# Main_Board_Schematic.net
KiCad netlist of a schematic drawn in EAGLE
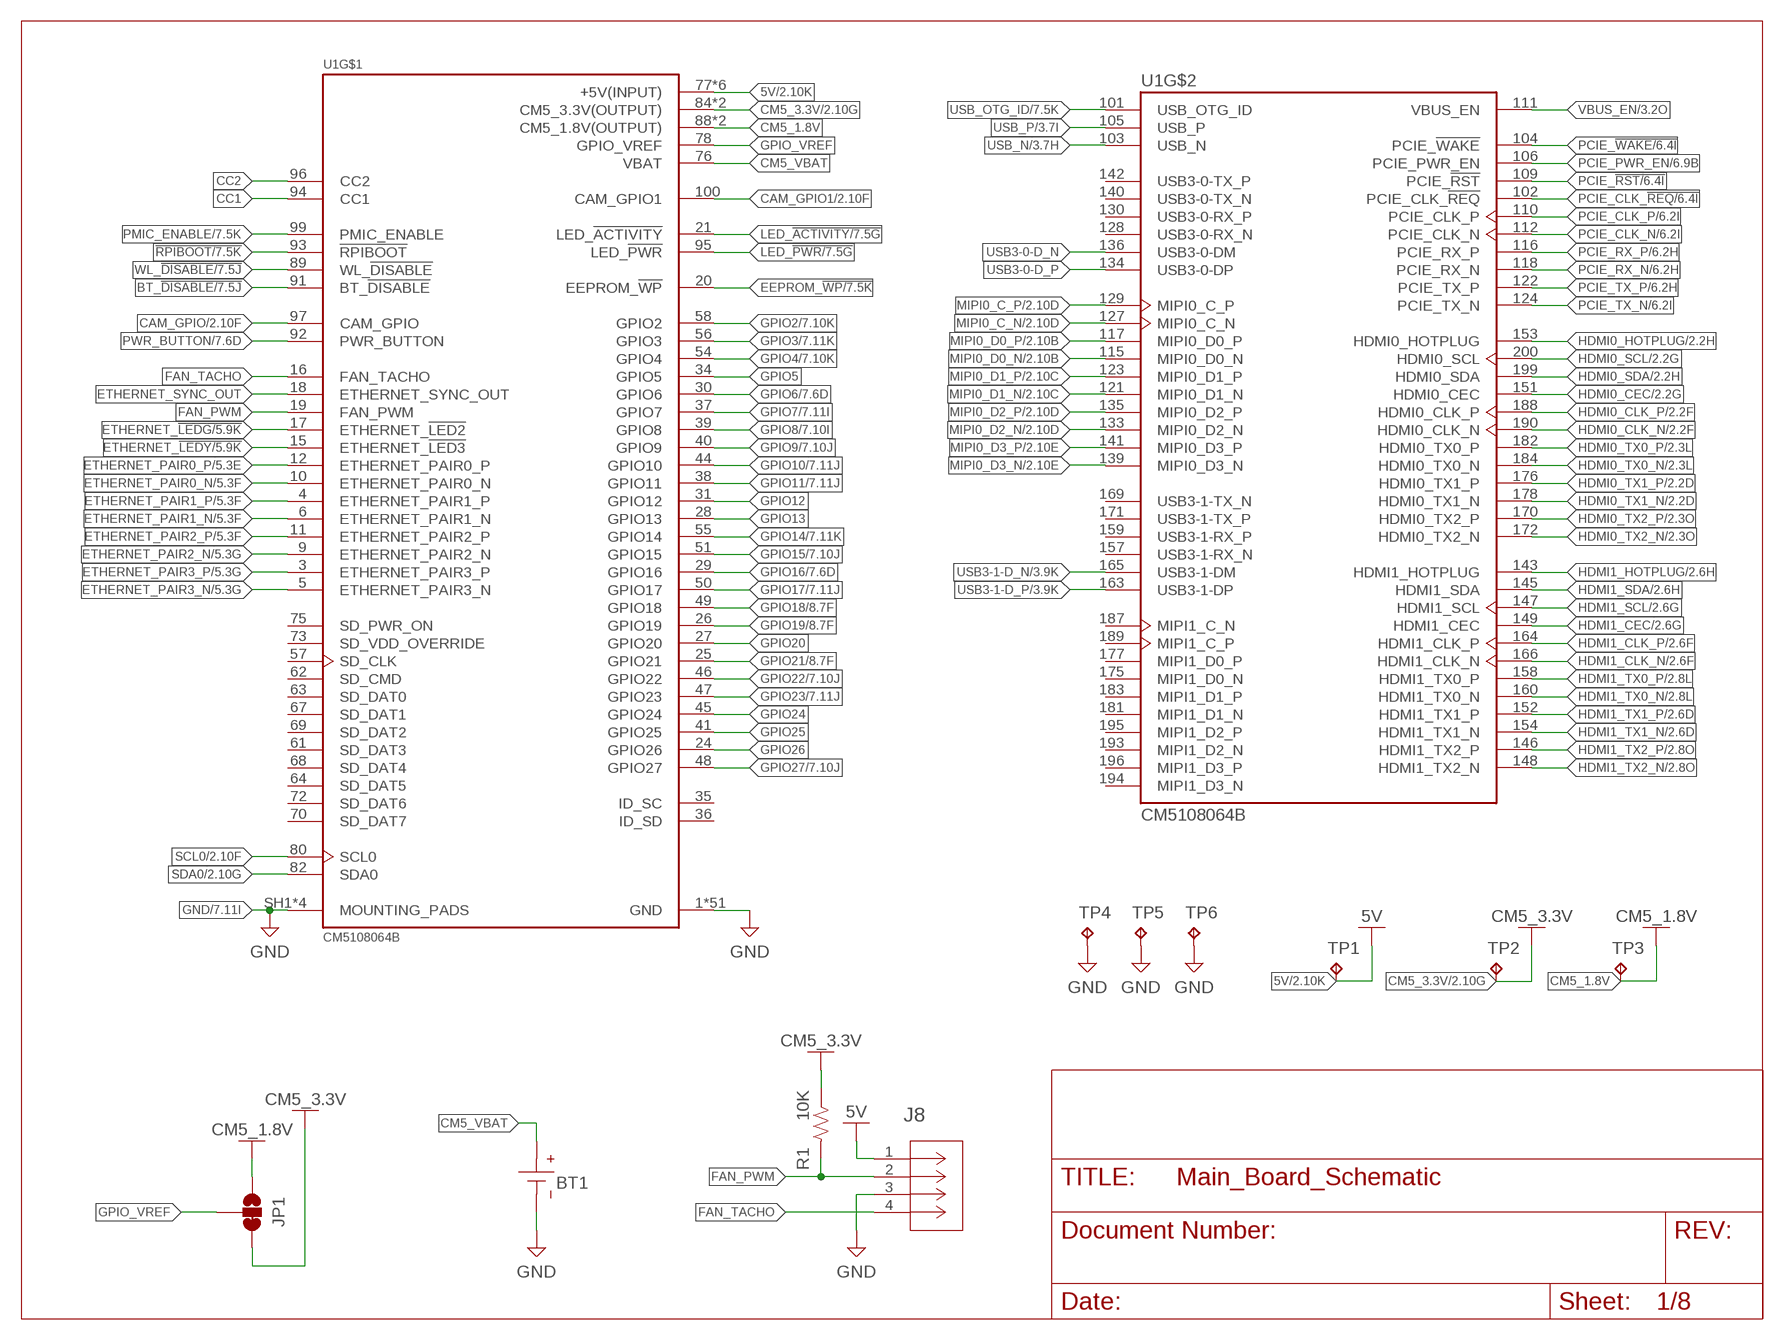
[diagram p0: schematic, sheet 1]
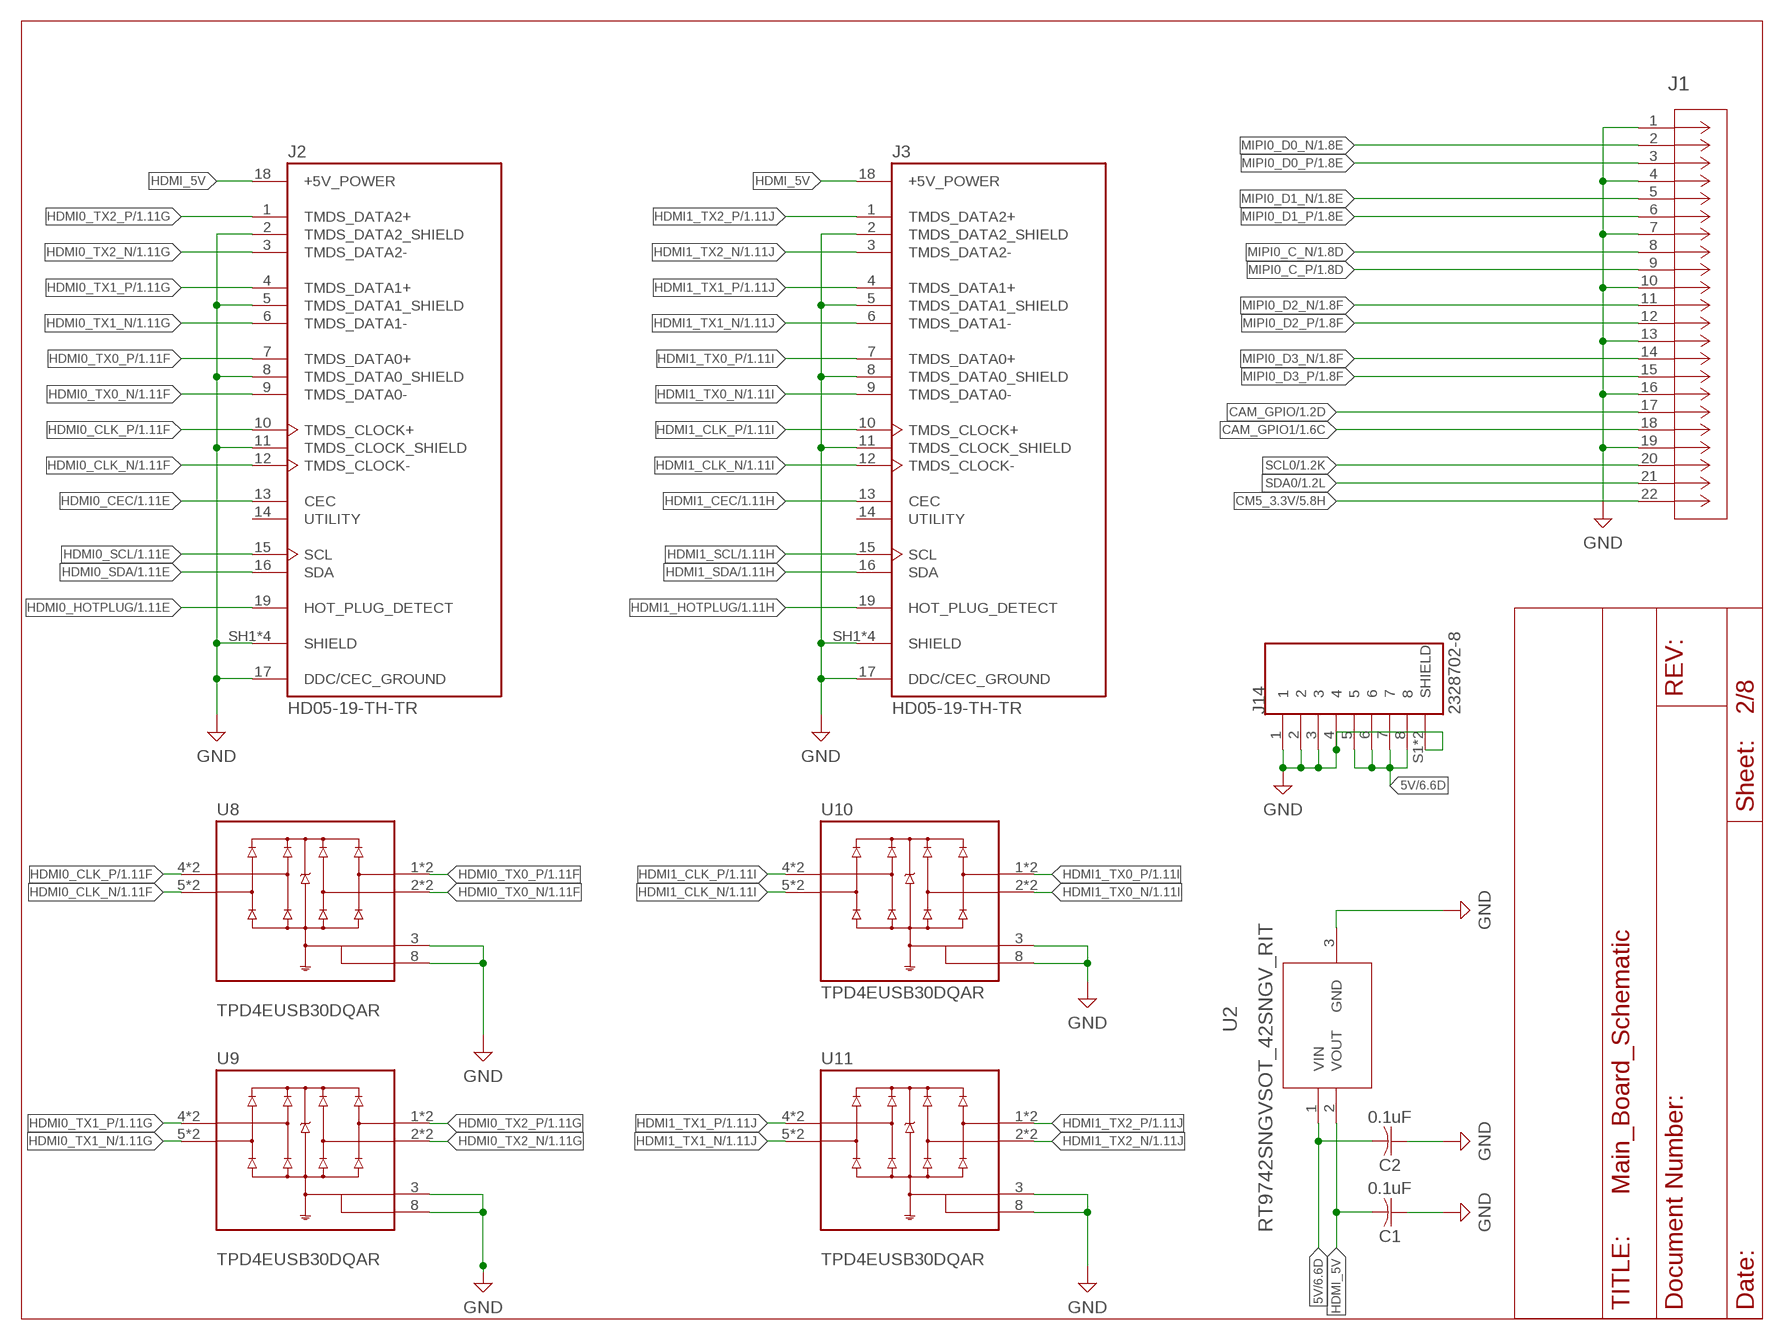
[diagram p1: schematic, sheet 2]
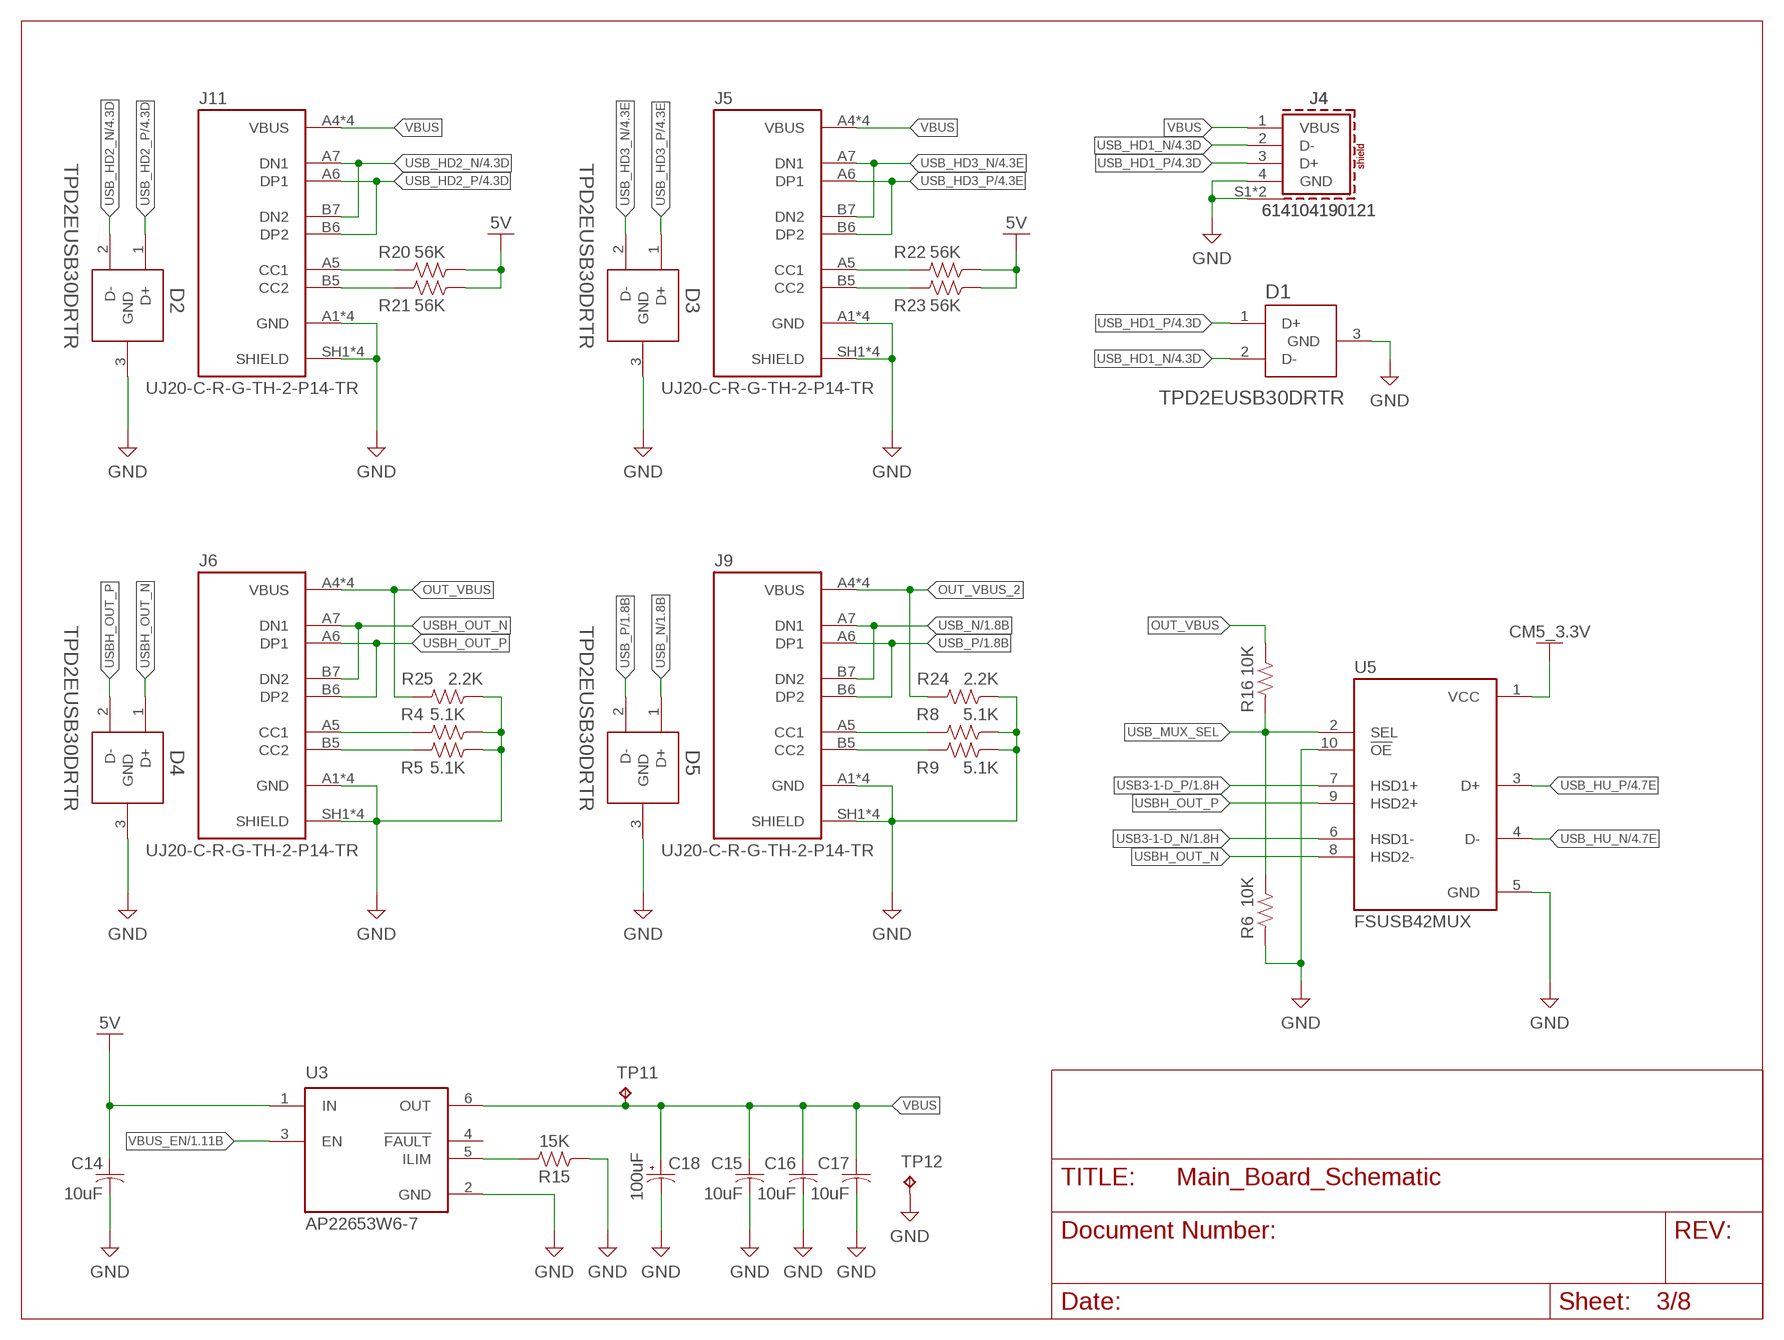
[diagram p2: schematic, sheet 3]
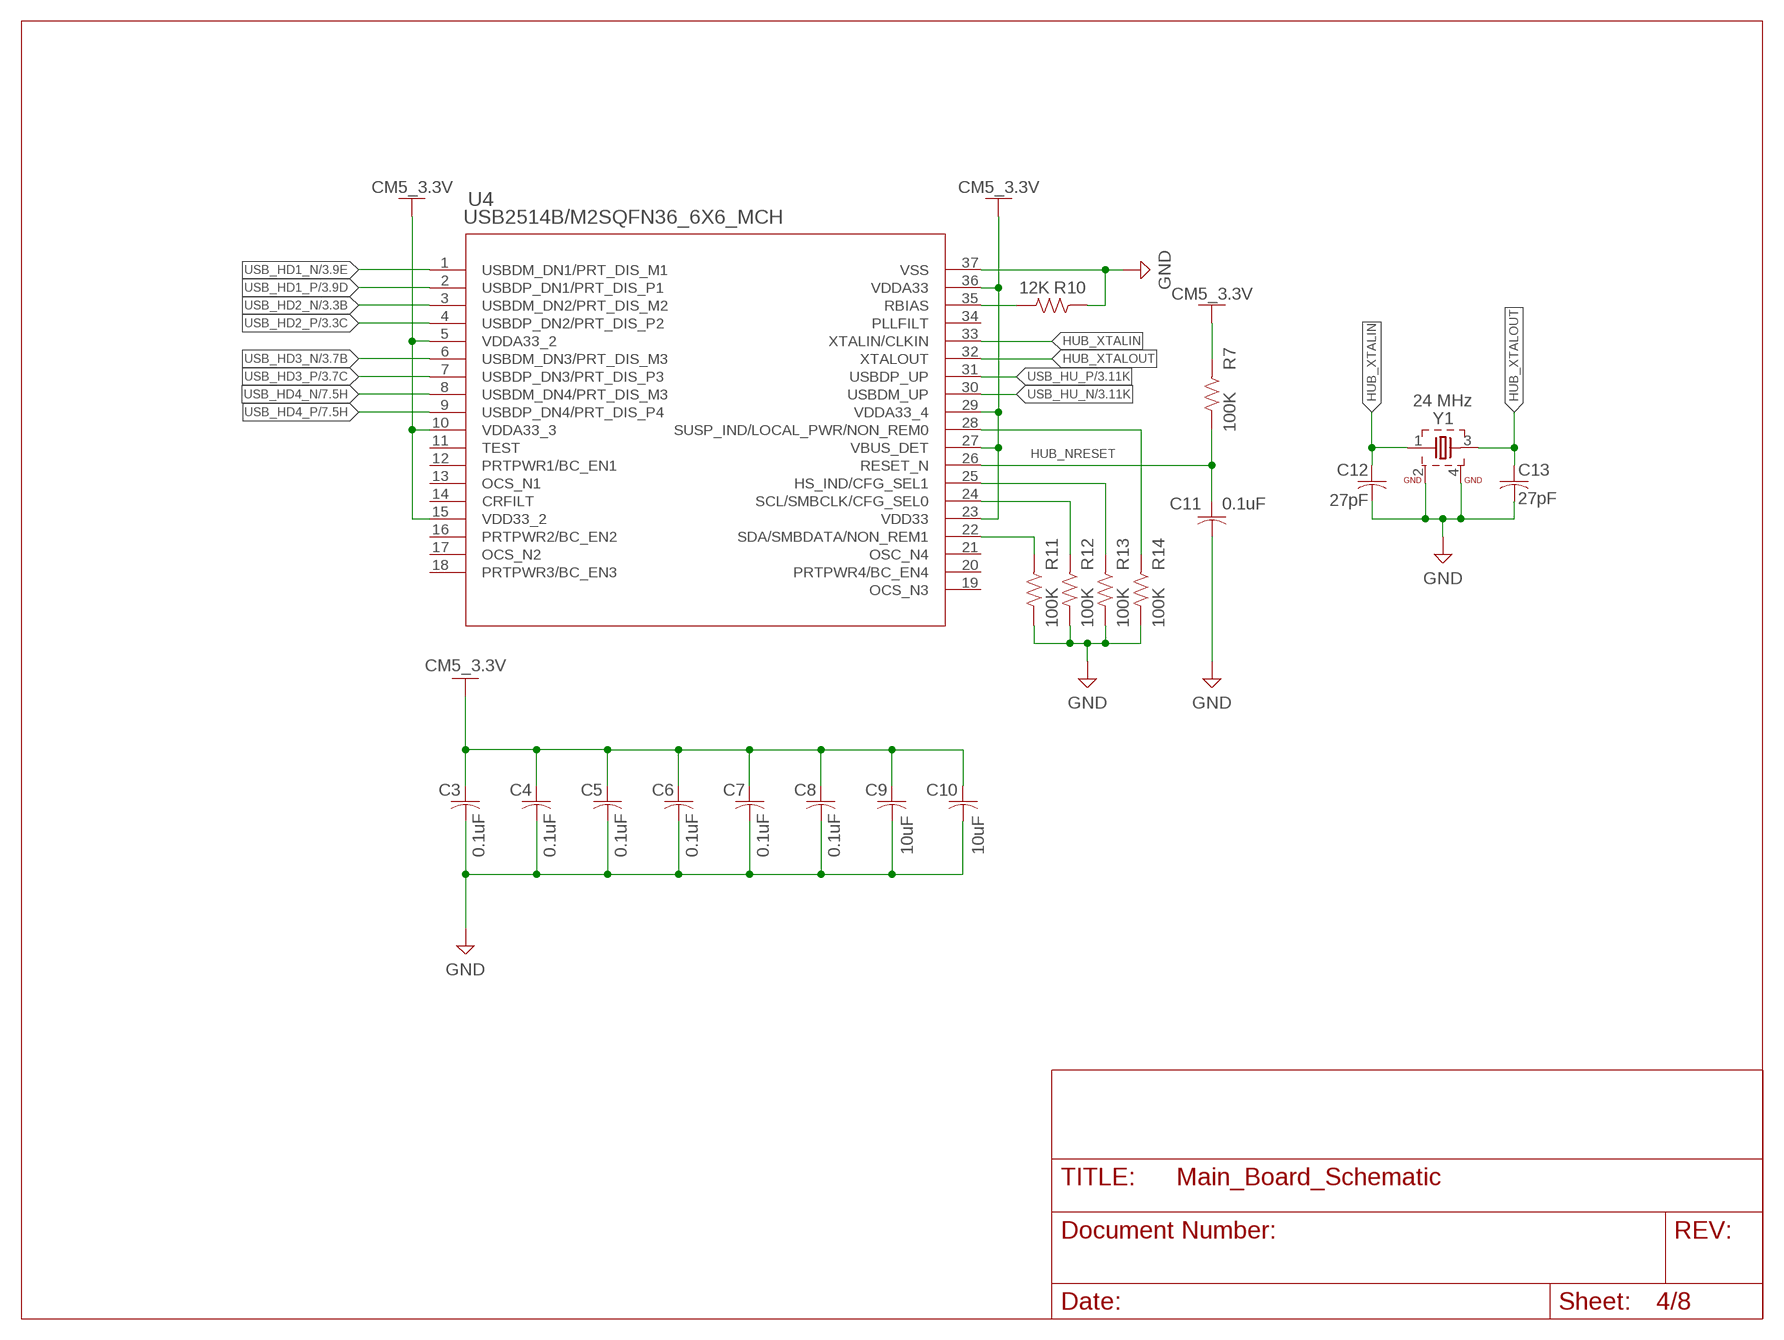
[diagram p3: schematic, sheet 4]
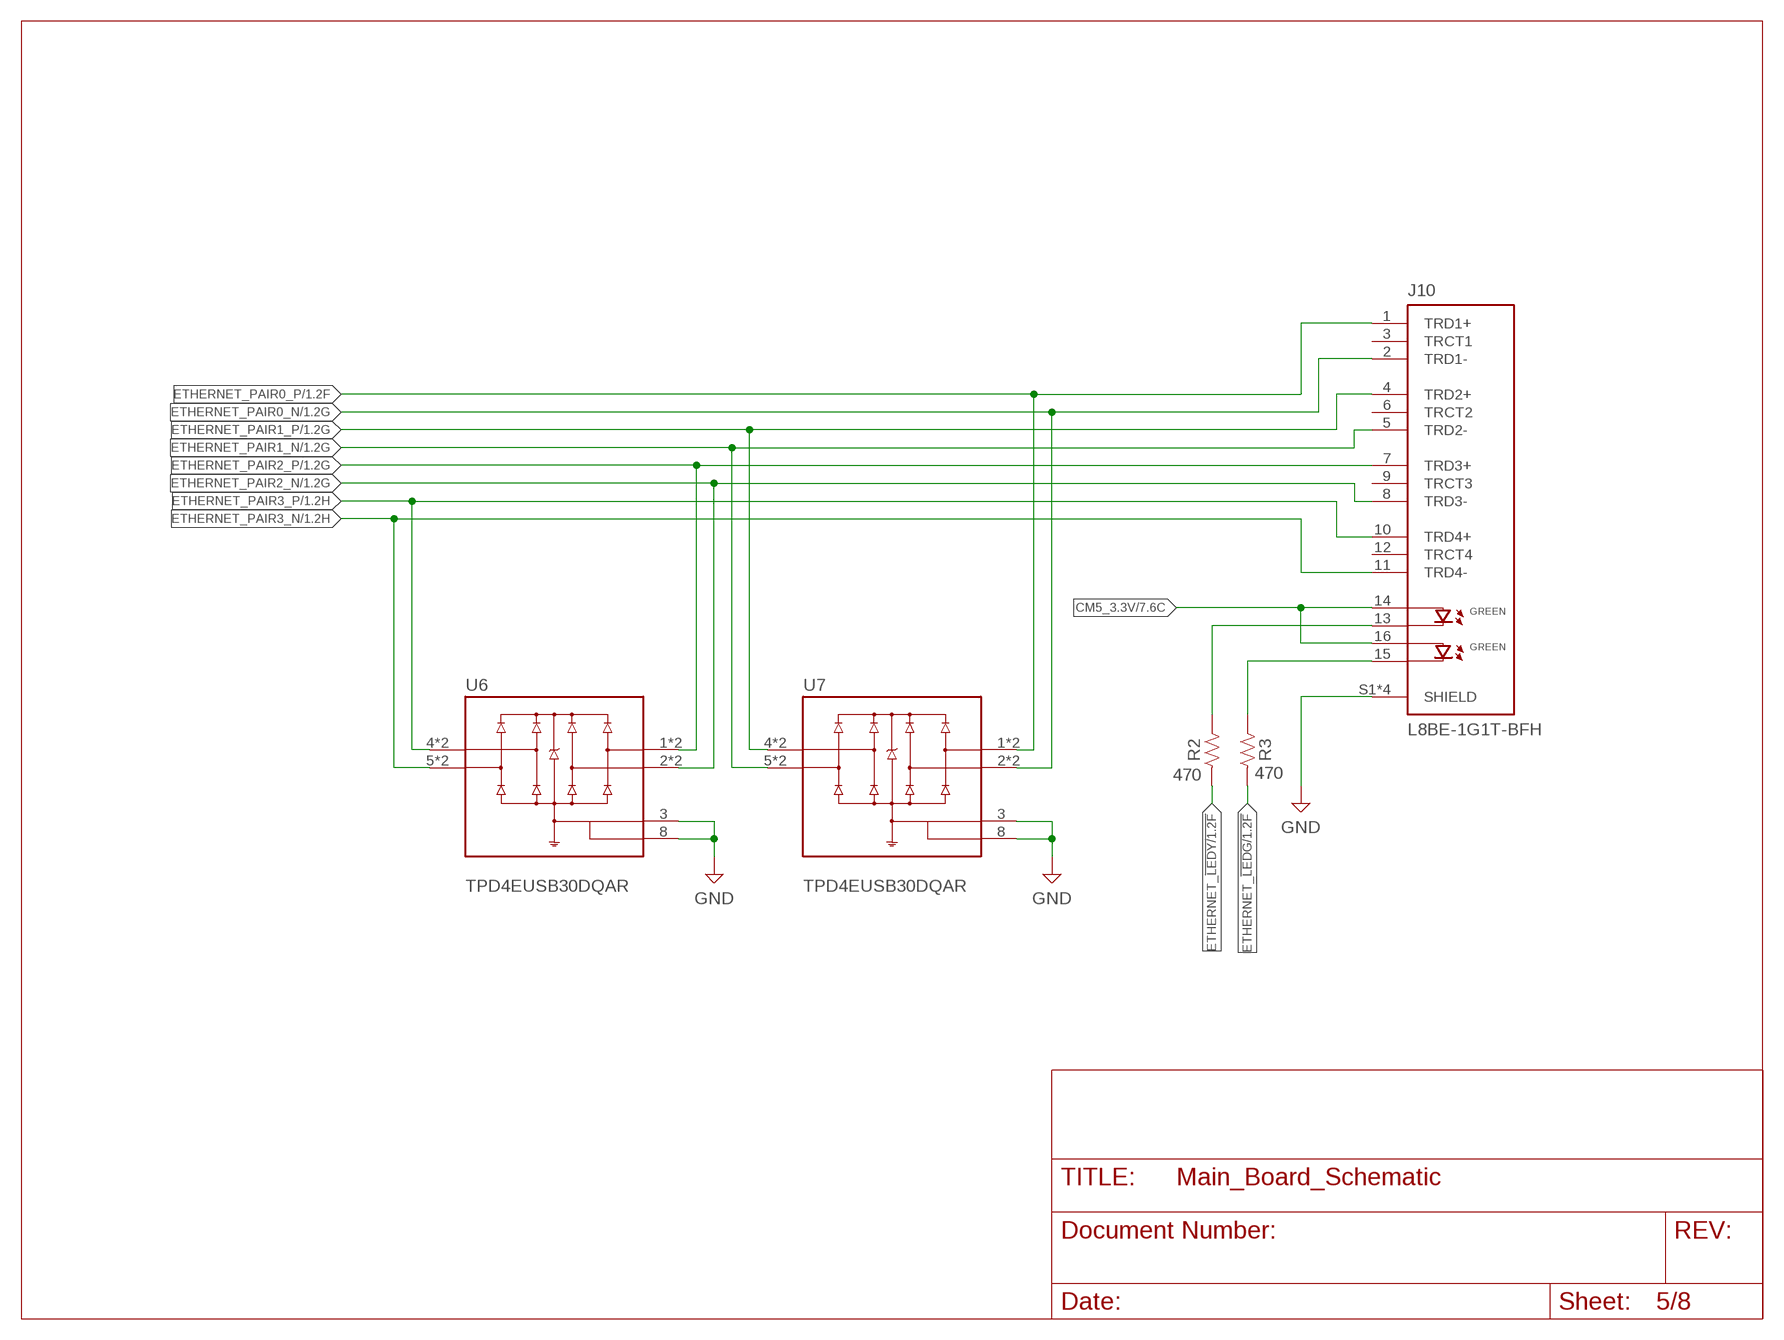
[diagram p4: schematic, sheet 5]
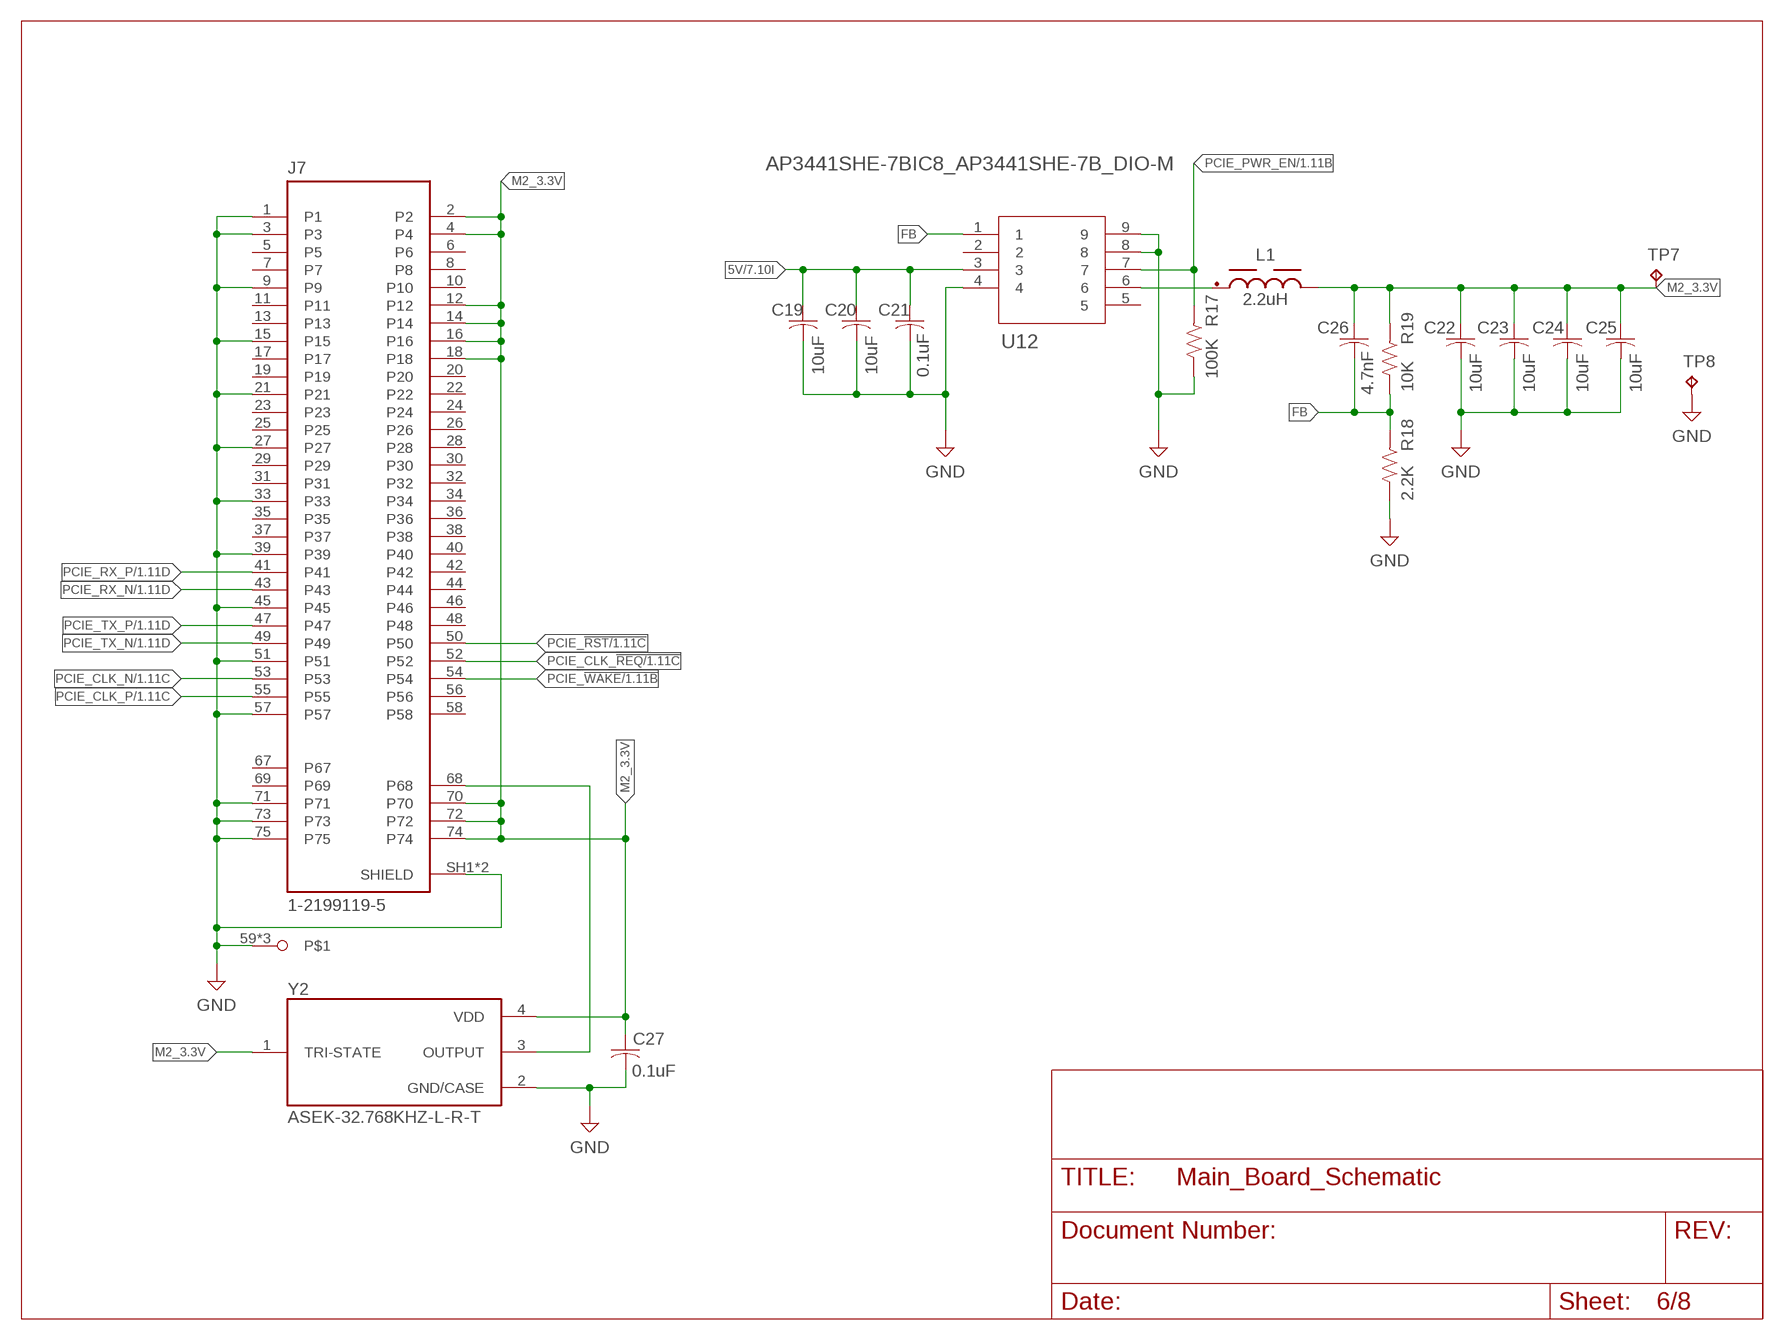
[diagram p5: schematic, sheet 6]
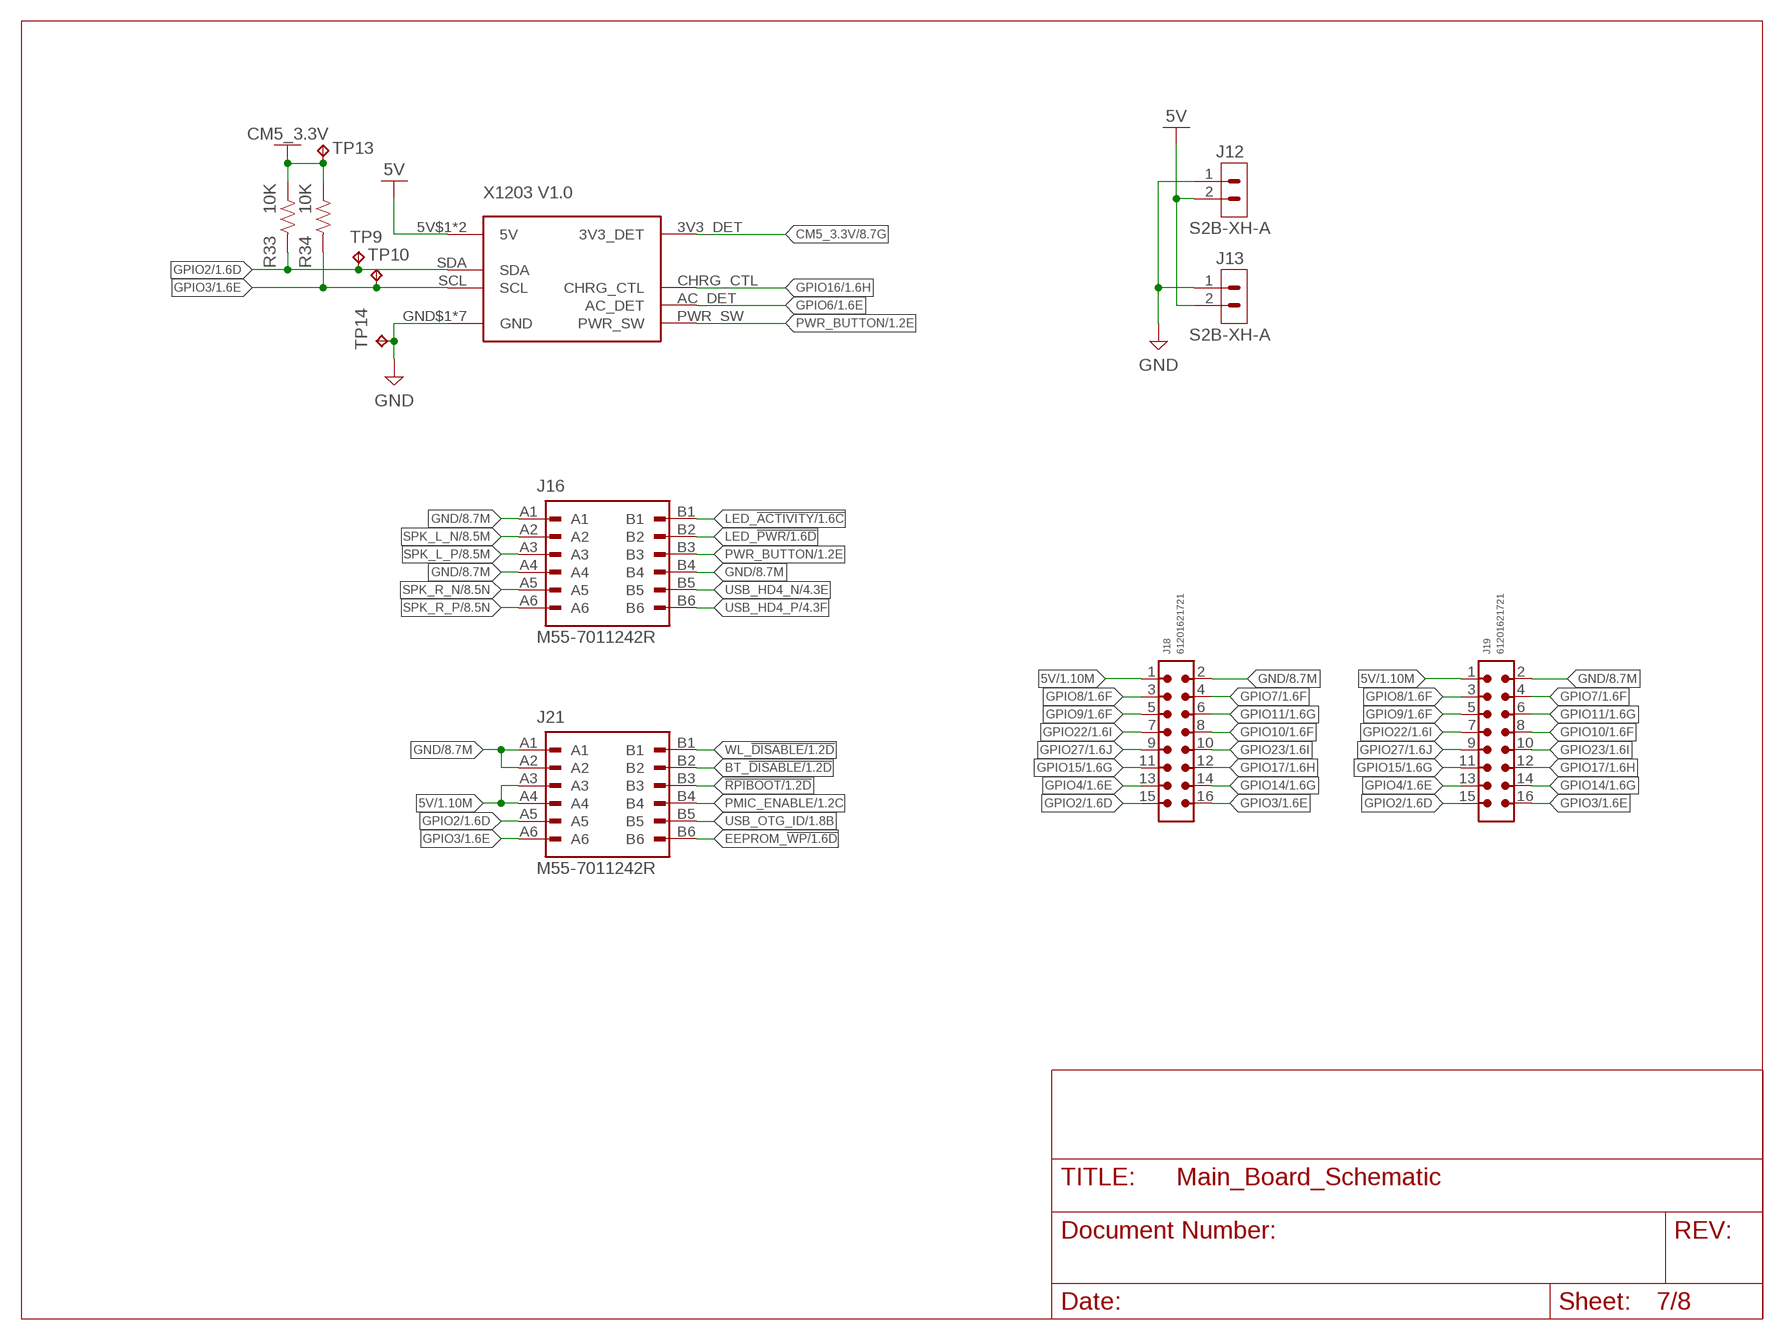
[diagram p6: schematic, sheet 7]
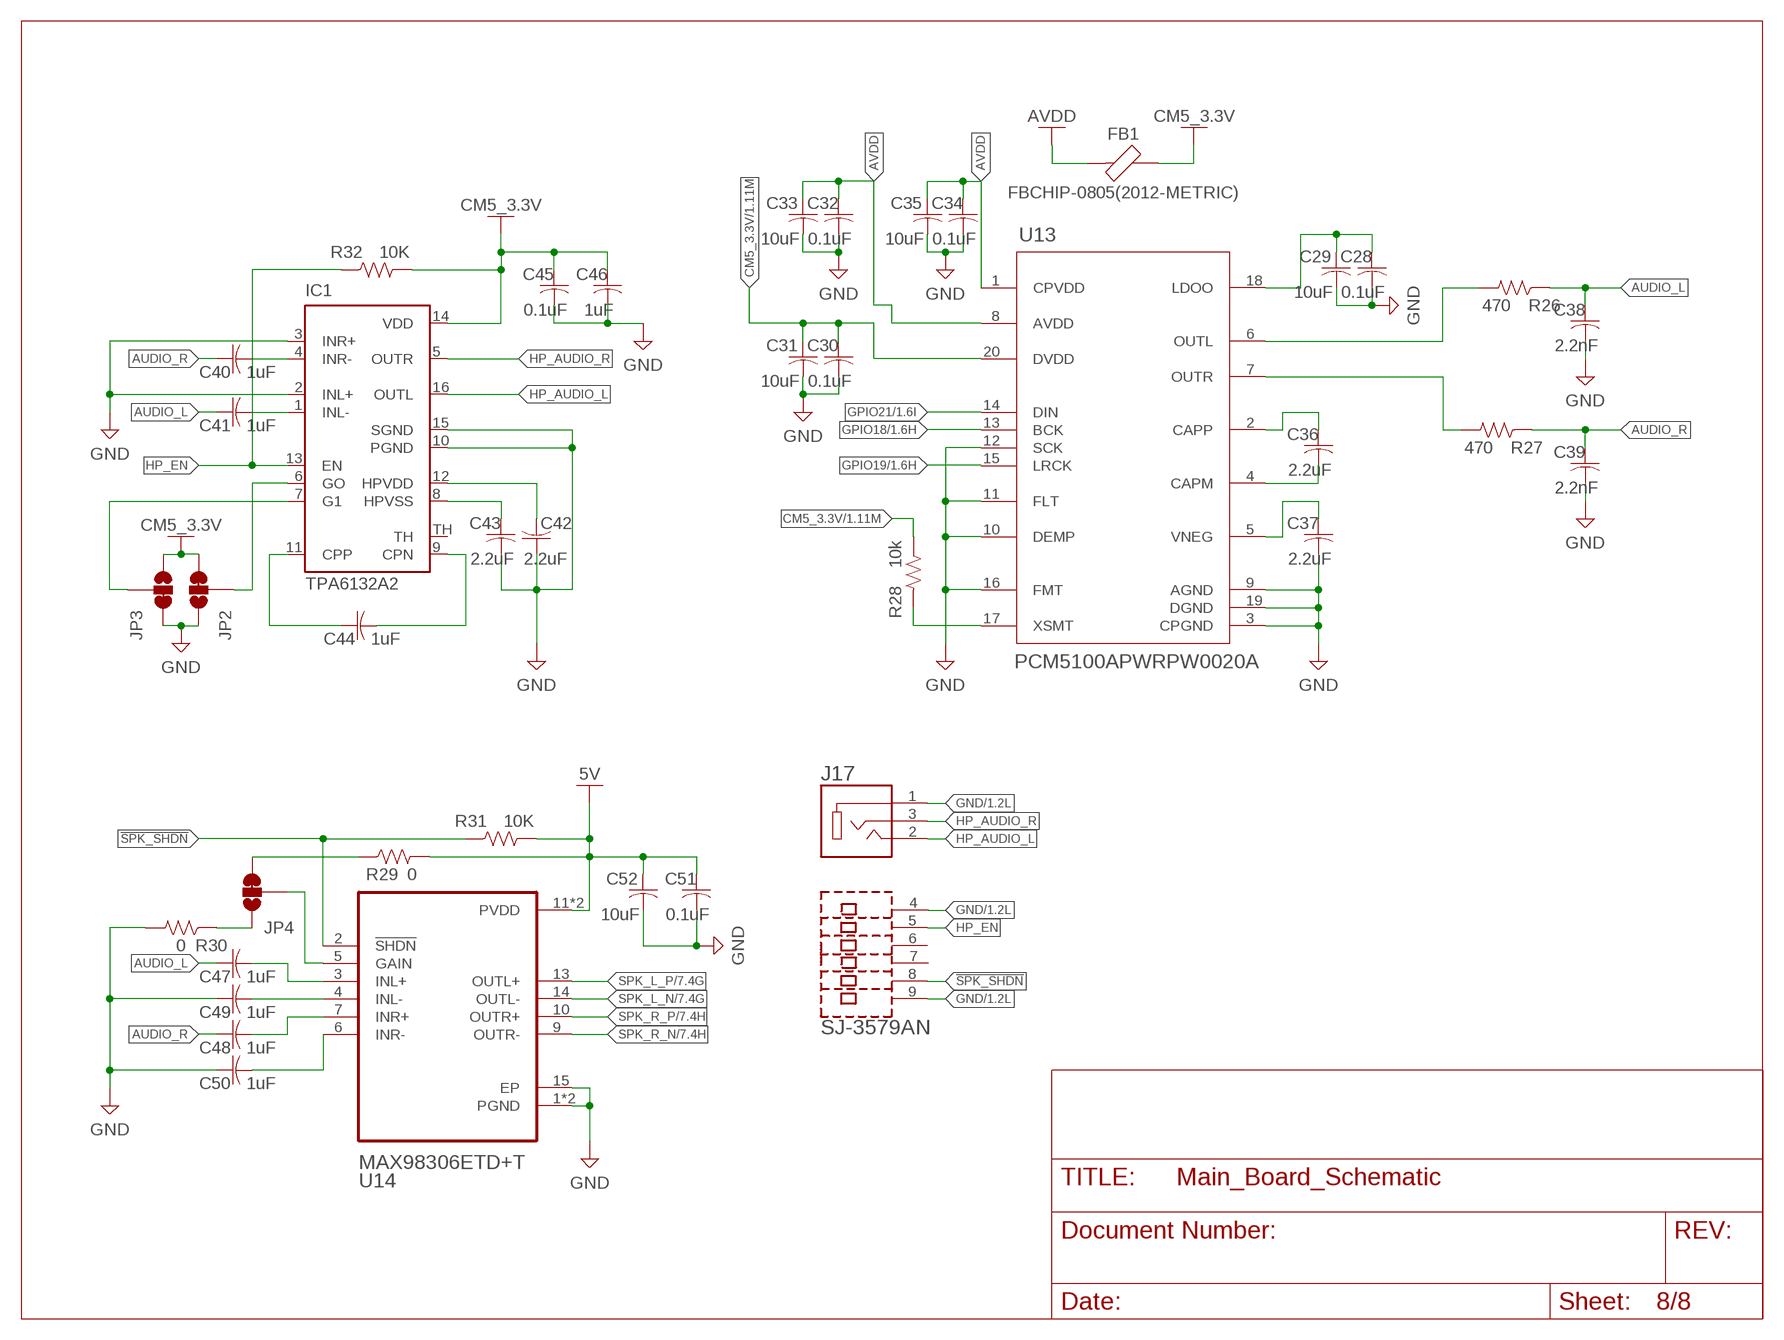
[diagram p7: schematic, sheet 8]

(export (version "E")
  (design (tool "Eeschema 10.0.6"))
  (components
    (comp (ref "C19")
      (value "10uF")
      (footprint "eagle-import:CAPC3216X135")
      (libsource (lib "eagle-import") (part "C-USCHIP-1206(3216-METRIC)_"))
    )
    (comp (ref "C20")
      (value "10uF")
      (footprint "eagle-import:CAPC3216X135")
      (libsource (lib "eagle-import") (part "C-USCHIP-1206(3216-METRIC)_"))
    )
    (comp (ref "C21")
      (value "0.1uF")
      (footprint "eagle-import:CAPC2012X110")
      (libsource (lib "eagle-import") (part "C-USCHIP-0805(2012-METRIC)_"))
    )
    (comp (ref "C22")
      (value "10uF")
      (footprint "eagle-import:CAPC3216X135")
      (libsource (lib "eagle-import") (part "C-USCHIP-1206(3216-METRIC)_"))
    )
    (comp (ref "C23")
      (value "10uF")
      (footprint "eagle-import:CAPC3216X135")
      (libsource (lib "eagle-import") (part "C-USCHIP-1206(3216-METRIC)_"))
    )
    (comp (ref "C24")
      (value "10uF")
      (footprint "eagle-import:CAPC3216X135")
      (libsource (lib "eagle-import") (part "C-USCHIP-1206(3216-METRIC)_"))
    )
    (comp (ref "C25")
      (value "10uF")
      (footprint "eagle-import:CAPC3216X135")
      (libsource (lib "eagle-import") (part "C-USCHIP-1206(3216-METRIC)_"))
    )
    (comp (ref "C26")
      (value "4.7nF")
      (footprint "eagle-import:CAPC2012X110")
      (libsource (lib "eagle-import") (part "C-USCHIP-0805(2012-METRIC)_"))
    )
    (comp (ref "C27")
      (value "0.1uF")
      (footprint "eagle-import:CAPC2012X110")
      (libsource (lib "eagle-import") (part "C-USCHIP-0805(2012-METRIC)_"))
    )
    (comp (ref "J7")
      (value "1-2199119-5")
      (footprint "eagle-import:TE_1-2199119-5")
      (fields (field (name "DIGIKEY_PART_NUMBER") "A115902CT-ND") (field (name "MF") "TE Connectivity"))
      (libsource (lib "eagle-import") (part "1-2199119-5"))
    )
    (comp (ref "L1")
      (value "2.2uH")
      (footprint "eagle-import:WE-XHMI_5030")
      (libsource (lib "eagle-import") (part "WE-XHMI_5030_74439334022"))
    )
    (comp (ref "R17")
      (value "100K")
      (footprint "eagle-import:RESC2012X65")
      (libsource (lib "eagle-import") (part "R-USCHIP-0805(2012-METRIC)_"))
    )
    (comp (ref "R18")
      (value "2.2K")
      (footprint "eagle-import:RESC2012X65")
      (libsource (lib "eagle-import") (part "R-USCHIP-0805(2012-METRIC)_"))
    )
    (comp (ref "R19")
      (value "10K")
      (footprint "eagle-import:RESC2012X65")
      (libsource (lib "eagle-import") (part "R-USCHIP-0805(2012-METRIC)_"))
    )
    (comp (ref "TP7")
      (value "TPB1,27")
      (footprint "eagle-import:B1,27")
      (libsource (lib "eagle-import") (part "TPB1,27"))
    )
    (comp (ref "TP8")
      (value "TPB1,27")
      (footprint "eagle-import:B1,27")
      (libsource (lib "eagle-import") (part "TPB1,27"))
    )
    (comp (ref "U12")
      (value "AP3441SHE-7BIC8_AP3441SHE-7B_DIO-M")
      (footprint "eagle-import:IC8_AP3441SHE-7B_DIO-M")
      (fields
        (field (name "MANUFACTURER_PART_NUMBER") "AP3441SHE-7B")
        (field (name "COPYRIGHT") "Copyright (C) 2025 Ultra Librarian. All rights reserved.")
      )
      (libsource (lib "eagle-import") (part "AP3441SHE-7BIC8_AP3441SHE-7B_DIO-M"))
    )
    (comp (ref "Y2")
      (value "ASEK-32.768KHZ-L-R-T")
      (footprint "eagle-import:XTAL_ASEK-32.768KHZ-L-R-T")
      (fields (field (name "MANUFACTURER") "Abracon"))
      (libsource (lib "eagle-import") (part "ASEK-32.768KHZ-L-R-T"))
    )
    (comp (ref "C28")
      (value "0.1uF")
      (footprint "eagle-import:CAPC2012X110")
      (libsource (lib "eagle-import") (part "C-USCHIP-0805(2012-METRIC)_"))
    )
    (comp (ref "C29")
      (value "10uF")
      (footprint "eagle-import:CAPC3216X135")
      (libsource (lib "eagle-import") (part "C-USCHIP-1206(3216-METRIC)_"))
    )
    (comp (ref "C30")
      (value "0.1uF")
      (footprint "eagle-import:CAPC2012X110")
      (libsource (lib "eagle-import") (part "C-USCHIP-0805(2012-METRIC)_"))
    )
    (comp (ref "C31")
      (value "10uF")
      (footprint "eagle-import:CAPC3216X135")
      (libsource (lib "eagle-import") (part "C-USCHIP-1206(3216-METRIC)_"))
    )
    (comp (ref "C32")
      (value "0.1uF")
      (footprint "eagle-import:CAPC2012X110")
      (libsource (lib "eagle-import") (part "C-USCHIP-0805(2012-METRIC)_"))
    )
    (comp (ref "C33")
      (value "10uF")
      (footprint "eagle-import:CAPC3216X135")
      (libsource (lib "eagle-import") (part "C-USCHIP-1206(3216-METRIC)_"))
    )
    (comp (ref "C34")
      (value "0.1uF")
      (footprint "eagle-import:CAPC2012X110")
      (libsource (lib "eagle-import") (part "C-USCHIP-0805(2012-METRIC)_"))
    )
    (comp (ref "C35")
      (value "10uF")
      (footprint "eagle-import:CAPC3216X135")
      (libsource (lib "eagle-import") (part "C-USCHIP-1206(3216-METRIC)_"))
    )
    (comp (ref "C36")
      (value "2.2uF")
      (footprint "eagle-import:CAPC2012X110")
      (libsource (lib "eagle-import") (part "C-USCHIP-0805(2012-METRIC)_"))
    )
    (comp (ref "C37")
      (value "2.2uF")
      (footprint "eagle-import:CAPC2012X110")
      (libsource (lib "eagle-import") (part "C-USCHIP-0805(2012-METRIC)_"))
    )
    (comp (ref "C38")
      (value "2.2nF")
      (footprint "eagle-import:CAPC2012X110")
      (libsource (lib "eagle-import") (part "C-USCHIP-0805(2012-METRIC)_"))
    )
    (comp (ref "C39")
      (value "2.2nF")
      (footprint "eagle-import:CAPC2012X110")
      (libsource (lib "eagle-import") (part "C-USCHIP-0805(2012-METRIC)_"))
    )
    (comp (ref "C40")
      (value "1uF")
      (footprint "eagle-import:CAPC2012X110")
      (libsource (lib "eagle-import") (part "C-USCHIP-0805(2012-METRIC)_"))
    )
    (comp (ref "C41")
      (value "1uF")
      (footprint "eagle-import:CAPC2012X110")
      (libsource (lib "eagle-import") (part "C-USCHIP-0805(2012-METRIC)_"))
    )
    (comp (ref "C42")
      (value "2.2uF")
      (footprint "eagle-import:CAPC2012X110")
      (libsource (lib "eagle-import") (part "C-USCHIP-0805(2012-METRIC)_"))
    )
    (comp (ref "C43")
      (value "2.2uF")
      (footprint "eagle-import:CAPC2012X110")
      (libsource (lib "eagle-import") (part "C-USCHIP-0805(2012-METRIC)_"))
    )
    (comp (ref "C44")
      (value "1uF")
      (footprint "eagle-import:CAPC2012X110")
      (libsource (lib "eagle-import") (part "C-USCHIP-0805(2012-METRIC)_"))
    )
    (comp (ref "C45")
      (value "0.1uF")
      (footprint "eagle-import:CAPC2012X110")
      (libsource (lib "eagle-import") (part "C-USCHIP-0805(2012-METRIC)_"))
    )
    (comp (ref "C46")
      (value "1uF")
      (footprint "eagle-import:CAPC2012X110")
      (libsource (lib "eagle-import") (part "C-USCHIP-0805(2012-METRIC)_"))
    )
    (comp (ref "C47")
      (value "1uF")
      (footprint "eagle-import:CAPC2012X110")
      (libsource (lib "eagle-import") (part "C-USCHIP-0805(2012-METRIC)_"))
    )
    (comp (ref "C48")
      (value "1uF")
      (footprint "eagle-import:CAPC2012X110")
      (libsource (lib "eagle-import") (part "C-USCHIP-0805(2012-METRIC)_"))
    )
    (comp (ref "C49")
      (value "1uF")
      (footprint "eagle-import:CAPC2012X110")
      (libsource (lib "eagle-import") (part "C-USCHIP-0805(2012-METRIC)_"))
    )
    (comp (ref "C50")
      (value "1uF")
      (footprint "eagle-import:CAPC2012X110")
      (libsource (lib "eagle-import") (part "C-USCHIP-0805(2012-METRIC)_"))
    )
    (comp (ref "C51")
      (value "0.1uF")
      (footprint "eagle-import:CAPC2012X110")
      (libsource (lib "eagle-import") (part "C-USCHIP-0805(2012-METRIC)_"))
    )
    (comp (ref "C52")
      (value "10uF")
      (footprint "eagle-import:CAPC3216X135")
      (libsource (lib "eagle-import") (part "C-USCHIP-1206(3216-METRIC)_"))
    )
    (comp (ref "FB1")
      (value "FBCHIP-0805(2012-METRIC)")
      (footprint "eagle-import:BEADC2012X105N")
      (libsource (lib "eagle-import") (part "FBCHIP-0805(2012-METRIC)"))
    )
    (comp (ref "IC1")
      (value "TPA6132A2")
      (footprint "eagle-import:QFN16")
      (fields (field (name "MPN") "TPA6132A2RTET"))
      (libsource (lib "eagle-import") (part "TPA6132A2"))
    )
    (comp (ref "J17")
      (value "SJ-3579AN")
      (footprint "eagle-import:CUI_SJ-3579AN")
      (fields (field (name "MF") "CUI Inc"))
      (libsource (lib "eagle-import") (part "SJ-3579AN"))
    )
    (comp (ref "JP2")
      (value "JUMPER-SMT_3_1-NC_TRACE_SILK")
      (footprint "eagle-import:SMT-JUMPER_3_1-NC_TRACE_SILK")
      (libsource (lib "eagle-import") (part "JUMPER-SMT_3_1-NC_TRACE_SILK"))
    )
    (comp (ref "JP3")
      (value "JUMPER-SMT_3_1-NC_TRACE_SILK")
      (footprint "eagle-import:SMT-JUMPER_3_1-NC_TRACE_SILK")
      (libsource (lib "eagle-import") (part "JUMPER-SMT_3_1-NC_TRACE_SILK"))
    )
    (comp (ref "JP4")
      (value "JUMPER-SMT_3_1-NC_TRACE_SILK")
      (footprint "eagle-import:SMT-JUMPER_3_1-NC_TRACE_SILK")
      (libsource (lib "eagle-import") (part "JUMPER-SMT_3_1-NC_TRACE_SILK"))
    )
    (comp (ref "R26")
      (value "470")
      (footprint "eagle-import:RESC2012X65")
      (libsource (lib "eagle-import") (part "R-USCHIP-0805(2012-METRIC)_"))
    )
    (comp (ref "R27")
      (value "470")
      (footprint "eagle-import:RESC2012X65")
      (libsource (lib "eagle-import") (part "R-USCHIP-0805(2012-METRIC)_"))
    )
    (comp (ref "R28")
      (value "10k")
      (footprint "eagle-import:RESC2012X65")
      (libsource (lib "eagle-import") (part "R-USCHIP-0805(2012-METRIC)_"))
    )
    (comp (ref "R29")
      (value "0")
      (footprint "eagle-import:RESC2012X65")
      (libsource (lib "eagle-import") (part "R-USCHIP-0805(2012-METRIC)_"))
    )
    (comp (ref "R30")
      (value "0")
      (footprint "eagle-import:RESC2012X65")
      (libsource (lib "eagle-import") (part "R-USCHIP-0805(2012-METRIC)_"))
    )
    (comp (ref "R31")
      (value "10K")
      (footprint "eagle-import:RESC2012X65")
      (libsource (lib "eagle-import") (part "R-USCHIP-0805(2012-METRIC)_"))
    )
    (comp (ref "R32")
      (value "10K")
      (footprint "eagle-import:RESC2012X65")
      (libsource (lib "eagle-import") (part "R-USCHIP-0805(2012-METRIC)_"))
    )
    (comp (ref "U13")
      (value "PCM5100APWRPW0020A")
      (footprint "eagle-import:PW0020A")
      (fields
        (field (name "MANUFACTURER_PART_NUMBER") "PCM5100APWR")
        (field (name "COPYRIGHT") "Copyright (C) 2024 Ultra Librarian. All rights reserved.")
      )
      (libsource (lib "eagle-import") (part "PCM5100APWRPW0020A"))
    )
    (comp (ref "U14")
      (value "MAX98306ETD+T")
      (footprint "eagle-import:SON40P300X300X80-15N")
      (fields (field (name "MF") "Maxim Integrated"))
      (libsource (lib "eagle-import") (part "MAX98306ETD+T"))
    )
    (comp (ref "BT1")
      (value "COIN-CELL-SMT-3P-3002-BR2016")
      (footprint "eagle-import:BAT_3002")
      (fields (field (name "MANUFACTURER") "Keystone Electronics") (field (name "MPN") "3002"))
      (libsource (lib "eagle-import") (part "COIN-CELL-SMT-3P-?-3002BR2016"))
    )
    (comp (ref "J8")
      (value "SM04B-SRSS-TBCONN_SM04B-SRSS-TB_JST")
      (footprint "eagle-import:CONN_SM04B-SRSS-TB_JST")
      (fields
        (field (name "MANUFACTURER_PART_NUMBER") "SM04B-SRSS-TB")
        (field (name "COPYRIGHT") "Copyright (C) 2024 Ultra Librarian. All rights reserved.")
      )
      (libsource (lib "eagle-import") (part "SM04B-SRSS-TBCONN_SM04B-SRSS-TB_JST"))
    )
    (comp (ref "JP1")
      (value "JUMPER-SMT_3_1-NC_TRACE_SILK")
      (footprint "eagle-import:SMT-JUMPER_3_1-NC_TRACE_SILK")
      (libsource (lib "eagle-import") (part "JUMPER-SMT_3_1-NC_TRACE_SILK"))
    )
    (comp (ref "R1")
      (value "10K")
      (footprint "eagle-import:RESC2012X65")
      (libsource (lib "eagle-import") (part "R-USCHIP-0805(2012-METRIC)_"))
    )
    (comp (ref "TP1")
      (value "TPB1,27")
      (footprint "eagle-import:B1,27")
      (libsource (lib "eagle-import") (part "TPB1,27"))
    )
    (comp (ref "TP2")
      (value "TPB1,27")
      (footprint "eagle-import:B1,27")
      (libsource (lib "eagle-import") (part "TPB1,27"))
    )
    (comp (ref "TP3")
      (value "TPB1,27")
      (footprint "eagle-import:B1,27")
      (libsource (lib "eagle-import") (part "TPB1,27"))
    )
    (comp (ref "TP4")
      (value "TPB1,27")
      (footprint "eagle-import:B1,27")
      (libsource (lib "eagle-import") (part "TPB1,27"))
    )
    (comp (ref "TP5")
      (value "TPB1,27")
      (footprint "eagle-import:B1,27")
      (libsource (lib "eagle-import") (part "TPB1,27"))
    )
    (comp (ref "TP6")
      (value "TPB1,27")
      (footprint "eagle-import:B1,27")
      (libsource (lib "eagle-import") (part "TPB1,27"))
    )
    (comp (ref "U1")
      (value "CM5108064B")
      (footprint "eagle-import:MODULE_CM5108064B")
      (fields (field (name "MF") "Raspberry Pi") (field (name "CONNECTOR") "2 x (10164227-1001A1RLF)"))
      (libsource (lib "eagle-import") (part "CM5108064B"))
    )
    (comp (ref "J10")
      (value "L8BE-1G1T-BFH")
      (footprint "eagle-import:BEL_L8BE-1G1T-BFH")
      (fields (field (name "MANUFACTURER") "Bel Fuse"))
      (libsource (lib "eagle-import") (part "L8BE-1G1T-BFH"))
    )
    (comp (ref "R2")
      (value "470")
      (footprint "eagle-import:RESC2012X65")
      (libsource (lib "eagle-import") (part "R-USCHIP-0805(2012-METRIC)_"))
    )
    (comp (ref "R3")
      (value "470")
      (footprint "eagle-import:RESC2012X65")
      (libsource (lib "eagle-import") (part "R-USCHIP-0805(2012-METRIC)_"))
    )
    (comp (ref "U6")
      (value "TPD4EUSB30DQAR")
      (footprint "eagle-import:IC_TPD4EUSB30DQAR")
      (fields (field (name "MANUFACTURER") "Texas Instruments"))
      (libsource (lib "eagle-import") (part "TPD4EUSB30DQAR"))
    )
    (comp (ref "U7")
      (value "TPD4EUSB30DQAR")
      (footprint "eagle-import:IC_TPD4EUSB30DQAR")
      (fields (field (name "MANUFACTURER") "Texas Instruments"))
      (libsource (lib "eagle-import") (part "TPD4EUSB30DQAR"))
    )
    (comp (ref "C3")
      (value "0.1uF")
      (footprint "eagle-import:CAPC2012X110")
      (libsource (lib "eagle-import") (part "C-USCHIP-0805(2012-METRIC)_"))
    )
    (comp (ref "C4")
      (value "0.1uF")
      (footprint "eagle-import:CAPC2012X110")
      (libsource (lib "eagle-import") (part "C-USCHIP-0805(2012-METRIC)_"))
    )
    (comp (ref "C5")
      (value "0.1uF")
      (footprint "eagle-import:CAPC2012X110")
      (libsource (lib "eagle-import") (part "C-USCHIP-0805(2012-METRIC)_"))
    )
    (comp (ref "C6")
      (value "0.1uF")
      (footprint "eagle-import:CAPC2012X110")
      (libsource (lib "eagle-import") (part "C-USCHIP-0805(2012-METRIC)_"))
    )
    (comp (ref "C7")
      (value "0.1uF")
      (footprint "eagle-import:CAPC2012X110")
      (libsource (lib "eagle-import") (part "C-USCHIP-0805(2012-METRIC)_"))
    )
    (comp (ref "C8")
      (value "0.1uF")
      (footprint "eagle-import:CAPC2012X110")
      (libsource (lib "eagle-import") (part "C-USCHIP-0805(2012-METRIC)_"))
    )
    (comp (ref "C9")
      (value "10uF")
      (footprint "eagle-import:CAPC3216X135")
      (libsource (lib "eagle-import") (part "C-USCHIP-1206(3216-METRIC)_"))
    )
    (comp (ref "C10")
      (value "10uF")
      (footprint "eagle-import:CAPC3216X135")
      (libsource (lib "eagle-import") (part "C-USCHIP-1206(3216-METRIC)_"))
    )
    (comp (ref "C11")
      (value "0.1uF")
      (footprint "eagle-import:CAPC2012X110")
      (libsource (lib "eagle-import") (part "C-USCHIP-0805(2012-METRIC)_"))
    )
    (comp (ref "C12")
      (value "27pF")
      (footprint "eagle-import:CAPC2012X110")
      (libsource (lib "eagle-import") (part "C-USCHIP-0805(2012-METRIC)_"))
    )
    (comp (ref "C13")
      (value "27pF")
      (footprint "eagle-import:CAPC2012X110")
      (libsource (lib "eagle-import") (part "C-USCHIP-0805(2012-METRIC)_"))
    )
    (comp (ref "R7")
      (value "100K")
      (footprint "eagle-import:RESC2012X65")
      (libsource (lib "eagle-import") (part "R-USCHIP-0805(2012-METRIC)_"))
    )
    (comp (ref "R10")
      (value "12K")
      (footprint "eagle-import:RESC2012X65")
      (libsource (lib "eagle-import") (part "R-USCHIP-0805(2012-METRIC)_"))
    )
    (comp (ref "R11")
      (value "100K")
      (footprint "eagle-import:RESC2012X65")
      (libsource (lib "eagle-import") (part "R-USCHIP-0805(2012-METRIC)_"))
    )
    (comp (ref "R12")
      (value "100K")
      (footprint "eagle-import:RESC2012X65")
      (libsource (lib "eagle-import") (part "R-USCHIP-0805(2012-METRIC)_"))
    )
    (comp (ref "R13")
      (value "100K")
      (footprint "eagle-import:RESC2012X65")
      (libsource (lib "eagle-import") (part "R-USCHIP-0805(2012-METRIC)_"))
    )
    (comp (ref "R14")
      (value "100K")
      (footprint "eagle-import:RESC2012X65")
      (libsource (lib "eagle-import") (part "R-USCHIP-0805(2012-METRIC)_"))
    )
    (comp (ref "U4")
      (value "USB2514B/M2SQFN36_6X6_MCH")
      (footprint "eagle-import:SQFN36_6X6_MCH")
      (fields
        (field (name "MANUFACTURER_PART_NUMBER") "USB2514B/M2")
        (field (name "COPYRIGHT") "Copyright (C) 2024 Ultra Librarian. All rights reserved.")
      )
      (libsource (lib "eagle-import") (part "USB2514B/M2SQFN36_6X6_MCH"))
    )
    (comp (ref "Y1")
      (value "24 MHz")
      (footprint "eagle-import:WE-XTAL_CFPX-180")
      (fields (field (name "TOLERANCE") "±20ppm"))
      (libsource (lib "eagle-import") (part "WE-XTAL_CFPX-180_830058124"))
    )
    (comp (ref "C1")
      (value "0.1uF")
      (footprint "eagle-import:CAPC2012X110")
      (libsource (lib "eagle-import") (part "C-USCHIP-0805(2012-METRIC)_"))
    )
    (comp (ref "C2")
      (value "0.1uF")
      (footprint "eagle-import:CAPC2012X110")
      (libsource (lib "eagle-import") (part "C-USCHIP-0805(2012-METRIC)_"))
    )
    (comp (ref "J1")
      (value "FH12-22S-0.5SH(55)CONN_FH12-22S-0.5SH(55)_HIR")
      (footprint "eagle-import:CONN_FH12-22S-0.5SH(55)_HIR")
      (fields
        (field (name "MANUFACTURER_PART_NUMBER") "FH12-22S-0.5SH(55)")
        (field (name "COPYRIGHT") "Copyright (C) 2025 Ultra Librarian. All rights reserved.")
      )
      (libsource (lib "eagle-import") (part "FH12-22S-0.5SH(55)CONN_FH12-22S-0.5SH(55)_HIR"))
    )
    (comp (ref "J2")
      (value "HD05-19-TH-TR")
      (footprint "eagle-import:SAMESKY_HD05-19-TH-TR")
      (fields (field (name "MANUFACTURER") "Same Sky"))
      (libsource (lib "eagle-import") (part "HD05-19-TH-TR"))
    )
    (comp (ref "J3")
      (value "HD05-19-TH-TR")
      (footprint "eagle-import:SAMESKY_HD05-19-TH-TR")
      (fields (field (name "MANUFACTURER") "Same Sky"))
      (libsource (lib "eagle-import") (part "HD05-19-TH-TR"))
    )
    (comp (ref "J14")
      (value "2328702-8")
      (footprint "eagle-import:TE_2328702-8")
      (fields (field (name "MANUFACTURER") "TE Connectivity"))
      (libsource (lib "eagle-import") (part "2328702-8"))
    )
    (comp (ref "U2")
      (value "RT9742SNGVSOT_42SNGV_RIT")
      (footprint "eagle-import:SOT_42SNGV_RIT")
      (fields
        (field (name "MANUFACTURER_PART_NUMBER") "RT9742SNGV")
        (field (name "COPYRIGHT") "Copyright (C) 2024 Ultra Librarian. All rights reserved.")
      )
      (libsource (lib "eagle-import") (part "RT9742SNGVSOT_42SNGV_RIT"))
    )
    (comp (ref "U8")
      (value "TPD4EUSB30DQAR")
      (footprint "eagle-import:IC_TPD4EUSB30DQAR")
      (fields (field (name "MANUFACTURER") "Texas Instruments"))
      (libsource (lib "eagle-import") (part "TPD4EUSB30DQAR"))
    )
    (comp (ref "U9")
      (value "TPD4EUSB30DQAR")
      (footprint "eagle-import:IC_TPD4EUSB30DQAR")
      (fields (field (name "MANUFACTURER") "Texas Instruments"))
      (libsource (lib "eagle-import") (part "TPD4EUSB30DQAR"))
    )
    (comp (ref "U10")
      (value "TPD4EUSB30DQAR")
      (footprint "eagle-import:IC_TPD4EUSB30DQAR")
      (fields (field (name "MANUFACTURER") "Texas Instruments"))
      (libsource (lib "eagle-import") (part "TPD4EUSB30DQAR"))
    )
    (comp (ref "U11")
      (value "TPD4EUSB30DQAR")
      (footprint "eagle-import:IC_TPD4EUSB30DQAR")
      (fields (field (name "MANUFACTURER") "Texas Instruments"))
      (libsource (lib "eagle-import") (part "TPD4EUSB30DQAR"))
    )
    (comp (ref "C14")
      (value "10uF")
      (footprint "eagle-import:CAPC3216X135")
      (libsource (lib "eagle-import") (part "C-USCHIP-1206(3216-METRIC)_"))
    )
    (comp (ref "C15")
      (value "10uF")
      (footprint "eagle-import:CAPC3216X135")
      (libsource (lib "eagle-import") (part "C-USCHIP-1206(3216-METRIC)_"))
    )
    (comp (ref "C16")
      (value "10uF")
      (footprint "eagle-import:CAPC3216X135")
      (libsource (lib "eagle-import") (part "C-USCHIP-1206(3216-METRIC)_"))
    )
    (comp (ref "C17")
      (value "10uF")
      (footprint "eagle-import:CAPC3216X135")
      (libsource (lib "eagle-import") (part "C-USCHIP-1206(3216-METRIC)_"))
    )
    (comp (ref "C18")
      (value "100uF")
      (footprint "eagle-import:CAPMP3528X210N")
      (libsource (lib "eagle-import") (part "C-POL-USTANTALUM-1411(3528-METRIC)_"))
    )
    (comp (ref "D1")
      (value "TPD2EUSB30DRTR")
      (footprint "eagle-import:SOTFL35P100X50-3N")
      (libsource (lib "eagle-import") (part "TPD2EUSB30DRTR"))
    )
    (comp (ref "D2")
      (value "TPD2EUSB30DRTR")
      (footprint "eagle-import:SOTFL35P100X50-3N")
      (libsource (lib "eagle-import") (part "TPD2EUSB30DRTR"))
    )
    (comp (ref "D3")
      (value "TPD2EUSB30DRTR")
      (footprint "eagle-import:SOTFL35P100X50-3N")
      (libsource (lib "eagle-import") (part "TPD2EUSB30DRTR"))
    )
    (comp (ref "D4")
      (value "TPD2EUSB30DRTR")
      (footprint "eagle-import:SOTFL35P100X50-3N")
      (libsource (lib "eagle-import") (part "TPD2EUSB30DRTR"))
    )
    (comp (ref "D5")
      (value "TPD2EUSB30DRTR")
      (footprint "eagle-import:SOTFL35P100X50-3N")
      (libsource (lib "eagle-import") (part "TPD2EUSB30DRTR"))
    )
    (comp (ref "J4")
      (value "614104190121")
      (footprint "eagle-import:614104190121")
      (libsource (lib "eagle-import") (part "614104190121"))
    )
    (comp (ref "J5")
      (value "UJ20-C-R-G-TH-2-P14-TR")
      (footprint "eagle-import:SAMESKY_UJ20-C-R-G-TH-2-P14-TR")
      (fields (field (name "MANUFACTURER") "Same Sky"))
      (libsource (lib "eagle-import") (part "UJ20-C-R-G-TH-2-P14-TR"))
    )
    (comp (ref "J6")
      (value "UJ20-C-R-G-TH-2-P14-TR")
      (footprint "eagle-import:SAMESKY_UJ20-C-R-G-TH-2-P14-TR")
      (fields (field (name "MANUFACTURER") "Same Sky"))
      (libsource (lib "eagle-import") (part "UJ20-C-R-G-TH-2-P14-TR"))
    )
    (comp (ref "J9")
      (value "UJ20-C-R-G-TH-2-P14-TR")
      (footprint "eagle-import:SAMESKY_UJ20-C-R-G-TH-2-P14-TR")
      (fields (field (name "MANUFACTURER") "Same Sky"))
      (libsource (lib "eagle-import") (part "UJ20-C-R-G-TH-2-P14-TR"))
    )
    (comp (ref "J11")
      (value "UJ20-C-R-G-TH-2-P14-TR")
      (footprint "eagle-import:SAMESKY_UJ20-C-R-G-TH-2-P14-TR")
      (fields (field (name "MANUFACTURER") "Same Sky"))
      (libsource (lib "eagle-import") (part "UJ20-C-R-G-TH-2-P14-TR"))
    )
    (comp (ref "R4")
      (value "5.1K")
      (footprint "eagle-import:RESC2012X65")
      (libsource (lib "eagle-import") (part "R-USCHIP-0805(2012-METRIC)_"))
    )
    (comp (ref "R5")
      (value "5.1K")
      (footprint "eagle-import:RESC2012X65")
      (libsource (lib "eagle-import") (part "R-USCHIP-0805(2012-METRIC)_"))
    )
    (comp (ref "R6")
      (value "10K")
      (footprint "eagle-import:RESC2012X65")
      (libsource (lib "eagle-import") (part "R-USCHIP-0805(2012-METRIC)_"))
    )
    (comp (ref "R8")
      (value "5.1K")
      (footprint "eagle-import:RESC2012X65")
      (libsource (lib "eagle-import") (part "R-USCHIP-0805(2012-METRIC)_"))
    )
    (comp (ref "R9")
      (value "5.1K")
      (footprint "eagle-import:RESC2012X65")
      (libsource (lib "eagle-import") (part "R-USCHIP-0805(2012-METRIC)_"))
    )
    (comp (ref "R15")
      (value "15K")
      (footprint "eagle-import:RESC2012X65")
      (libsource (lib "eagle-import") (part "R-USCHIP-0805(2012-METRIC)_"))
    )
    (comp (ref "R16")
      (value "10K")
      (footprint "eagle-import:RESC2012X65")
      (libsource (lib "eagle-import") (part "R-USCHIP-0805(2012-METRIC)_"))
    )
    (comp (ref "R20")
      (value "56K")
      (footprint "eagle-import:RESC2012X65")
      (libsource (lib "eagle-import") (part "R-USCHIP-0805(2012-METRIC)_"))
    )
    (comp (ref "R21")
      (value "56K")
      (footprint "eagle-import:RESC2012X65")
      (libsource (lib "eagle-import") (part "R-USCHIP-0805(2012-METRIC)_"))
    )
    (comp (ref "R22")
      (value "56K")
      (footprint "eagle-import:RESC2012X65")
      (libsource (lib "eagle-import") (part "R-USCHIP-0805(2012-METRIC)_"))
    )
    (comp (ref "R23")
      (value "56K")
      (footprint "eagle-import:RESC2012X65")
      (libsource (lib "eagle-import") (part "R-USCHIP-0805(2012-METRIC)_"))
    )
    (comp (ref "R24")
      (value "2.2K")
      (footprint "eagle-import:RESC2012X65")
      (libsource (lib "eagle-import") (part "R-USCHIP-0805(2012-METRIC)_"))
    )
    (comp (ref "R25")
      (value "2.2K")
      (footprint "eagle-import:RESC2012X65")
      (libsource (lib "eagle-import") (part "R-USCHIP-0805(2012-METRIC)_"))
    )
    (comp (ref "TP11")
      (value "TPB1,27")
      (footprint "eagle-import:B1,27")
      (libsource (lib "eagle-import") (part "TPB1,27"))
    )
    (comp (ref "TP12")
      (value "TPB1,27")
      (footprint "eagle-import:B1,27")
      (libsource (lib "eagle-import") (part "TPB1,27"))
    )
    (comp (ref "U3")
      (value "AP22653W6-7")
      (footprint "eagle-import:SOT95P280X145-6N")
      (fields (field (name "MANUFACTURER") "Diodes Inc."))
      (libsource (lib "eagle-import") (part "AP22653W6-7"))
    )
    (comp (ref "U5")
      (value "FSUSB42MUX")
      (footprint "eagle-import:SOP50P490X110-10N")
      (fields (field (name "MANUFACTURER") "ON Semiconductor"))
      (libsource (lib "eagle-import") (part "FSUSB42MUX"))
    )
    (comp (ref "J12")
      (value "S2B-XH-A")
      (footprint "eagle-import:S2B-XH-A")
      (fields (field (name "MANUFACTURER") "JST Sales America Inc. ") (field (name "MPN") "S2B-XH-A-1"))
      (libsource (lib "eagle-import") (part "S2B-XH-A"))
    )
    (comp (ref "J13")
      (value "S2B-XH-A")
      (footprint "eagle-import:S2B-XH-A")
      (fields (field (name "MANUFACTURER") "JST Sales America Inc. ") (field (name "MPN") "S2B-XH-A-1"))
      (libsource (lib "eagle-import") (part "S2B-XH-A"))
    )
    (comp (ref "J16")
      (value "M55-7011242R")
      (footprint "eagle-import:HARWIN_M55-7011242R")
      (fields (field (name "MANUFACTURER") "Harwin"))
      (libsource (lib "eagle-import") (part "M55-7011242R"))
    )
    (comp (ref "J18")
      (value "61201621721")
      (footprint "eagle-import:61201621721")
      (libsource (lib "eagle-import") (part "6120XX21721_61201621721"))
    )
    (comp (ref "J19")
      (value "61201621721")
      (footprint "eagle-import:61201621721")
      (libsource (lib "eagle-import") (part "6120XX21721_61201621721"))
    )
    (comp (ref "J21")
      (value "M55-7011242R")
      (footprint "eagle-import:HARWIN_M55-7011242R")
      (fields (field (name "MANUFACTURER") "Harwin"))
      (libsource (lib "eagle-import") (part "M55-7011242R"))
    )
    (comp (ref "R33")
      (value "10K")
      (footprint "eagle-import:RESC2012X65")
      (libsource (lib "eagle-import") (part "R-USCHIP-0805(2012-METRIC)_"))
    )
    (comp (ref "R34")
      (value "10K")
      (footprint "eagle-import:RESC2012X65")
      (libsource (lib "eagle-import") (part "R-USCHIP-0805(2012-METRIC)_"))
    )
    (comp (ref "TP9")
      (value "TPB1,27")
      (footprint "eagle-import:B1,27")
      (libsource (lib "eagle-import") (part "TPB1,27"))
    )
    (comp (ref "TP10")
      (value "TPB1,27")
      (footprint "eagle-import:B1,27")
      (libsource (lib "eagle-import") (part "TPB1,27"))
    )
    (comp (ref "TP13")
      (value "TPB1,27")
      (footprint "eagle-import:B1,27")
      (libsource (lib "eagle-import") (part "TPB1,27"))
    )
    (comp (ref "TP14")
      (value "TPB1,27")
      (footprint "eagle-import:B1,27")
      (libsource (lib "eagle-import") (part "TPB1,27"))
    )
    (comp (ref "U$1")
      (value "X1203")
      (footprint "eagle-import:X1203")
      (libsource (lib "eagle-import") (part "X1203"))
    )
  )
  (nets
    (net (code "1") (name "5V") (class "Default")
      (node (ref "C14") (pin "1") (pinfunction "1_1") (pintype "passive"))
      (node (ref "C19") (pin "1") (pinfunction "1_1") (pintype "passive"))
      (node (ref "C2") (pin "2") (pinfunction "2_2") (pintype "passive"))
      (node (ref "C20") (pin "1") (pinfunction "1_1") (pintype "passive"))
      (node (ref "C21") (pin "1") (pinfunction "1_1") (pintype "passive"))
      (node (ref "C51") (pin "1") (pinfunction "1_1") (pintype "passive"))
      (node (ref "C52") (pin "1") (pinfunction "1_1") (pintype "passive"))
      (node (ref "J12") (pin "2") (pinfunction "2_2") (pintype "passive"))
      (node (ref "J13") (pin "2") (pinfunction "2_2") (pintype "passive"))
      (node (ref "J14") (pin "5") (pinfunction "5_5") (pintype "passive"))
      (node (ref "J14") (pin "6") (pinfunction "6_6") (pintype "passive"))
      (node (ref "J14") (pin "7") (pinfunction "7_7") (pintype "passive"))
      (node (ref "J14") (pin "8") (pinfunction "8_8") (pintype "passive"))
      (node (ref "J18") (pin "1") (pinfunction "1_1") (pintype "passive"))
      (node (ref "J19") (pin "1") (pinfunction "1_1") (pintype "passive"))
      (node (ref "J21") (pin "A3") (pinfunction "A3_A3") (pintype "passive"))
      (node (ref "J21") (pin "A4") (pinfunction "A4_A4") (pintype "passive"))
      (node (ref "J8") (pin "1") (pinfunction "1_1") (pintype "passive"))
      (node (ref "R20") (pin "1") (pinfunction "1_1") (pintype "passive"))
      (node (ref "R21") (pin "1") (pinfunction "1_1") (pintype "passive"))
      (node (ref "R22") (pin "1") (pinfunction "1_1") (pintype "passive"))
      (node (ref "R23") (pin "1") (pinfunction "1_1") (pintype "passive"))
      (node (ref "R29") (pin "2") (pinfunction "2_2") (pintype "passive"))
      (node (ref "R31") (pin "2") (pinfunction "2_2") (pintype "passive"))
      (node (ref "TP1") (pin "TP") (pinfunction "TP_TP") (pintype "input"))
      (node (ref "U$1") (pin "5V$1") (pinfunction "5V_5V$1") (pintype "power_in"))
      (node (ref "U$1") (pin "5V$2") (pinfunction "5V_5V$2") (pintype "power_in"))
      (node (ref "U1") (pin "77") (pinfunction "+5V(INPUT)_77") (pintype "power_in"))
      (node (ref "U1") (pin "79") (pinfunction "+5V(INPUT)_79") (pintype "power_in"))
      (node (ref "U1") (pin "81") (pinfunction "+5V(INPUT)_81") (pintype "power_in"))
      (node (ref "U1") (pin "83") (pinfunction "+5V(INPUT)_83") (pintype "power_in"))
      (node (ref "U1") (pin "85") (pinfunction "+5V(INPUT)_85") (pintype "power_in"))
      (node (ref "U1") (pin "87") (pinfunction "+5V(INPUT)_87") (pintype "power_in"))
      (node (ref "U12") (pin "3") (pinfunction "3_3") (pintype "passive"))
      (node (ref "U14") (pin "11") (pinfunction "PVDD_11") (pintype "power_in"))
      (node (ref "U14") (pin "12") (pinfunction "PVDD_12") (pintype "power_in"))
      (node (ref "U2") (pin "1") (pinfunction "VIN_1") (pintype "passive"))
      (node (ref "U3") (pin "1") (pinfunction "IN_1") (pintype "input"))
    )
    (net (code "2") (name "AUDIO_L") (class "Default")
      (node (ref "C38") (pin "1") (pinfunction "1_1") (pintype "passive"))
      (node (ref "C41") (pin "1") (pinfunction "1_1") (pintype "passive"))
      (node (ref "C47") (pin "1") (pinfunction "1_1") (pintype "passive"))
      (node (ref "R26") (pin "1") (pinfunction "1_1") (pintype "passive"))
    )
    (net (code "3") (name "AUDIO_R") (class "Default")
      (node (ref "C39") (pin "1") (pinfunction "1_1") (pintype "passive"))
      (node (ref "C40") (pin "1") (pinfunction "1_1") (pintype "passive"))
      (node (ref "C48") (pin "1") (pinfunction "1_1") (pintype "passive"))
      (node (ref "R27") (pin "1") (pinfunction "1_1") (pintype "passive"))
    )
    (net (code "4") (name "AVDD") (class "Default")
      (node (ref "C32") (pin "1") (pinfunction "1_1") (pintype "passive"))
      (node (ref "C33") (pin "1") (pinfunction "1_1") (pintype "passive"))
      (node (ref "C34") (pin "1") (pinfunction "1_1") (pintype "passive"))
      (node (ref "C35") (pin "1") (pinfunction "1_1") (pintype "passive"))
      (node (ref "FB1") (pin "1") (pinfunction "1_1") (pintype "passive"))
      (node (ref "U13") (pin "1") (pinfunction "CPVDD_1") (pintype "power_in"))
      (node (ref "U13") (pin "8") (pinfunction "AVDD_8") (pintype "power_in"))
    )
    (net (code "5") (name "BT_~{DISABLE}") (class "Default")
      (node (ref "J21") (pin "B2") (pinfunction "B2_B2") (pintype "passive"))
      (node (ref "U1") (pin "91") (pinfunction "BT_~{DISABLE}_91") (pintype "input"))
    )
    (net (code "6") (name "CAM_GPIO") (class "Default")
      (node (ref "J1") (pin "17") (pinfunction "17_17") (pintype "passive"))
      (node (ref "U1") (pin "97") (pinfunction "CAM_GPIO_97") (pintype "bidirectional"))
    )
    (net (code "7") (name "CAM_GPIO1") (class "Default")
      (node (ref "J1") (pin "18") (pinfunction "18_18") (pintype "passive"))
      (node (ref "U1") (pin "100") (pinfunction "CAM_GPIO1_100") (pintype "output"))
    )
    (net (code "8") (name "CC1") (class "Default")
      (node (ref "U1") (pin "94") (pinfunction "CC1_94") (pintype "bidirectional"))
    )
    (net (code "9") (name "CC2") (class "Default")
      (node (ref "U1") (pin "96") (pinfunction "CC2_96") (pintype "bidirectional"))
    )
    (net (code "10") (name "CM5_1.8V") (class "Default")
      (node (ref "JP1") (pin "1") (pinfunction "1_1") (pintype "passive"))
      (node (ref "TP3") (pin "TP") (pinfunction "TP_TP") (pintype "input"))
      (node (ref "U1") (pin "88") (pinfunction "CM5_1.8V(OUTPUT)_88") (pintype "power_in"))
      (node (ref "U1") (pin "90") (pinfunction "CM5_1.8V(OUTPUT)_90") (pintype "power_in"))
    )
    (net (code "11") (name "CM5_3.3V") (class "Default")
      (node (ref "C10") (pin "1") (pinfunction "1_1") (pintype "passive"))
      (node (ref "C3") (pin "1") (pinfunction "1_1") (pintype "passive"))
      (node (ref "C30") (pin "1") (pinfunction "1_1") (pintype "passive"))
      (node (ref "C31") (pin "1") (pinfunction "1_1") (pintype "passive"))
      (node (ref "C4") (pin "1") (pinfunction "1_1") (pintype "passive"))
      (node (ref "C45") (pin "1") (pinfunction "1_1") (pintype "passive"))
      (node (ref "C46") (pin "1") (pinfunction "1_1") (pintype "passive"))
      (node (ref "C5") (pin "1") (pinfunction "1_1") (pintype "passive"))
      (node (ref "C6") (pin "1") (pinfunction "1_1") (pintype "passive"))
      (node (ref "C7") (pin "1") (pinfunction "1_1") (pintype "passive"))
      (node (ref "C8") (pin "1") (pinfunction "1_1") (pintype "passive"))
      (node (ref "C9") (pin "1") (pinfunction "1_1") (pintype "passive"))
      (node (ref "FB1") (pin "2") (pinfunction "2_2") (pintype "passive"))
      (node (ref "IC1") (pin "14") (pinfunction "VDD_14") (pintype "power_in"))
      (node (ref "J1") (pin "22") (pinfunction "22_22") (pintype "passive"))
      (node (ref "J10") (pin "14") (pinfunction "GA_1_14") (pintype "passive"))
      (node (ref "J10") (pin "16") (pinfunction "GA_2_16") (pintype "passive"))
      (node (ref "JP1") (pin "3") (pinfunction "3_3") (pintype "passive"))
      (node (ref "JP2") (pin "3") (pinfunction "3_3") (pintype "passive"))
      (node (ref "JP3") (pin "1") (pinfunction "1_1") (pintype "passive"))
      (node (ref "R1") (pin "2") (pinfunction "2_2") (pintype "passive"))
      (node (ref "R28") (pin "2") (pinfunction "2_2") (pintype "passive"))
      (node (ref "R32") (pin "2") (pinfunction "2_2") (pintype "passive"))
      (node (ref "R33") (pin "2") (pinfunction "2_2") (pintype "passive"))
      (node (ref "R34") (pin "2") (pinfunction "2_2") (pintype "passive"))
      (node (ref "R7") (pin "1") (pinfunction "1_1") (pintype "passive"))
      (node (ref "TP13") (pin "TP") (pinfunction "TP_TP") (pintype "input"))
      (node (ref "TP2") (pin "TP") (pinfunction "TP_TP") (pintype "input"))
      (node (ref "U$1") (pin "3V3_DET") (pinfunction "3V3_DET_3V3_DET") (pintype "bidirectional"))
      (node (ref "U1") (pin "84") (pinfunction "CM5_3.3V(OUTPUT)_84") (pintype "power_in"))
      (node (ref "U1") (pin "86") (pinfunction "CM5_3.3V(OUTPUT)_86") (pintype "power_in"))
      (node (ref "U13") (pin "20") (pinfunction "DVDD_20") (pintype "power_in"))
      (node (ref "U4") (pin "10") (pinfunction "VDDA33_3_10") (pintype "power_in"))
      (node (ref "U4") (pin "15") (pinfunction "VDD33_2_15") (pintype "power_in"))
      (node (ref "U4") (pin "23") (pinfunction "VDD33_23") (pintype "power_in"))
      (node (ref "U4") (pin "27") (pinfunction "VBUS_DET_27") (pintype "passive"))
      (node (ref "U4") (pin "29") (pinfunction "VDDA33_4_29") (pintype "power_in"))
      (node (ref "U4") (pin "36") (pinfunction "VDDA33_36") (pintype "power_in"))
      (node (ref "U4") (pin "5") (pinfunction "VDDA33_2_5") (pintype "power_in"))
      (node (ref "U5") (pin "1") (pinfunction "VCC_1") (pintype "power_in"))
    )
    (net (code "12") (name "CM5_VBAT") (class "Default")
      (node (ref "BT1") (pin "P") (pinfunction "+_P") (pintype "bidirectional"))
      (node (ref "BT1") (pin "P1") (pinfunction "+_P1") (pintype "bidirectional"))
      (node (ref "U1") (pin "76") (pinfunction "VBAT_76") (pintype "power_in"))
    )
    (net (code "13") (name "EEPROM_~{WP}") (class "Default")
      (node (ref "J21") (pin "B6") (pinfunction "B6_B6") (pintype "passive"))
      (node (ref "U1") (pin "20") (pinfunction "EEPROM_~{WP}_20") (pintype "bidirectional"))
    )
    (net (code "14") (name "ETHERNET_PAIR0_N") (class "Default")
      (node (ref "J10") (pin "2") (pinfunction "TRD1-_2") (pintype "passive"))
      (node (ref "U1") (pin "10") (pinfunction "ETHERNET_PAIR0_N_10") (pintype "bidirectional"))
      (node (ref "U7") (pin "2") (pinfunction "D1-_2") (pintype "bidirectional"))
      (node (ref "U7") (pin "9") (pinfunction "D1-_9") (pintype "bidirectional"))
    )
    (net (code "15") (name "ETHERNET_PAIR0_P") (class "Default")
      (node (ref "J10") (pin "1") (pinfunction "TRD1+_1") (pintype "passive"))
      (node (ref "U1") (pin "12") (pinfunction "ETHERNET_PAIR0_P_12") (pintype "bidirectional"))
      (node (ref "U7") (pin "1") (pinfunction "D1+_1") (pintype "bidirectional"))
      (node (ref "U7") (pin "10") (pinfunction "D1+_10") (pintype "bidirectional"))
    )
    (net (code "16") (name "ETHERNET_PAIR1_N") (class "Default")
      (node (ref "J10") (pin "5") (pinfunction "TRD2-_5") (pintype "passive"))
      (node (ref "U1") (pin "6") (pinfunction "ETHERNET_PAIR1_N_6") (pintype "bidirectional"))
      (node (ref "U7") (pin "5") (pinfunction "D2-_5") (pintype "bidirectional"))
      (node (ref "U7") (pin "6") (pinfunction "D2-_6") (pintype "bidirectional"))
    )
    (net (code "17") (name "ETHERNET_PAIR1_P") (class "Default")
      (node (ref "J10") (pin "4") (pinfunction "TRD2+_4") (pintype "passive"))
      (node (ref "U1") (pin "4") (pinfunction "ETHERNET_PAIR1_P_4") (pintype "bidirectional"))
      (node (ref "U7") (pin "4") (pinfunction "D2+_4") (pintype "bidirectional"))
      (node (ref "U7") (pin "7") (pinfunction "D2+_7") (pintype "bidirectional"))
    )
    (net (code "18") (name "ETHERNET_PAIR2_N") (class "Default")
      (node (ref "J10") (pin "8") (pinfunction "TRD3-_8") (pintype "passive"))
      (node (ref "U1") (pin "9") (pinfunction "ETHERNET_PAIR2_N_9") (pintype "bidirectional"))
      (node (ref "U6") (pin "2") (pinfunction "D1-_2") (pintype "bidirectional"))
      (node (ref "U6") (pin "9") (pinfunction "D1-_9") (pintype "bidirectional"))
    )
    (net (code "19") (name "ETHERNET_PAIR2_P") (class "Default")
      (node (ref "J10") (pin "7") (pinfunction "TRD3+_7") (pintype "passive"))
      (node (ref "U1") (pin "11") (pinfunction "ETHERNET_PAIR2_P_11") (pintype "bidirectional"))
      (node (ref "U6") (pin "1") (pinfunction "D1+_1") (pintype "bidirectional"))
      (node (ref "U6") (pin "10") (pinfunction "D1+_10") (pintype "bidirectional"))
    )
    (net (code "20") (name "ETHERNET_PAIR3_N") (class "Default")
      (node (ref "J10") (pin "11") (pinfunction "TRD4-_11") (pintype "passive"))
      (node (ref "U1") (pin "5") (pinfunction "ETHERNET_PAIR3_N_5") (pintype "bidirectional"))
      (node (ref "U6") (pin "5") (pinfunction "D2-_5") (pintype "bidirectional"))
      (node (ref "U6") (pin "6") (pinfunction "D2-_6") (pintype "bidirectional"))
    )
    (net (code "21") (name "ETHERNET_PAIR3_P") (class "Default")
      (node (ref "J10") (pin "10") (pinfunction "TRD4+_10") (pintype "passive"))
      (node (ref "U1") (pin "3") (pinfunction "ETHERNET_PAIR3_P_3") (pintype "bidirectional"))
      (node (ref "U6") (pin "4") (pinfunction "D2+_4") (pintype "bidirectional"))
      (node (ref "U6") (pin "7") (pinfunction "D2+_7") (pintype "bidirectional"))
    )
    (net (code "22") (name "ETHERNET_SYNC_OUT") (class "Default")
      (node (ref "U1") (pin "18") (pinfunction "ETHERNET_SYNC_OUT_18") (pintype "output"))
    )
    (net (code "23") (name "ETHERNET_~{LEDG}") (class "Default")
      (node (ref "R3") (pin "1") (pinfunction "1_1") (pintype "passive"))
      (node (ref "U1") (pin "17") (pinfunction "ETHERNET_~{LED2}_17") (pintype "output"))
    )
    (net (code "24") (name "ETHERNET_~{LEDY}") (class "Default")
      (node (ref "R2") (pin "1") (pinfunction "1_1") (pintype "passive"))
      (node (ref "U1") (pin "15") (pinfunction "ETHERNET_~{LED3}_15") (pintype "output"))
    )
    (net (code "25") (name "FAN_PWM") (class "Default")
      (node (ref "J8") (pin "2") (pinfunction "2_2") (pintype "passive"))
      (node (ref "R1") (pin "1") (pinfunction "1_1") (pintype "passive"))
      (node (ref "U1") (pin "19") (pinfunction "FAN_PWM_19") (pintype "output"))
    )
    (net (code "26") (name "FAN_TACHO") (class "Default")
      (node (ref "J8") (pin "4") (pinfunction "4_4") (pintype "passive"))
      (node (ref "U1") (pin "16") (pinfunction "FAN_TACHO_16") (pintype "input"))
    )
    (net (code "27") (name "FB") (class "Default")
      (node (ref "C26") (pin "2") (pinfunction "2_2") (pintype "passive"))
      (node (ref "R18") (pin "1") (pinfunction "1_1") (pintype "passive"))
      (node (ref "R19") (pin "2") (pinfunction "2_2") (pintype "passive"))
      (node (ref "U12") (pin "1") (pinfunction "1_1") (pintype "passive"))
    )
    (net (code "28") (name "GND") (class "Default")
      (node (ref "BT1") (pin "N") (pinfunction "-_N") (pintype "bidirectional"))
      (node (ref "C1") (pin "1") (pinfunction "1_1") (pintype "passive"))
      (node (ref "C10") (pin "2") (pinfunction "2_2") (pintype "passive"))
      (node (ref "C11") (pin "2") (pinfunction "2_2") (pintype "passive"))
      (node (ref "C12") (pin "2") (pinfunction "2_2") (pintype "passive"))
      (node (ref "C13") (pin "2") (pinfunction "2_2") (pintype "passive"))
      (node (ref "C14") (pin "2") (pinfunction "2_2") (pintype "passive"))
      (node (ref "C15") (pin "2") (pinfunction "2_2") (pintype "passive"))
      (node (ref "C16") (pin "2") (pinfunction "2_2") (pintype "passive"))
      (node (ref "C17") (pin "2") (pinfunction "2_2") (pintype "passive"))
      (node (ref "C18") (pin "2") (pinfunction "-_2") (pintype "passive"))
      (node (ref "C19") (pin "2") (pinfunction "2_2") (pintype "passive"))
      (node (ref "C2") (pin "1") (pinfunction "1_1") (pintype "passive"))
      (node (ref "C20") (pin "2") (pinfunction "2_2") (pintype "passive"))
      (node (ref "C21") (pin "2") (pinfunction "2_2") (pintype "passive"))
      (node (ref "C22") (pin "2") (pinfunction "2_2") (pintype "passive"))
      (node (ref "C23") (pin "2") (pinfunction "2_2") (pintype "passive"))
      (node (ref "C24") (pin "2") (pinfunction "2_2") (pintype "passive"))
      (node (ref "C25") (pin "2") (pinfunction "2_2") (pintype "passive"))
      (node (ref "C27") (pin "2") (pinfunction "2_2") (pintype "passive"))
      (node (ref "C28") (pin "2") (pinfunction "2_2") (pintype "passive"))
      (node (ref "C29") (pin "2") (pinfunction "2_2") (pintype "passive"))
      (node (ref "C3") (pin "2") (pinfunction "2_2") (pintype "passive"))
      (node (ref "C30") (pin "2") (pinfunction "2_2") (pintype "passive"))
      (node (ref "C31") (pin "2") (pinfunction "2_2") (pintype "passive"))
      (node (ref "C32") (pin "2") (pinfunction "2_2") (pintype "passive"))
      (node (ref "C33") (pin "2") (pinfunction "2_2") (pintype "passive"))
      (node (ref "C34") (pin "2") (pinfunction "2_2") (pintype "passive"))
      (node (ref "C35") (pin "2") (pinfunction "2_2") (pintype "passive"))
      (node (ref "C37") (pin "2") (pinfunction "2_2") (pintype "passive"))
      (node (ref "C38") (pin "2") (pinfunction "2_2") (pintype "passive"))
      (node (ref "C39") (pin "2") (pinfunction "2_2") (pintype "passive"))
      (node (ref "C4") (pin "2") (pinfunction "2_2") (pintype "passive"))
      (node (ref "C42") (pin "1") (pinfunction "1_1") (pintype "passive"))
      (node (ref "C43") (pin "2") (pinfunction "2_2") (pintype "passive"))
      (node (ref "C45") (pin "2") (pinfunction "2_2") (pintype "passive"))
      (node (ref "C46") (pin "2") (pinfunction "2_2") (pintype "passive"))
      (node (ref "C49") (pin "1") (pinfunction "1_1") (pintype "passive"))
      (node (ref "C5") (pin "2") (pinfunction "2_2") (pintype "passive"))
      (node (ref "C50") (pin "1") (pinfunction "1_1") (pintype "passive"))
      (node (ref "C51") (pin "2") (pinfunction "2_2") (pintype "passive"))
      (node (ref "C52") (pin "2") (pinfunction "2_2") (pintype "passive"))
      (node (ref "C6") (pin "2") (pinfunction "2_2") (pintype "passive"))
      (node (ref "C7") (pin "2") (pinfunction "2_2") (pintype "passive"))
      (node (ref "C8") (pin "2") (pinfunction "2_2") (pintype "passive"))
      (node (ref "C9") (pin "2") (pinfunction "2_2") (pintype "passive"))
      (node (ref "D1") (pin "3") (pinfunction "GND_3") (pintype "power_in"))
      (node (ref "D2") (pin "3") (pinfunction "GND_3") (pintype "power_in"))
      (node (ref "D3") (pin "3") (pinfunction "GND_3") (pintype "power_in"))
      (node (ref "D4") (pin "3") (pinfunction "GND_3") (pintype "power_in"))
      (node (ref "D5") (pin "3") (pinfunction "GND_3") (pintype "power_in"))
      (node (ref "IC1") (pin "10") (pinfunction "PGND_10") (pintype "power_in"))
      (node (ref "IC1") (pin "15") (pinfunction "SGND_15") (pintype "power_in"))
      (node (ref "IC1") (pin "2") (pinfunction "INL+_2") (pintype "input"))
      (node (ref "IC1") (pin "3") (pinfunction "INR+_3") (pintype "input"))
      (node (ref "J1") (pin "1") (pinfunction "1_1") (pintype "passive"))
      (node (ref "J1") (pin "10") (pinfunction "10_10") (pintype "passive"))
      (node (ref "J1") (pin "13") (pinfunction "13_13") (pintype "passive"))
      (node (ref "J1") (pin "16") (pinfunction "16_16") (pintype "passive"))
      (node (ref "J1") (pin "19") (pinfunction "19_19") (pintype "passive"))
      (node (ref "J1") (pin "4") (pinfunction "4_4") (pintype "passive"))
      (node (ref "J1") (pin "7") (pinfunction "7_7") (pintype "passive"))
      (node (ref "J10") (pin "S1") (pinfunction "SHIELD_S1") (pintype "passive"))
      (node (ref "J10") (pin "S2") (pinfunction "SHIELD_S2") (pintype "passive"))
      (node (ref "J10") (pin "S3") (pinfunction "SHIELD_S3") (pintype "passive"))
      (node (ref "J10") (pin "S4") (pinfunction "SHIELD_S4") (pintype "passive"))
      (node (ref "J11") (pin "A1") (pinfunction "GND_A1") (pintype "power_in"))
      (node (ref "J11") (pin "A12") (pinfunction "GND_A12") (pintype "power_in"))
      (node (ref "J11") (pin "B1") (pinfunction "GND_B1") (pintype "power_in"))
      (node (ref "J11") (pin "B12") (pinfunction "GND_B12") (pintype "power_in"))
      (node (ref "J11") (pin "SH1") (pinfunction "SHIELD_SH1") (pintype "passive"))
      (node (ref "J11") (pin "SH2") (pinfunction "SHIELD_SH2") (pintype "passive"))
      (node (ref "J11") (pin "SH3") (pinfunction "SHIELD_SH3") (pintype "passive"))
      (node (ref "J11") (pin "SH4") (pinfunction "SHIELD_SH4") (pintype "passive"))
      (node (ref "J12") (pin "1") (pinfunction "1_1") (pintype "passive"))
      (node (ref "J13") (pin "1") (pinfunction "1_1") (pintype "passive"))
      (node (ref "J14") (pin "1") (pinfunction "1_1") (pintype "passive"))
      (node (ref "J14") (pin "2") (pinfunction "2_2") (pintype "passive"))
      (node (ref "J14") (pin "3") (pinfunction "3_3") (pintype "passive"))
      (node (ref "J14") (pin "4") (pinfunction "4_4") (pintype "passive"))
      (node (ref "J14") (pin "S1") (pinfunction "SHIELD_S1") (pintype "passive"))
      (node (ref "J14") (pin "S2") (pinfunction "SHIELD_S2") (pintype "passive"))
      (node (ref "J16") (pin "A1") (pinfunction "A1_A1") (pintype "passive"))
      (node (ref "J16") (pin "A4") (pinfunction "A4_A4") (pintype "passive"))
      (node (ref "J16") (pin "B4") (pinfunction "B4_B4") (pintype "passive"))
      (node (ref "J17") (pin "1") (pinfunction "1_1") (pintype "passive"))
      (node (ref "J17") (pin "4") (pinfunction "4_4") (pintype "passive"))
      (node (ref "J17") (pin "9") (pinfunction "9_9") (pintype "passive"))
      (node (ref "J18") (pin "2") (pinfunction "2_2") (pintype "passive"))
      (node (ref "J19") (pin "2") (pinfunction "2_2") (pintype "passive"))
      (node (ref "J2") (pin "11") (pinfunction "TMDS_CLOCK_SHIELD_11") (pintype "passive"))
      (node (ref "J2") (pin "17") (pinfunction "DDC/CEC_GROUND_17") (pintype "power_in"))
      (node (ref "J2") (pin "2") (pinfunction "TMDS_DATA2_SHIELD_2") (pintype "passive"))
      (node (ref "J2") (pin "5") (pinfunction "TMDS_DATA1_SHIELD_5") (pintype "passive"))
      (node (ref "J2") (pin "8") (pinfunction "TMDS_DATA0_SHIELD_8") (pintype "passive"))
      (node (ref "J2") (pin "SH1") (pinfunction "SHIELD_SH1") (pintype "passive"))
      (node (ref "J2") (pin "SH2") (pinfunction "SHIELD_SH2") (pintype "passive"))
      (node (ref "J2") (pin "SH3") (pinfunction "SHIELD_SH3") (pintype "passive"))
      (node (ref "J2") (pin "SH4") (pinfunction "SHIELD_SH4") (pintype "passive"))
      (node (ref "J21") (pin "A1") (pinfunction "A1_A1") (pintype "passive"))
      (node (ref "J21") (pin "A2") (pinfunction "A2_A2") (pintype "passive"))
      (node (ref "J3") (pin "11") (pinfunction "TMDS_CLOCK_SHIELD_11") (pintype "passive"))
      (node (ref "J3") (pin "17") (pinfunction "DDC/CEC_GROUND_17") (pintype "power_in"))
      (node (ref "J3") (pin "2") (pinfunction "TMDS_DATA2_SHIELD_2") (pintype "passive"))
      (node (ref "J3") (pin "5") (pinfunction "TMDS_DATA1_SHIELD_5") (pintype "passive"))
      (node (ref "J3") (pin "8") (pinfunction "TMDS_DATA0_SHIELD_8") (pintype "passive"))
      (node (ref "J3") (pin "SH1") (pinfunction "SHIELD_SH1") (pintype "passive"))
      (node (ref "J3") (pin "SH2") (pinfunction "SHIELD_SH2") (pintype "passive"))
      (node (ref "J3") (pin "SH3") (pinfunction "SHIELD_SH3") (pintype "passive"))
      (node (ref "J3") (pin "SH4") (pinfunction "SHIELD_SH4") (pintype "passive"))
      (node (ref "J4") (pin "4") (pinfunction "GND_4") (pintype "passive"))
      (node (ref "J4") (pin "S1") (pinfunction "SHIELD_S1") (pintype "passive"))
      (node (ref "J4") (pin "S2") (pinfunction "SHIELD_S2") (pintype "passive"))
      (node (ref "J5") (pin "A1") (pinfunction "GND_A1") (pintype "power_in"))
      (node (ref "J5") (pin "A12") (pinfunction "GND_A12") (pintype "power_in"))
      (node (ref "J5") (pin "B1") (pinfunction "GND_B1") (pintype "power_in"))
      (node (ref "J5") (pin "B12") (pinfunction "GND_B12") (pintype "power_in"))
      (node (ref "J5") (pin "SH1") (pinfunction "SHIELD_SH1") (pintype "passive"))
      (node (ref "J5") (pin "SH2") (pinfunction "SHIELD_SH2") (pintype "passive"))
      (node (ref "J5") (pin "SH3") (pinfunction "SHIELD_SH3") (pintype "passive"))
      (node (ref "J5") (pin "SH4") (pinfunction "SHIELD_SH4") (pintype "passive"))
      (node (ref "J6") (pin "A1") (pinfunction "GND_A1") (pintype "power_in"))
      (node (ref "J6") (pin "A12") (pinfunction "GND_A12") (pintype "power_in"))
      (node (ref "J6") (pin "B1") (pinfunction "GND_B1") (pintype "power_in"))
      (node (ref "J6") (pin "B12") (pinfunction "GND_B12") (pintype "power_in"))
      (node (ref "J6") (pin "SH1") (pinfunction "SHIELD_SH1") (pintype "passive"))
      (node (ref "J6") (pin "SH2") (pinfunction "SHIELD_SH2") (pintype "passive"))
      (node (ref "J6") (pin "SH3") (pinfunction "SHIELD_SH3") (pintype "passive"))
      (node (ref "J6") (pin "SH4") (pinfunction "SHIELD_SH4") (pintype "passive"))
      (node (ref "J7") (pin "1") (pinfunction "P1_1") (pintype "passive"))
      (node (ref "J7") (pin "15") (pinfunction "P15_15") (pintype "passive"))
      (node (ref "J7") (pin "21") (pinfunction "P21_21") (pintype "passive"))
      (node (ref "J7") (pin "27") (pinfunction "P27_27") (pintype "passive"))
      (node (ref "J7") (pin "3") (pinfunction "P3_3") (pintype "passive"))
      (node (ref "J7") (pin "33") (pinfunction "P33_33") (pintype "passive"))
      (node (ref "J7") (pin "39") (pinfunction "P39_39") (pintype "passive"))
      (node (ref "J7") (pin "45") (pinfunction "P45_45") (pintype "passive"))
      (node (ref "J7") (pin "51") (pinfunction "P51_51") (pintype "passive"))
      (node (ref "J7") (pin "57") (pinfunction "P57_57") (pintype "passive"))
      (node (ref "J7") (pin "59") (pinfunction "P$1_59") (pintype "bidirectional"))
      (node (ref "J7") (pin "60") (pinfunction "P$1_60") (pintype "bidirectional"))
      (node (ref "J7") (pin "61") (pinfunction "P$1_61") (pintype "bidirectional"))
      (node (ref "J7") (pin "71") (pinfunction "P71_71") (pintype "passive"))
      (node (ref "J7") (pin "73") (pinfunction "P73_73") (pintype "passive"))
      (node (ref "J7") (pin "75") (pinfunction "P75_75") (pintype "passive"))
      (node (ref "J7") (pin "9") (pinfunction "P9_9") (pintype "passive"))
      (node (ref "J7") (pin "SH1") (pinfunction "SHIELD_SH1") (pintype "passive"))
      (node (ref "J7") (pin "SH2") (pinfunction "SHIELD_SH2") (pintype "passive"))
      (node (ref "J8") (pin "3") (pinfunction "3_3") (pintype "passive"))
      (node (ref "J9") (pin "A1") (pinfunction "GND_A1") (pintype "power_in"))
      (node (ref "J9") (pin "A12") (pinfunction "GND_A12") (pintype "power_in"))
      (node (ref "J9") (pin "B1") (pinfunction "GND_B1") (pintype "power_in"))
      (node (ref "J9") (pin "B12") (pinfunction "GND_B12") (pintype "power_in"))
      (node (ref "J9") (pin "SH1") (pinfunction "SHIELD_SH1") (pintype "passive"))
      (node (ref "J9") (pin "SH2") (pinfunction "SHIELD_SH2") (pintype "passive"))
      (node (ref "J9") (pin "SH3") (pinfunction "SHIELD_SH3") (pintype "passive"))
      (node (ref "J9") (pin "SH4") (pinfunction "SHIELD_SH4") (pintype "passive"))
      (node (ref "JP2") (pin "1") (pinfunction "1_1") (pintype "passive"))
      (node (ref "JP3") (pin "3") (pinfunction "3_3") (pintype "passive"))
      (node (ref "R10") (pin "1") (pinfunction "1_1") (pintype "passive"))
      (node (ref "R11") (pin "2") (pinfunction "2_2") (pintype "passive"))
      (node (ref "R12") (pin "2") (pinfunction "2_2") (pintype "passive"))
      (node (ref "R13") (pin "2") (pinfunction "2_2") (pintype "passive"))
      (node (ref "R14") (pin "2") (pinfunction "2_2") (pintype "passive"))
      (node (ref "R15") (pin "1") (pinfunction "1_1") (pintype "passive"))
      (node (ref "R17") (pin "2") (pinfunction "2_2") (pintype "passive"))
      (node (ref "R18") (pin "2") (pinfunction "2_2") (pintype "passive"))
      (node (ref "R24") (pin "1") (pinfunction "1_1") (pintype "passive"))
      (node (ref "R25") (pin "1") (pinfunction "1_1") (pintype "passive"))
      (node (ref "R30") (pin "2") (pinfunction "2_2") (pintype "passive"))
      (node (ref "R4") (pin "1") (pinfunction "1_1") (pintype "passive"))
      (node (ref "R5") (pin "1") (pinfunction "1_1") (pintype "passive"))
      (node (ref "R6") (pin "1") (pinfunction "1_1") (pintype "passive"))
      (node (ref "R8") (pin "1") (pinfunction "1_1") (pintype "passive"))
      (node (ref "R9") (pin "1") (pinfunction "1_1") (pintype "passive"))
      (node (ref "TP12") (pin "TP") (pinfunction "TP_TP") (pintype "input"))
      (node (ref "TP14") (pin "TP") (pinfunction "TP_TP") (pintype "input"))
      (node (ref "TP4") (pin "TP") (pinfunction "TP_TP") (pintype "input"))
      (node (ref "TP5") (pin "TP") (pinfunction "TP_TP") (pintype "input"))
      (node (ref "TP6") (pin "TP") (pinfunction "TP_TP") (pintype "input"))
      (node (ref "TP8") (pin "TP") (pinfunction "TP_TP") (pintype "input"))
      (node (ref "U$1") (pin "GND$1") (pinfunction "GND_GND$1") (pintype "power_in"))
      (node (ref "U$1") (pin "GND$2") (pinfunction "GND_GND$2") (pintype "power_in"))
      (node (ref "U$1") (pin "GND$3") (pinfunction "GND_GND$3") (pintype "power_in"))
      (node (ref "U$1") (pin "GND$4") (pinfunction "GND_GND$4") (pintype "power_in"))
      (node (ref "U$1") (pin "GND$5") (pinfunction "GND_GND$5") (pintype "power_in"))
      (node (ref "U$1") (pin "GND$6") (pinfunction "GND_GND$6") (pintype "power_in"))
      (node (ref "U$1") (pin "GND$7") (pinfunction "GND_GND$7") (pintype "power_in"))
      (node (ref "U1") (pin "1") (pinfunction "GND_1") (pintype "power_in"))
      (node (ref "U1") (pin "107") (pinfunction "GND_107") (pintype "power_in"))
      (node (ref "U1") (pin "108") (pinfunction "GND_108") (pintype "power_in"))
      (node (ref "U1") (pin "113") (pinfunction "GND_113") (pintype "power_in"))
      (node (ref "U1") (pin "114") (pinfunction "GND_114") (pintype "power_in"))
      (node (ref "U1") (pin "119") (pinfunction "GND_119") (pintype "power_in"))
      (node (ref "U1") (pin "120") (pinfunction "GND_120") (pintype "power_in"))
      (node (ref "U1") (pin "125") (pinfunction "GND_125") (pintype "power_in"))
      (node (ref "U1") (pin "126") (pinfunction "GND_126") (pintype "power_in"))
      (node (ref "U1") (pin "13") (pinfunction "GND_13") (pintype "power_in"))
      (node (ref "U1") (pin "131") (pinfunction "GND_131") (pintype "power_in"))
      (node (ref "U1") (pin "132") (pinfunction "GND_132") (pintype "power_in"))
      (node (ref "U1") (pin "137") (pinfunction "GND_137") (pintype "power_in"))
      (node (ref "U1") (pin "138") (pinfunction "GND_138") (pintype "power_in"))
      (node (ref "U1") (pin "14") (pinfunction "GND_14") (pintype "power_in"))
      (node (ref "U1") (pin "144") (pinfunction "GND_144") (pintype "power_in"))
      (node (ref "U1") (pin "150") (pinfunction "GND_150") (pintype "power_in"))
      (node (ref "U1") (pin "155") (pinfunction "GND_155") (pintype "power_in"))
      (node (ref "U1") (pin "156") (pinfunction "GND_156") (pintype "power_in"))
      (node (ref "U1") (pin "161") (pinfunction "GND_161") (pintype "power_in"))
      (node (ref "U1") (pin "162") (pinfunction "GND_162") (pintype "power_in"))
      (node (ref "U1") (pin "167") (pinfunction "GND_167") (pintype "power_in"))
      (node (ref "U1") (pin "168") (pinfunction "GND_168") (pintype "power_in"))
      (node (ref "U1") (pin "173") (pinfunction "GND_173") (pintype "power_in"))
      (node (ref "U1") (pin "174") (pinfunction "GND_174") (pintype "power_in"))
      (node (ref "U1") (pin "179") (pinfunction "GND_179") (pintype "power_in"))
      (node (ref "U1") (pin "180") (pinfunction "GND_180") (pintype "power_in"))
      (node (ref "U1") (pin "185") (pinfunction "GND_185") (pintype "power_in"))
      (node (ref "U1") (pin "186") (pinfunction "GND_186") (pintype "power_in"))
      (node (ref "U1") (pin "191") (pinfunction "GND_191") (pintype "power_in"))
      (node (ref "U1") (pin "192") (pinfunction "GND_192") (pintype "power_in"))
      (node (ref "U1") (pin "197") (pinfunction "GND_197") (pintype "power_in"))
      (node (ref "U1") (pin "198") (pinfunction "GND_198") (pintype "power_in"))
      (node (ref "U1") (pin "2") (pinfunction "GND_2") (pintype "power_in"))
      (node (ref "U1") (pin "22") (pinfunction "GND_22") (pintype "power_in"))
      (node (ref "U1") (pin "23") (pinfunction "GND_23") (pintype "power_in"))
      (node (ref "U1") (pin "32") (pinfunction "GND_32") (pintype "power_in"))
      (node (ref "U1") (pin "33") (pinfunction "GND_33") (pintype "power_in"))
      (node (ref "U1") (pin "42") (pinfunction "GND_42") (pintype "power_in"))
      (node (ref "U1") (pin "43") (pinfunction "GND_43") (pintype "power_in"))
      (node (ref "U1") (pin "52") (pinfunction "GND_52") (pintype "power_in"))
      (node (ref "U1") (pin "53") (pinfunction "GND_53") (pintype "power_in"))
      (node (ref "U1") (pin "59") (pinfunction "GND_59") (pintype "power_in"))
      (node (ref "U1") (pin "60") (pinfunction "GND_60") (pintype "power_in"))
      (node (ref "U1") (pin "65") (pinfunction "GND_65") (pintype "power_in"))
      (node (ref "U1") (pin "66") (pinfunction "GND_66") (pintype "power_in"))
      (node (ref "U1") (pin "7") (pinfunction "GND_7") (pintype "power_in"))
      (node (ref "U1") (pin "71") (pinfunction "GND_71") (pintype "power_in"))
      (node (ref "U1") (pin "74") (pinfunction "GND_74") (pintype "power_in"))
      (node (ref "U1") (pin "8") (pinfunction "GND_8") (pintype "power_in"))
      (node (ref "U1") (pin "98") (pinfunction "GND_98") (pintype "power_in"))
      (node (ref "U1") (pin "SH1") (pinfunction "MOUNTING_PADS_SH1") (pintype "passive"))
      (node (ref "U1") (pin "SH2") (pinfunction "MOUNTING_PADS_SH2") (pintype "passive"))
      (node (ref "U1") (pin "SH3") (pinfunction "MOUNTING_PADS_SH3") (pintype "passive"))
      (node (ref "U1") (pin "SH4") (pinfunction "MOUNTING_PADS_SH4") (pintype "passive"))
      (node (ref "U10") (pin "3") (pinfunction "GND_3_3") (pintype "power_in"))
      (node (ref "U10") (pin "8") (pinfunction "GND_8_8") (pintype "power_in"))
      (node (ref "U11") (pin "3") (pinfunction "GND_3_3") (pintype "power_in"))
      (node (ref "U11") (pin "8") (pinfunction "GND_8_8") (pintype "power_in"))
      (node (ref "U12") (pin "4") (pinfunction "4_4") (pintype "passive"))
      (node (ref "U12") (pin "8") (pinfunction "8_8") (pintype "passive"))
      (node (ref "U12") (pin "9") (pinfunction "9_9") (pintype "passive"))
      (node (ref "U13") (pin "10") (pinfunction "DEMP_10") (pintype "input"))
      (node (ref "U13") (pin "11") (pinfunction "FLT_11") (pintype "input"))
      (node (ref "U13") (pin "12") (pinfunction "SCK_12") (pintype "input"))
      (node (ref "U13") (pin "16") (pinfunction "FMT_16") (pintype "input"))
      (node (ref "U13") (pin "19") (pinfunction "DGND_19") (pintype "power_in"))
      (node (ref "U13") (pin "3") (pinfunction "CPGND_3") (pintype "power_in"))
      (node (ref "U13") (pin "9") (pinfunction "AGND_9") (pintype "power_in"))
      (node (ref "U14") (pin "1") (pinfunction "PGND_1") (pintype "power_in"))
      (node (ref "U14") (pin "15") (pinfunction "EP_15") (pintype "power_in"))
      (node (ref "U14") (pin "8") (pinfunction "PGND_8") (pintype "power_in"))
      (node (ref "U2") (pin "3") (pinfunction "GND_3") (pintype "passive"))
      (node (ref "U3") (pin "2") (pinfunction "GND_2") (pintype "power_in"))
      (node (ref "U4") (pin "37") (pinfunction "VSS_37") (pintype "passive"))
      (node (ref "U5") (pin "10") (pinfunction "~{OE}_10") (pintype "input"))
      (node (ref "U5") (pin "5") (pinfunction "GND_5") (pintype "power_in"))
      (node (ref "U6") (pin "3") (pinfunction "GND_3_3") (pintype "power_in"))
      (node (ref "U6") (pin "8") (pinfunction "GND_8_8") (pintype "power_in"))
      (node (ref "U7") (pin "3") (pinfunction "GND_3_3") (pintype "power_in"))
      (node (ref "U7") (pin "8") (pinfunction "GND_8_8") (pintype "power_in"))
      (node (ref "U8") (pin "3") (pinfunction "GND_3_3") (pintype "power_in"))
      (node (ref "U8") (pin "8") (pinfunction "GND_8_8") (pintype "power_in"))
      (node (ref "U9") (pin "3") (pinfunction "GND_3_3") (pintype "power_in"))
      (node (ref "U9") (pin "8") (pinfunction "GND_8_8") (pintype "power_in"))
      (node (ref "Y1") (pin "2") (pinfunction "GND_2") (pintype "passive"))
      (node (ref "Y1") (pin "4") (pinfunction "GND1_4") (pintype "passive"))
      (node (ref "Y2") (pin "2") (pinfunction "GND/CASE_2") (pintype "passive"))
    )
    (net (code "29") (name "GPIO2") (class "Default")
      (node (ref "J18") (pin "15") (pinfunction "15_15") (pintype "passive"))
      (node (ref "J19") (pin "15") (pinfunction "15_15") (pintype "passive"))
      (node (ref "J21") (pin "A5") (pinfunction "A5_A5") (pintype "passive"))
      (node (ref "R33") (pin "1") (pinfunction "1_1") (pintype "passive"))
      (node (ref "TP9") (pin "TP") (pinfunction "TP_TP") (pintype "input"))
      (node (ref "U$1") (pin "SDA") (pinfunction "SDA_SDA") (pintype "bidirectional"))
      (node (ref "U1") (pin "58") (pinfunction "GPIO2_58") (pintype "bidirectional"))
    )
    (net (code "30") (name "GPIO3") (class "Default")
      (node (ref "J18") (pin "16") (pinfunction "16_16") (pintype "passive"))
      (node (ref "J19") (pin "16") (pinfunction "16_16") (pintype "passive"))
      (node (ref "J21") (pin "A6") (pinfunction "A6_A6") (pintype "passive"))
      (node (ref "R34") (pin "1") (pinfunction "1_1") (pintype "passive"))
      (node (ref "TP10") (pin "TP") (pinfunction "TP_TP") (pintype "input"))
      (node (ref "U$1") (pin "SCL") (pinfunction "SCL_SCL") (pintype "bidirectional"))
      (node (ref "U1") (pin "56") (pinfunction "GPIO3_56") (pintype "bidirectional"))
    )
    (net (code "31") (name "GPIO4") (class "Default")
      (node (ref "J18") (pin "13") (pinfunction "13_13") (pintype "passive"))
      (node (ref "J19") (pin "13") (pinfunction "13_13") (pintype "passive"))
      (node (ref "U1") (pin "54") (pinfunction "GPIO4_54") (pintype "bidirectional"))
    )
    (net (code "32") (name "GPIO5") (class "Default")
      (node (ref "U1") (pin "34") (pinfunction "GPIO5_34") (pintype "bidirectional"))
    )
    (net (code "33") (name "GPIO6") (class "Default")
      (node (ref "U$1") (pin "AC_DET") (pinfunction "AC_DET_AC_DET") (pintype "bidirectional"))
      (node (ref "U1") (pin "30") (pinfunction "GPIO6_30") (pintype "bidirectional"))
    )
    (net (code "34") (name "GPIO7") (class "Default")
      (node (ref "J18") (pin "4") (pinfunction "4_4") (pintype "passive"))
      (node (ref "J19") (pin "4") (pinfunction "4_4") (pintype "passive"))
      (node (ref "U1") (pin "37") (pinfunction "GPIO7_37") (pintype "bidirectional"))
    )
    (net (code "35") (name "GPIO8") (class "Default")
      (node (ref "J18") (pin "3") (pinfunction "3_3") (pintype "passive"))
      (node (ref "J19") (pin "3") (pinfunction "3_3") (pintype "passive"))
      (node (ref "U1") (pin "39") (pinfunction "GPIO8_39") (pintype "bidirectional"))
    )
    (net (code "36") (name "GPIO9") (class "Default")
      (node (ref "J18") (pin "5") (pinfunction "5_5") (pintype "passive"))
      (node (ref "J19") (pin "5") (pinfunction "5_5") (pintype "passive"))
      (node (ref "U1") (pin "40") (pinfunction "GPIO9_40") (pintype "bidirectional"))
    )
    (net (code "37") (name "GPIO10") (class "Default")
      (node (ref "J18") (pin "8") (pinfunction "8_8") (pintype "passive"))
      (node (ref "J19") (pin "8") (pinfunction "8_8") (pintype "passive"))
      (node (ref "U1") (pin "44") (pinfunction "GPIO10_44") (pintype "bidirectional"))
    )
    (net (code "38") (name "GPIO11") (class "Default")
      (node (ref "J18") (pin "6") (pinfunction "6_6") (pintype "passive"))
      (node (ref "J19") (pin "6") (pinfunction "6_6") (pintype "passive"))
      (node (ref "U1") (pin "38") (pinfunction "GPIO11_38") (pintype "bidirectional"))
    )
    (net (code "39") (name "GPIO12") (class "Default")
      (node (ref "U1") (pin "31") (pinfunction "GPIO12_31") (pintype "bidirectional"))
    )
    (net (code "40") (name "GPIO13") (class "Default")
      (node (ref "U1") (pin "28") (pinfunction "GPIO13_28") (pintype "bidirectional"))
    )
    (net (code "41") (name "GPIO14") (class "Default")
      (node (ref "J18") (pin "14") (pinfunction "14_14") (pintype "passive"))
      (node (ref "J19") (pin "14") (pinfunction "14_14") (pintype "passive"))
      (node (ref "U1") (pin "55") (pinfunction "GPIO14_55") (pintype "bidirectional"))
    )
    (net (code "42") (name "GPIO15") (class "Default")
      (node (ref "J18") (pin "11") (pinfunction "11_11") (pintype "passive"))
      (node (ref "J19") (pin "11") (pinfunction "11_11") (pintype "passive"))
      (node (ref "U1") (pin "51") (pinfunction "GPIO15_51") (pintype "bidirectional"))
    )
    (net (code "43") (name "GPIO16") (class "Default")
      (node (ref "U$1") (pin "CHRG_CTL") (pinfunction "CHRG_CTL_CHRG_CTL") (pintype "bidirectional"))
      (node (ref "U1") (pin "29") (pinfunction "GPIO16_29") (pintype "bidirectional"))
    )
    (net (code "44") (name "GPIO17") (class "Default")
      (node (ref "J18") (pin "12") (pinfunction "12_12") (pintype "passive"))
      (node (ref "J19") (pin "12") (pinfunction "12_12") (pintype "passive"))
      (node (ref "U1") (pin "50") (pinfunction "GPIO17_50") (pintype "bidirectional"))
    )
    (net (code "45") (name "GPIO18") (class "Default")
      (node (ref "U1") (pin "49") (pinfunction "GPIO18_49") (pintype "bidirectional"))
      (node (ref "U13") (pin "13") (pinfunction "BCK_13") (pintype "input"))
    )
    (net (code "46") (name "GPIO19") (class "Default")
      (node (ref "U1") (pin "26") (pinfunction "GPIO19_26") (pintype "bidirectional"))
      (node (ref "U13") (pin "15") (pinfunction "LRCK_15") (pintype "input"))
    )
    (net (code "47") (name "GPIO20") (class "Default")
      (node (ref "U1") (pin "27") (pinfunction "GPIO20_27") (pintype "bidirectional"))
    )
    (net (code "48") (name "GPIO21") (class "Default")
      (node (ref "U1") (pin "25") (pinfunction "GPIO21_25") (pintype "bidirectional"))
      (node (ref "U13") (pin "14") (pinfunction "DIN_14") (pintype "input"))
    )
    (net (code "49") (name "GPIO22") (class "Default")
      (node (ref "J18") (pin "7") (pinfunction "7_7") (pintype "passive"))
      (node (ref "J19") (pin "7") (pinfunction "7_7") (pintype "passive"))
      (node (ref "U1") (pin "46") (pinfunction "GPIO22_46") (pintype "bidirectional"))
    )
    (net (code "50") (name "GPIO23") (class "Default")
      (node (ref "J18") (pin "10") (pinfunction "10_10") (pintype "passive"))
      (node (ref "J19") (pin "10") (pinfunction "10_10") (pintype "passive"))
      (node (ref "U1") (pin "47") (pinfunction "GPIO23_47") (pintype "bidirectional"))
    )
    (net (code "51") (name "GPIO24") (class "Default")
      (node (ref "U1") (pin "45") (pinfunction "GPIO24_45") (pintype "bidirectional"))
    )
    (net (code "52") (name "GPIO25") (class "Default")
      (node (ref "U1") (pin "41") (pinfunction "GPIO25_41") (pintype "bidirectional"))
    )
    (net (code "53") (name "GPIO26") (class "Default")
      (node (ref "U1") (pin "24") (pinfunction "GPIO26_24") (pintype "bidirectional"))
    )
    (net (code "54") (name "GPIO27") (class "Default")
      (node (ref "J18") (pin "9") (pinfunction "9_9") (pintype "passive"))
      (node (ref "J19") (pin "9") (pinfunction "9_9") (pintype "passive"))
      (node (ref "U1") (pin "48") (pinfunction "GPIO27_48") (pintype "bidirectional"))
    )
    (net (code "55") (name "GPIO_VREF") (class "Default")
      (node (ref "JP1") (pin "2") (pinfunction "2_2") (pintype "passive"))
      (node (ref "U1") (pin "78") (pinfunction "GPIO_VREF_78") (pintype "power_in"))
    )
    (net (code "56") (name "HDMI0_CEC") (class "Default")
      (node (ref "J2") (pin "13") (pinfunction "CEC_13") (pintype "bidirectional"))
      (node (ref "U1") (pin "151") (pinfunction "HDMI0_CEC_151") (pintype "input"))
    )
    (net (code "57") (name "HDMI0_CLK_N") (class "Default")
      (node (ref "J2") (pin "12") (pinfunction "TMDS_CLOCK-_12") (pintype "bidirectional"))
      (node (ref "U1") (pin "190") (pinfunction "HDMI0_CLK_N_190") (pintype "output"))
      (node (ref "U8") (pin "5") (pinfunction "D2-_5") (pintype "bidirectional"))
      (node (ref "U8") (pin "6") (pinfunction "D2-_6") (pintype "bidirectional"))
    )
    (net (code "58") (name "HDMI0_CLK_P") (class "Default")
      (node (ref "J2") (pin "10") (pinfunction "TMDS_CLOCK+_10") (pintype "bidirectional"))
      (node (ref "U1") (pin "188") (pinfunction "HDMI0_CLK_P_188") (pintype "output"))
      (node (ref "U8") (pin "4") (pinfunction "D2+_4") (pintype "bidirectional"))
      (node (ref "U8") (pin "7") (pinfunction "D2+_7") (pintype "bidirectional"))
    )
    (net (code "59") (name "HDMI0_HOTPLUG") (class "Default")
      (node (ref "J2") (pin "19") (pinfunction "HOT_PLUG_DETECT_19") (pintype "input"))
      (node (ref "U1") (pin "153") (pinfunction "HDMI0_HOTPLUG_153") (pintype "input"))
    )
    (net (code "60") (name "HDMI0_SCL") (class "Default")
      (node (ref "J2") (pin "15") (pinfunction "SCL_15") (pintype "bidirectional"))
      (node (ref "U1") (pin "200") (pinfunction "HDMI0_SCL_200") (pintype "bidirectional"))
    )
    (net (code "61") (name "HDMI0_SDA") (class "Default")
      (node (ref "J2") (pin "16") (pinfunction "SDA_16") (pintype "bidirectional"))
      (node (ref "U1") (pin "199") (pinfunction "HDMI0_SDA_199") (pintype "bidirectional"))
    )
    (net (code "62") (name "HDMI0_TX0_N") (class "Default")
      (node (ref "J2") (pin "9") (pinfunction "TMDS_DATA0-_9") (pintype "bidirectional"))
      (node (ref "U1") (pin "184") (pinfunction "HDMI0_TX0_N_184") (pintype "output"))
      (node (ref "U8") (pin "2") (pinfunction "D1-_2") (pintype "bidirectional"))
      (node (ref "U8") (pin "9") (pinfunction "D1-_9") (pintype "bidirectional"))
    )
    (net (code "63") (name "HDMI0_TX0_P") (class "Default")
      (node (ref "J2") (pin "7") (pinfunction "TMDS_DATA0+_7") (pintype "bidirectional"))
      (node (ref "U1") (pin "182") (pinfunction "HDMI0_TX0_P_182") (pintype "output"))
      (node (ref "U8") (pin "1") (pinfunction "D1+_1") (pintype "bidirectional"))
      (node (ref "U8") (pin "10") (pinfunction "D1+_10") (pintype "bidirectional"))
    )
    (net (code "64") (name "HDMI0_TX1_N") (class "Default")
      (node (ref "J2") (pin "6") (pinfunction "TMDS_DATA1-_6") (pintype "bidirectional"))
      (node (ref "U1") (pin "178") (pinfunction "HDMI0_TX1_N_178") (pintype "output"))
      (node (ref "U9") (pin "5") (pinfunction "D2-_5") (pintype "bidirectional"))
      (node (ref "U9") (pin "6") (pinfunction "D2-_6") (pintype "bidirectional"))
    )
    (net (code "65") (name "HDMI0_TX1_P") (class "Default")
      (node (ref "J2") (pin "4") (pinfunction "TMDS_DATA1+_4") (pintype "bidirectional"))
      (node (ref "U1") (pin "176") (pinfunction "HDMI0_TX1_P_176") (pintype "output"))
      (node (ref "U9") (pin "4") (pinfunction "D2+_4") (pintype "bidirectional"))
      (node (ref "U9") (pin "7") (pinfunction "D2+_7") (pintype "bidirectional"))
    )
    (net (code "66") (name "HDMI0_TX2_N") (class "Default")
      (node (ref "J2") (pin "3") (pinfunction "TMDS_DATA2-_3") (pintype "bidirectional"))
      (node (ref "U1") (pin "172") (pinfunction "HDMI0_TX2_N_172") (pintype "output"))
      (node (ref "U9") (pin "2") (pinfunction "D1-_2") (pintype "bidirectional"))
      (node (ref "U9") (pin "9") (pinfunction "D1-_9") (pintype "bidirectional"))
    )
    (net (code "67") (name "HDMI0_TX2_P") (class "Default")
      (node (ref "J2") (pin "1") (pinfunction "TMDS_DATA2+_1") (pintype "bidirectional"))
      (node (ref "U1") (pin "170") (pinfunction "HDMI0_TX2_P_170") (pintype "output"))
      (node (ref "U9") (pin "1") (pinfunction "D1+_1") (pintype "bidirectional"))
      (node (ref "U9") (pin "10") (pinfunction "D1+_10") (pintype "bidirectional"))
    )
    (net (code "68") (name "HDMI1_CEC") (class "Default")
      (node (ref "J3") (pin "13") (pinfunction "CEC_13") (pintype "bidirectional"))
      (node (ref "U1") (pin "149") (pinfunction "HDMI1_CEC_149") (pintype "input"))
    )
    (net (code "69") (name "HDMI1_CLK_N") (class "Default")
      (node (ref "J3") (pin "12") (pinfunction "TMDS_CLOCK-_12") (pintype "bidirectional"))
      (node (ref "U1") (pin "166") (pinfunction "HDMI1_CLK_N_166") (pintype "output"))
      (node (ref "U10") (pin "5") (pinfunction "D2-_5") (pintype "bidirectional"))
      (node (ref "U10") (pin "6") (pinfunction "D2-_6") (pintype "bidirectional"))
    )
    (net (code "70") (name "HDMI1_CLK_P") (class "Default")
      (node (ref "J3") (pin "10") (pinfunction "TMDS_CLOCK+_10") (pintype "bidirectional"))
      (node (ref "U1") (pin "164") (pinfunction "HDMI1_CLK_P_164") (pintype "output"))
      (node (ref "U10") (pin "4") (pinfunction "D2+_4") (pintype "bidirectional"))
      (node (ref "U10") (pin "7") (pinfunction "D2+_7") (pintype "bidirectional"))
    )
    (net (code "71") (name "HDMI1_HOTPLUG") (class "Default")
      (node (ref "J3") (pin "19") (pinfunction "HOT_PLUG_DETECT_19") (pintype "input"))
      (node (ref "U1") (pin "143") (pinfunction "HDMI1_HOTPLUG_143") (pintype "input"))
    )
    (net (code "72") (name "HDMI1_SCL") (class "Default")
      (node (ref "J3") (pin "15") (pinfunction "SCL_15") (pintype "bidirectional"))
      (node (ref "U1") (pin "147") (pinfunction "HDMI1_SCL_147") (pintype "bidirectional"))
    )
    (net (code "73") (name "HDMI1_SDA") (class "Default")
      (node (ref "J3") (pin "16") (pinfunction "SDA_16") (pintype "bidirectional"))
      (node (ref "U1") (pin "145") (pinfunction "HDMI1_SDA_145") (pintype "bidirectional"))
    )
    (net (code "74") (name "HDMI1_TX0_N") (class "Default")
      (node (ref "J3") (pin "9") (pinfunction "TMDS_DATA0-_9") (pintype "bidirectional"))
      (node (ref "U1") (pin "160") (pinfunction "HDMI1_TX0_N_160") (pintype "output"))
      (node (ref "U10") (pin "2") (pinfunction "D1-_2") (pintype "bidirectional"))
      (node (ref "U10") (pin "9") (pinfunction "D1-_9") (pintype "bidirectional"))
    )
    (net (code "75") (name "HDMI1_TX0_P") (class "Default")
      (node (ref "J3") (pin "7") (pinfunction "TMDS_DATA0+_7") (pintype "bidirectional"))
      (node (ref "U1") (pin "158") (pinfunction "HDMI1_TX0_P_158") (pintype "output"))
      (node (ref "U10") (pin "1") (pinfunction "D1+_1") (pintype "bidirectional"))
      (node (ref "U10") (pin "10") (pinfunction "D1+_10") (pintype "bidirectional"))
    )
    (net (code "76") (name "HDMI1_TX1_N") (class "Default")
      (node (ref "J3") (pin "6") (pinfunction "TMDS_DATA1-_6") (pintype "bidirectional"))
      (node (ref "U1") (pin "154") (pinfunction "HDMI1_TX1_N_154") (pintype "output"))
      (node (ref "U11") (pin "5") (pinfunction "D2-_5") (pintype "bidirectional"))
      (node (ref "U11") (pin "6") (pinfunction "D2-_6") (pintype "bidirectional"))
    )
    (net (code "77") (name "HDMI1_TX1_P") (class "Default")
      (node (ref "J3") (pin "4") (pinfunction "TMDS_DATA1+_4") (pintype "bidirectional"))
      (node (ref "U1") (pin "152") (pinfunction "HDMI1_TX1_P_152") (pintype "output"))
      (node (ref "U11") (pin "4") (pinfunction "D2+_4") (pintype "bidirectional"))
      (node (ref "U11") (pin "7") (pinfunction "D2+_7") (pintype "bidirectional"))
    )
    (net (code "78") (name "HDMI1_TX2_N") (class "Default")
      (node (ref "J3") (pin "3") (pinfunction "TMDS_DATA2-_3") (pintype "bidirectional"))
      (node (ref "U1") (pin "148") (pinfunction "HDMI1_TX2_N_148") (pintype "output"))
      (node (ref "U11") (pin "2") (pinfunction "D1-_2") (pintype "bidirectional"))
      (node (ref "U11") (pin "9") (pinfunction "D1-_9") (pintype "bidirectional"))
    )
    (net (code "79") (name "HDMI1_TX2_P") (class "Default")
      (node (ref "J3") (pin "1") (pinfunction "TMDS_DATA2+_1") (pintype "bidirectional"))
      (node (ref "U1") (pin "146") (pinfunction "HDMI1_TX2_P_146") (pintype "output"))
      (node (ref "U11") (pin "1") (pinfunction "D1+_1") (pintype "bidirectional"))
      (node (ref "U11") (pin "10") (pinfunction "D1+_10") (pintype "bidirectional"))
    )
    (net (code "80") (name "HDMI_5V") (class "Default")
      (node (ref "C1") (pin "2") (pinfunction "2_2") (pintype "passive"))
      (node (ref "J2") (pin "18") (pinfunction "+5V_POWER_18") (pintype "power_in"))
      (node (ref "J3") (pin "18") (pinfunction "+5V_POWER_18") (pintype "power_in"))
      (node (ref "U2") (pin "2") (pinfunction "VOUT_2") (pintype "output"))
    )
    (net (code "81") (name "HP_AUDIO_L") (class "Default")
      (node (ref "IC1") (pin "16") (pinfunction "OUTL_16") (pintype "output"))
      (node (ref "J17") (pin "2") (pinfunction "2_2") (pintype "passive"))
    )
    (net (code "82") (name "HP_AUDIO_R") (class "Default")
      (node (ref "IC1") (pin "5") (pinfunction "OUTR_5") (pintype "output"))
      (node (ref "J17") (pin "3") (pinfunction "3_3") (pintype "passive"))
    )
    (net (code "83") (name "HP_EN") (class "Default")
      (node (ref "IC1") (pin "13") (pinfunction "EN_13") (pintype "input"))
      (node (ref "J17") (pin "5") (pinfunction "5_5") (pintype "passive"))
      (node (ref "R32") (pin "1") (pinfunction "1_1") (pintype "passive"))
    )
    (net (code "84") (name "HUB_NRESET") (class "Default")
      (node (ref "C11") (pin "1") (pinfunction "1_1") (pintype "passive"))
      (node (ref "R7") (pin "2") (pinfunction "2_2") (pintype "passive"))
      (node (ref "U4") (pin "26") (pinfunction "RESET_N_26") (pintype "passive"))
    )
    (net (code "85") (name "HUB_XTALIN") (class "Default")
      (node (ref "C12") (pin "1") (pinfunction "1_1") (pintype "passive"))
      (node (ref "U4") (pin "33") (pinfunction "XTALIN/CLKIN_33") (pintype "passive"))
      (node (ref "Y1") (pin "1") (pinfunction "1_1") (pintype "passive"))
    )
    (net (code "86") (name "HUB_XTALOUT") (class "Default")
      (node (ref "C13") (pin "1") (pinfunction "1_1") (pintype "passive"))
      (node (ref "U4") (pin "32") (pinfunction "XTALOUT_32") (pintype "output"))
      (node (ref "Y1") (pin "3") (pinfunction "2_3") (pintype "passive"))
    )
    (net (code "87") (name "LED_~{ACTIVITY}") (class "Default")
      (node (ref "J16") (pin "B1") (pinfunction "B1_B1") (pintype "passive"))
      (node (ref "U1") (pin "21") (pinfunction "LED_~{ACTIVITY}_21") (pintype "bidirectional"))
    )
    (net (code "88") (name "LED_~{PWR}") (class "Default")
      (node (ref "J16") (pin "B2") (pinfunction "B2_B2") (pintype "passive"))
      (node (ref "U1") (pin "95") (pinfunction "LED_~{PWR}_95") (pintype "output"))
    )
    (net (code "89") (name "M2_3.3V") (class "Default")
      (node (ref "C22") (pin "1") (pinfunction "1_1") (pintype "passive"))
      (node (ref "C23") (pin "1") (pinfunction "1_1") (pintype "passive"))
      (node (ref "C24") (pin "1") (pinfunction "1_1") (pintype "passive"))
      (node (ref "C25") (pin "1") (pinfunction "1_1") (pintype "passive"))
      (node (ref "C26") (pin "1") (pinfunction "1_1") (pintype "passive"))
      (node (ref "C27") (pin "1") (pinfunction "1_1") (pintype "passive"))
      (node (ref "J7") (pin "12") (pinfunction "P12_12") (pintype "passive"))
      (node (ref "J7") (pin "14") (pinfunction "P14_14") (pintype "passive"))
      (node (ref "J7") (pin "16") (pinfunction "P16_16") (pintype "passive"))
      (node (ref "J7") (pin "18") (pinfunction "P18_18") (pintype "passive"))
      (node (ref "J7") (pin "2") (pinfunction "P2_2") (pintype "passive"))
      (node (ref "J7") (pin "4") (pinfunction "P4_4") (pintype "passive"))
      (node (ref "J7") (pin "70") (pinfunction "P70_70") (pintype "passive"))
      (node (ref "J7") (pin "72") (pinfunction "P72_72") (pintype "passive"))
      (node (ref "J7") (pin "74") (pinfunction "P74_74") (pintype "passive"))
      (node (ref "L1") (pin "2") (pinfunction "2_2") (pintype "passive"))
      (node (ref "R19") (pin "1") (pinfunction "1_1") (pintype "passive"))
      (node (ref "TP7") (pin "TP") (pinfunction "TP_TP") (pintype "input"))
      (node (ref "Y2") (pin "1") (pinfunction "TRI-STATE_1") (pintype "passive"))
      (node (ref "Y2") (pin "4") (pinfunction "VDD_4") (pintype "power_in"))
    )
    (net (code "90") (name "MIPI0_C_N") (class "Default")
      (node (ref "J1") (pin "8") (pinfunction "8_8") (pintype "passive"))
      (node (ref "U1") (pin "127") (pinfunction "MIPI0_C_N_127") (pintype "input"))
    )
    (net (code "91") (name "MIPI0_C_P") (class "Default")
      (node (ref "J1") (pin "9") (pinfunction "9_9") (pintype "passive"))
      (node (ref "U1") (pin "129") (pinfunction "MIPI0_C_P_129") (pintype "input"))
    )
    (net (code "92") (name "MIPI0_D0_N") (class "Default")
      (node (ref "J1") (pin "2") (pinfunction "2_2") (pintype "passive"))
      (node (ref "U1") (pin "115") (pinfunction "MIPI0_D0_N_115") (pintype "input"))
    )
    (net (code "93") (name "MIPI0_D0_P") (class "Default")
      (node (ref "J1") (pin "3") (pinfunction "3_3") (pintype "passive"))
      (node (ref "U1") (pin "117") (pinfunction "MIPI0_D0_P_117") (pintype "input"))
    )
    (net (code "94") (name "MIPI0_D1_N") (class "Default")
      (node (ref "J1") (pin "5") (pinfunction "5_5") (pintype "passive"))
      (node (ref "U1") (pin "121") (pinfunction "MIPI0_D1_N_121") (pintype "input"))
    )
    (net (code "95") (name "MIPI0_D1_P") (class "Default")
      (node (ref "J1") (pin "6") (pinfunction "6_6") (pintype "passive"))
      (node (ref "U1") (pin "123") (pinfunction "MIPI0_D1_P_123") (pintype "input"))
    )
    (net (code "96") (name "MIPI0_D2_N") (class "Default")
      (node (ref "J1") (pin "11") (pinfunction "11_11") (pintype "passive"))
      (node (ref "U1") (pin "133") (pinfunction "MIPI0_D2_N_133") (pintype "input"))
    )
    (net (code "97") (name "MIPI0_D2_P") (class "Default")
      (node (ref "J1") (pin "12") (pinfunction "12_12") (pintype "passive"))
      (node (ref "U1") (pin "135") (pinfunction "MIPI0_D2_P_135") (pintype "input"))
    )
    (net (code "98") (name "MIPI0_D3_N") (class "Default")
      (node (ref "J1") (pin "14") (pinfunction "14_14") (pintype "passive"))
      (node (ref "U1") (pin "139") (pinfunction "MIPI0_D3_N_139") (pintype "input"))
    )
    (net (code "99") (name "MIPI0_D3_P") (class "Default")
      (node (ref "J1") (pin "15") (pinfunction "15_15") (pintype "passive"))
      (node (ref "U1") (pin "141") (pinfunction "MIPI0_D3_P_141") (pintype "input"))
    )
    (net (code "100") (name "Net-(IC1-CPN)") (class "Default")
      (node (ref "C44") (pin "2") (pinfunction "2_2") (pintype "passive"))
      (node (ref "IC1") (pin "9") (pinfunction "CPN_9") (pintype "passive"))
    )
    (net (code "101") (name "Net-(IC1-CPP)") (class "Default")
      (node (ref "C44") (pin "1") (pinfunction "1_1") (pintype "passive"))
      (node (ref "IC1") (pin "11") (pinfunction "CPP_11") (pintype "passive"))
    )
    (net (code "102") (name "Net-(IC1-G1)") (class "Default")
      (node (ref "IC1") (pin "7") (pinfunction "G1_7") (pintype "input"))
      (node (ref "JP3") (pin "2") (pinfunction "2_2") (pintype "passive"))
    )
    (net (code "103") (name "Net-(IC1-GO)") (class "Default")
      (node (ref "IC1") (pin "6") (pinfunction "GO_6") (pintype "input"))
      (node (ref "JP2") (pin "2") (pinfunction "2_2") (pintype "passive"))
    )
    (net (code "104") (name "Net-(IC1-HPVDD)") (class "Default")
      (node (ref "C42") (pin "2") (pinfunction "2_2") (pintype "passive"))
      (node (ref "IC1") (pin "12") (pinfunction "HPVDD_12") (pintype "passive"))
    )
    (net (code "105") (name "Net-(IC1-HPVSS)") (class "Default")
      (node (ref "C43") (pin "1") (pinfunction "1_1") (pintype "passive"))
      (node (ref "IC1") (pin "8") (pinfunction "HPVSS_8") (pintype "passive"))
    )
    (net (code "106") (name "Net-(IC1-INL-)") (class "Default")
      (node (ref "C41") (pin "2") (pinfunction "2_2") (pintype "passive"))
      (node (ref "IC1") (pin "1") (pinfunction "INL-_1") (pintype "input"))
    )
    (net (code "107") (name "Net-(IC1-INR-)") (class "Default")
      (node (ref "C40") (pin "2") (pinfunction "2_2") (pintype "passive"))
      (node (ref "IC1") (pin "4") (pinfunction "INR-_4") (pintype "input"))
    )
    (net (code "108") (name "Net-(J5-CC1)") (class "Default")
      (node (ref "J5") (pin "A5") (pinfunction "CC1_A5") (pintype "passive"))
      (node (ref "R22") (pin "2") (pinfunction "2_2") (pintype "passive"))
    )
    (net (code "109") (name "Net-(J5-CC2)") (class "Default")
      (node (ref "J5") (pin "B5") (pinfunction "CC2_B5") (pintype "passive"))
      (node (ref "R23") (pin "2") (pinfunction "2_2") (pintype "passive"))
    )
    (net (code "110") (name "Net-(J6-CC1)") (class "Default")
      (node (ref "J6") (pin "A5") (pinfunction "CC1_A5") (pintype "passive"))
      (node (ref "R4") (pin "2") (pinfunction "2_2") (pintype "passive"))
    )
    (net (code "111") (name "Net-(J6-CC2)") (class "Default")
      (node (ref "J6") (pin "B5") (pinfunction "CC2_B5") (pintype "passive"))
      (node (ref "R5") (pin "2") (pinfunction "2_2") (pintype "passive"))
    )
    (net (code "112") (name "Net-(J7-P68)") (class "Default")
      (node (ref "J7") (pin "68") (pinfunction "P68_68") (pintype "passive"))
      (node (ref "Y2") (pin "3") (pinfunction "OUTPUT_3") (pintype "output"))
    )
    (net (code "113") (name "Net-(J9-CC1)") (class "Default")
      (node (ref "J9") (pin "A5") (pinfunction "CC1_A5") (pintype "passive"))
      (node (ref "R8") (pin "2") (pinfunction "2_2") (pintype "passive"))
    )
    (net (code "114") (name "Net-(J9-CC2)") (class "Default")
      (node (ref "J9") (pin "B5") (pinfunction "CC2_B5") (pintype "passive"))
      (node (ref "R9") (pin "2") (pinfunction "2_2") (pintype "passive"))
    )
    (net (code "115") (name "Net-(J10-GK_1)") (class "Default")
      (node (ref "J10") (pin "13") (pinfunction "GK_1_13") (pintype "passive"))
      (node (ref "R2") (pin "2") (pinfunction "2_2") (pintype "passive"))
    )
    (net (code "116") (name "Net-(J10-GK_2)") (class "Default")
      (node (ref "J10") (pin "15") (pinfunction "GK_2_15") (pintype "passive"))
      (node (ref "R3") (pin "2") (pinfunction "2_2") (pintype "passive"))
    )
    (net (code "117") (name "Net-(J11-CC1)") (class "Default")
      (node (ref "J11") (pin "A5") (pinfunction "CC1_A5") (pintype "passive"))
      (node (ref "R20") (pin "2") (pinfunction "2_2") (pintype "passive"))
    )
    (net (code "118") (name "Net-(J11-CC2)") (class "Default")
      (node (ref "J11") (pin "B5") (pinfunction "CC2_B5") (pintype "passive"))
      (node (ref "R21") (pin "2") (pinfunction "2_2") (pintype "passive"))
    )
    (net (code "119") (name "Net-(JP4-Pad1)") (class "Default")
      (node (ref "JP4") (pin "1") (pinfunction "1_1") (pintype "passive"))
      (node (ref "R30") (pin "1") (pinfunction "1_1") (pintype "passive"))
    )
    (net (code "120") (name "Net-(JP4-Pad3)") (class "Default")
      (node (ref "JP4") (pin "3") (pinfunction "3_3") (pintype "passive"))
      (node (ref "R29") (pin "1") (pinfunction "1_1") (pintype "passive"))
    )
    (net (code "121") (name "Net-(L1-Pad1)") (class "Default")
      (node (ref "L1") (pin "1") (pinfunction "1_1") (pintype "passive"))
      (node (ref "U12") (pin "6") (pinfunction "6_6") (pintype "passive"))
    )
    (net (code "122") (name "Net-(U3-ILIM)") (class "Default")
      (node (ref "R15") (pin "2") (pinfunction "2_2") (pintype "passive"))
      (node (ref "U3") (pin "5") (pinfunction "ILIM_5") (pintype "output"))
    )
    (net (code "123") (name "Net-(U4-HS_IND{slash}CFG_SEL1)") (class "Default")
      (node (ref "R13") (pin "1") (pinfunction "1_1") (pintype "passive"))
      (node (ref "U4") (pin "25") (pinfunction "HS_IND/CFG_SEL1_25") (pintype "passive"))
    )
    (net (code "124") (name "Net-(U4-RBIAS)") (class "Default")
      (node (ref "R10") (pin "2") (pinfunction "2_2") (pintype "passive"))
      (node (ref "U4") (pin "35") (pinfunction "RBIAS_35") (pintype "passive"))
    )
    (net (code "125") (name "Net-(U4-SCL{slash}SMBCLK{slash}CFG_SEL0)") (class "Default")
      (node (ref "R12") (pin "1") (pinfunction "1_1") (pintype "passive"))
      (node (ref "U4") (pin "24") (pinfunction "SCL/SMBCLK/CFG_SEL0_24") (pintype "passive"))
    )
    (net (code "126") (name "Net-(U4-SDA{slash}SMBDATA{slash}NON_REM1)") (class "Default")
      (node (ref "R11") (pin "1") (pinfunction "1_1") (pintype "passive"))
      (node (ref "U4") (pin "22") (pinfunction "SDA/SMBDATA/NON_REM1_22") (pintype "passive"))
    )
    (net (code "127") (name "Net-(U4-SUSP_IND{slash}LOCAL_PWR{slash}NON_REM0)") (class "Default")
      (node (ref "R14") (pin "1") (pinfunction "1_1") (pintype "passive"))
      (node (ref "U4") (pin "28") (pinfunction "SUSP_IND/LOCAL_PWR/NON_REM0_28") (pintype "passive"))
    )
    (net (code "128") (name "Net-(U13-CAPM)") (class "Default")
      (node (ref "C36") (pin "2") (pinfunction "2_2") (pintype "passive"))
      (node (ref "U13") (pin "4") (pinfunction "CAPM_4") (pintype "output"))
    )
    (net (code "129") (name "Net-(U13-CAPP)") (class "Default")
      (node (ref "C36") (pin "1") (pinfunction "1_1") (pintype "passive"))
      (node (ref "U13") (pin "2") (pinfunction "CAPP_2") (pintype "output"))
    )
    (net (code "130") (name "Net-(U13-LDOO)") (class "Default")
      (node (ref "C28") (pin "1") (pinfunction "1_1") (pintype "passive"))
      (node (ref "C29") (pin "1") (pinfunction "1_1") (pintype "passive"))
      (node (ref "U13") (pin "18") (pinfunction "LDOO_18") (pintype "power_in"))
    )
    (net (code "131") (name "Net-(U13-OUTL)") (class "Default")
      (node (ref "R26") (pin "2") (pinfunction "2_2") (pintype "passive"))
      (node (ref "U13") (pin "6") (pinfunction "OUTL_6") (pintype "output"))
    )
    (net (code "132") (name "Net-(U13-OUTR)") (class "Default")
      (node (ref "R27") (pin "2") (pinfunction "2_2") (pintype "passive"))
      (node (ref "U13") (pin "7") (pinfunction "OUTR_7") (pintype "output"))
    )
    (net (code "133") (name "Net-(U13-VNEG)") (class "Default")
      (node (ref "C37") (pin "1") (pinfunction "1_1") (pintype "passive"))
      (node (ref "U13") (pin "5") (pinfunction "VNEG_5") (pintype "power_in"))
    )
    (net (code "134") (name "Net-(U13-XSMT)") (class "Default")
      (node (ref "R28") (pin "1") (pinfunction "1_1") (pintype "passive"))
      (node (ref "U13") (pin "17") (pinfunction "XSMT_17") (pintype "input"))
    )
    (net (code "135") (name "Net-(U14-GAIN)") (class "Default")
      (node (ref "JP4") (pin "2") (pinfunction "2_2") (pintype "passive"))
      (node (ref "U14") (pin "5") (pinfunction "GAIN_5") (pintype "input"))
    )
    (net (code "136") (name "Net-(U14-INL+)") (class "Default")
      (node (ref "C47") (pin "2") (pinfunction "2_2") (pintype "passive"))
      (node (ref "U14") (pin "3") (pinfunction "INL+_3") (pintype "input"))
    )
    (net (code "137") (name "Net-(U14-INL-)") (class "Default")
      (node (ref "C49") (pin "2") (pinfunction "2_2") (pintype "passive"))
      (node (ref "U14") (pin "4") (pinfunction "INL-_4") (pintype "input"))
    )
    (net (code "138") (name "Net-(U14-INR+)") (class "Default")
      (node (ref "C48") (pin "2") (pinfunction "2_2") (pintype "passive"))
      (node (ref "U14") (pin "7") (pinfunction "INR+_7") (pintype "input"))
    )
    (net (code "139") (name "Net-(U14-INR-)") (class "Default")
      (node (ref "C50") (pin "2") (pinfunction "2_2") (pintype "passive"))
      (node (ref "U14") (pin "6") (pinfunction "INR-_6") (pintype "input"))
    )
    (net (code "140") (name "OUT_VBUS") (class "Default")
      (node (ref "J6") (pin "A4") (pinfunction "VBUS_A4") (pintype "power_in"))
      (node (ref "J6") (pin "A9") (pinfunction "VBUS_A9") (pintype "power_in"))
      (node (ref "J6") (pin "B4") (pinfunction "VBUS_B4") (pintype "power_in"))
      (node (ref "J6") (pin "B9") (pinfunction "VBUS_B9") (pintype "power_in"))
      (node (ref "R16") (pin "2") (pinfunction "2_2") (pintype "passive"))
      (node (ref "R25") (pin "2") (pinfunction "2_2") (pintype "passive"))
    )
    (net (code "141") (name "OUT_VBUS_2") (class "Default")
      (node (ref "J9") (pin "A4") (pinfunction "VBUS_A4") (pintype "power_in"))
      (node (ref "J9") (pin "A9") (pinfunction "VBUS_A9") (pintype "power_in"))
      (node (ref "J9") (pin "B4") (pinfunction "VBUS_B4") (pintype "power_in"))
      (node (ref "J9") (pin "B9") (pinfunction "VBUS_B9") (pintype "power_in"))
      (node (ref "R24") (pin "2") (pinfunction "2_2") (pintype "passive"))
    )
    (net (code "142") (name "PCIE_CLK_N") (class "Default")
      (node (ref "J7") (pin "53") (pinfunction "P53_53") (pintype "passive"))
      (node (ref "U1") (pin "112") (pinfunction "PCIE_CLK_N_112") (pintype "output"))
    )
    (net (code "143") (name "PCIE_CLK_P") (class "Default")
      (node (ref "J7") (pin "55") (pinfunction "P55_55") (pintype "passive"))
      (node (ref "U1") (pin "110") (pinfunction "PCIE_CLK_P_110") (pintype "output"))
    )
    (net (code "144") (name "PCIE_CLK_~{REQ}") (class "Default")
      (node (ref "J7") (pin "52") (pinfunction "P52_52") (pintype "passive"))
      (node (ref "U1") (pin "102") (pinfunction "PCIE_CLK_~{REQ}_102") (pintype "input"))
    )
    (net (code "145") (name "PCIE_PWR_EN") (class "Default")
      (node (ref "R17") (pin "1") (pinfunction "1_1") (pintype "passive"))
      (node (ref "U1") (pin "106") (pinfunction "PCIE_PWR_EN_106") (pintype "output"))
      (node (ref "U12") (pin "7") (pinfunction "7_7") (pintype "passive"))
    )
    (net (code "146") (name "PCIE_RX_N") (class "Default")
      (node (ref "J7") (pin "43") (pinfunction "P43_43") (pintype "passive"))
      (node (ref "U1") (pin "118") (pinfunction "PCIE_RX_N_118") (pintype "input"))
    )
    (net (code "147") (name "PCIE_RX_P") (class "Default")
      (node (ref "J7") (pin "41") (pinfunction "P41_41") (pintype "passive"))
      (node (ref "U1") (pin "116") (pinfunction "PCIE_RX_P_116") (pintype "input"))
    )
    (net (code "148") (name "PCIE_TX_N") (class "Default")
      (node (ref "J7") (pin "49") (pinfunction "P49_49") (pintype "passive"))
      (node (ref "U1") (pin "124") (pinfunction "PCIE_TX_N_124") (pintype "output"))
    )
    (net (code "149") (name "PCIE_TX_P") (class "Default")
      (node (ref "J7") (pin "47") (pinfunction "P47_47") (pintype "passive"))
      (node (ref "U1") (pin "122") (pinfunction "PCIE_TX_P_122") (pintype "output"))
    )
    (net (code "150") (name "PCIE_~{RST}") (class "Default")
      (node (ref "J7") (pin "50") (pinfunction "P50_50") (pintype "passive"))
      (node (ref "U1") (pin "109") (pinfunction "PCIE_~{RST}_109") (pintype "output"))
    )
    (net (code "151") (name "PCIE_~{WAKE}") (class "Default")
      (node (ref "J7") (pin "54") (pinfunction "P54_54") (pintype "passive"))
      (node (ref "U1") (pin "104") (pinfunction "PCIE_~{WAKE}_104") (pintype "input"))
    )
    (net (code "152") (name "PMIC_ENABLE") (class "Default")
      (node (ref "J21") (pin "B4") (pinfunction "B4_B4") (pintype "passive"))
      (node (ref "U1") (pin "99") (pinfunction "PMIC_ENABLE_99") (pintype "input"))
    )
    (net (code "153") (name "PWR_BUTTON") (class "Default")
      (node (ref "J16") (pin "B3") (pinfunction "B3_B3") (pintype "passive"))
      (node (ref "U$1") (pin "PWR_SW") (pinfunction "PWR_SW_PWR_SW") (pintype "bidirectional"))
      (node (ref "U1") (pin "92") (pinfunction "PWR_BUTTON_92") (pintype "input"))
    )
    (net (code "154") (name "SCL0") (class "Default")
      (node (ref "J1") (pin "20") (pinfunction "20_20") (pintype "passive"))
      (node (ref "U1") (pin "80") (pinfunction "SCL0_80") (pintype "input"))
    )
    (net (code "155") (name "SDA0") (class "Default")
      (node (ref "J1") (pin "21") (pinfunction "21_21") (pintype "passive"))
      (node (ref "U1") (pin "82") (pinfunction "SDA0_82") (pintype "bidirectional"))
    )
    (net (code "156") (name "SPK_L_N") (class "Default")
      (node (ref "J16") (pin "A2") (pinfunction "A2_A2") (pintype "passive"))
      (node (ref "U14") (pin "14") (pinfunction "OUTL-_14") (pintype "output"))
    )
    (net (code "157") (name "SPK_L_P") (class "Default")
      (node (ref "J16") (pin "A3") (pinfunction "A3_A3") (pintype "passive"))
      (node (ref "U14") (pin "13") (pinfunction "OUTL+_13") (pintype "output"))
    )
    (net (code "158") (name "SPK_R_N") (class "Default")
      (node (ref "J16") (pin "A5") (pinfunction "A5_A5") (pintype "passive"))
      (node (ref "U14") (pin "9") (pinfunction "OUTR-_9") (pintype "output"))
    )
    (net (code "159") (name "SPK_R_P") (class "Default")
      (node (ref "J16") (pin "A6") (pinfunction "A6_A6") (pintype "passive"))
      (node (ref "U14") (pin "10") (pinfunction "OUTR+_10") (pintype "output"))
    )
    (net (code "160") (name "USB3-0-D_N") (class "Default")
      (node (ref "U1") (pin "136") (pinfunction "USB3-0-DM_136") (pintype "bidirectional"))
    )
    (net (code "161") (name "USB3-0-D_P") (class "Default")
      (node (ref "U1") (pin "134") (pinfunction "USB3-0-DP_134") (pintype "bidirectional"))
    )
    (net (code "162") (name "USB3-1-D_N") (class "Default")
      (node (ref "U1") (pin "165") (pinfunction "USB3-1-DM_165") (pintype "bidirectional"))
      (node (ref "U5") (pin "6") (pinfunction "HSD1-_6") (pintype "bidirectional"))
    )
    (net (code "163") (name "USB3-1-D_P") (class "Default")
      (node (ref "U1") (pin "163") (pinfunction "USB3-1-DP_163") (pintype "bidirectional"))
      (node (ref "U5") (pin "7") (pinfunction "HSD1+_7") (pintype "bidirectional"))
    )
    (net (code "164") (name "USBH_OUT_N") (class "Default")
      (node (ref "D4") (pin "1") (pinfunction "D+_1") (pintype "bidirectional"))
      (node (ref "J6") (pin "A7") (pinfunction "DN1_A7") (pintype "passive"))
      (node (ref "J6") (pin "B7") (pinfunction "DN2_B7") (pintype "passive"))
      (node (ref "U5") (pin "8") (pinfunction "HSD2-_8") (pintype "bidirectional"))
    )
    (net (code "165") (name "USBH_OUT_P") (class "Default")
      (node (ref "D4") (pin "2") (pinfunction "D-_2") (pintype "bidirectional"))
      (node (ref "J6") (pin "A6") (pinfunction "DP1_A6") (pintype "passive"))
      (node (ref "J6") (pin "B6") (pinfunction "DP2_B6") (pintype "passive"))
      (node (ref "U5") (pin "9") (pinfunction "HSD2+_9") (pintype "bidirectional"))
    )
    (net (code "166") (name "USB_HD1_N") (class "Default")
      (node (ref "D1") (pin "2") (pinfunction "D-_2") (pintype "bidirectional"))
      (node (ref "J4") (pin "2") (pinfunction "D-_2") (pintype "passive"))
      (node (ref "U4") (pin "1") (pinfunction "USBDM_DN1/PRT_DIS_M1_1") (pintype "bidirectional"))
    )
    (net (code "167") (name "USB_HD1_P") (class "Default")
      (node (ref "D1") (pin "1") (pinfunction "D+_1") (pintype "bidirectional"))
      (node (ref "J4") (pin "3") (pinfunction "D+_3") (pintype "passive"))
      (node (ref "U4") (pin "2") (pinfunction "USBDP_DN1/PRT_DIS_P1_2") (pintype "bidirectional"))
    )
    (net (code "168") (name "USB_HD2_N") (class "Default")
      (node (ref "D2") (pin "2") (pinfunction "D-_2") (pintype "bidirectional"))
      (node (ref "J11") (pin "A7") (pinfunction "DN1_A7") (pintype "passive"))
      (node (ref "J11") (pin "B7") (pinfunction "DN2_B7") (pintype "passive"))
      (node (ref "U4") (pin "3") (pinfunction "USBDM_DN2/PRT_DIS_M2_3") (pintype "bidirectional"))
    )
    (net (code "169") (name "USB_HD2_P") (class "Default")
      (node (ref "D2") (pin "1") (pinfunction "D+_1") (pintype "bidirectional"))
      (node (ref "J11") (pin "A6") (pinfunction "DP1_A6") (pintype "passive"))
      (node (ref "J11") (pin "B6") (pinfunction "DP2_B6") (pintype "passive"))
      (node (ref "U4") (pin "4") (pinfunction "USBDP_DN2/PRT_DIS_P2_4") (pintype "bidirectional"))
    )
    (net (code "170") (name "USB_HD3_N") (class "Default")
      (node (ref "D3") (pin "2") (pinfunction "D-_2") (pintype "bidirectional"))
      (node (ref "J5") (pin "A7") (pinfunction "DN1_A7") (pintype "passive"))
      (node (ref "J5") (pin "B7") (pinfunction "DN2_B7") (pintype "passive"))
      (node (ref "U4") (pin "6") (pinfunction "USBDM_DN3/PRT_DIS_M3_6") (pintype "bidirectional"))
    )
    (net (code "171") (name "USB_HD3_P") (class "Default")
      (node (ref "D3") (pin "1") (pinfunction "D+_1") (pintype "bidirectional"))
      (node (ref "J5") (pin "A6") (pinfunction "DP1_A6") (pintype "passive"))
      (node (ref "J5") (pin "B6") (pinfunction "DP2_B6") (pintype "passive"))
      (node (ref "U4") (pin "7") (pinfunction "USBDP_DN3/PRT_DIS_P3_7") (pintype "bidirectional"))
    )
    (net (code "172") (name "USB_HD4_N") (class "Default")
      (node (ref "J16") (pin "B5") (pinfunction "B5_B5") (pintype "passive"))
      (node (ref "U4") (pin "8") (pinfunction "USBDM_DN4/PRT_DIS_M3_8") (pintype "bidirectional"))
    )
    (net (code "173") (name "USB_HD4_P") (class "Default")
      (node (ref "J16") (pin "B6") (pinfunction "B6_B6") (pintype "passive"))
      (node (ref "U4") (pin "9") (pinfunction "USBDP_DN4/PRT_DIS_P4_9") (pintype "bidirectional"))
    )
    (net (code "174") (name "USB_HU_N") (class "Default")
      (node (ref "U4") (pin "30") (pinfunction "USBDM_UP_30") (pintype "passive"))
      (node (ref "U5") (pin "4") (pinfunction "D-_4") (pintype "bidirectional"))
    )
    (net (code "175") (name "USB_HU_P") (class "Default")
      (node (ref "U4") (pin "31") (pinfunction "USBDP_UP_31") (pintype "passive"))
      (node (ref "U5") (pin "3") (pinfunction "D+_3") (pintype "bidirectional"))
    )
    (net (code "176") (name "USB_MUX_SEL") (class "Default")
      (node (ref "R16") (pin "1") (pinfunction "1_1") (pintype "passive"))
      (node (ref "R6") (pin "2") (pinfunction "2_2") (pintype "passive"))
      (node (ref "U5") (pin "2") (pinfunction "SEL_2") (pintype "input"))
    )
    (net (code "177") (name "USB_N") (class "Default")
      (node (ref "D5") (pin "1") (pinfunction "D+_1") (pintype "bidirectional"))
      (node (ref "J9") (pin "A7") (pinfunction "DN1_A7") (pintype "passive"))
      (node (ref "J9") (pin "B7") (pinfunction "DN2_B7") (pintype "passive"))
      (node (ref "U1") (pin "103") (pinfunction "USB_N_103") (pintype "bidirectional"))
    )
    (net (code "178") (name "USB_OTG_ID") (class "Default")
      (node (ref "J21") (pin "B5") (pinfunction "B5_B5") (pintype "passive"))
      (node (ref "U1") (pin "101") (pinfunction "USB_OTG_ID_101") (pintype "input"))
    )
    (net (code "179") (name "USB_P") (class "Default")
      (node (ref "D5") (pin "2") (pinfunction "D-_2") (pintype "bidirectional"))
      (node (ref "J9") (pin "A6") (pinfunction "DP1_A6") (pintype "passive"))
      (node (ref "J9") (pin "B6") (pinfunction "DP2_B6") (pintype "passive"))
      (node (ref "U1") (pin "105") (pinfunction "USB_P_105") (pintype "bidirectional"))
    )
    (net (code "180") (name "VBUS") (class "Default")
      (node (ref "C15") (pin "1") (pinfunction "1_1") (pintype "passive"))
      (node (ref "C16") (pin "1") (pinfunction "1_1") (pintype "passive"))
      (node (ref "C17") (pin "1") (pinfunction "1_1") (pintype "passive"))
      (node (ref "C18") (pin "1") (pinfunction "+_1") (pintype "passive"))
      (node (ref "J11") (pin "A4") (pinfunction "VBUS_A4") (pintype "power_in"))
      (node (ref "J11") (pin "A9") (pinfunction "VBUS_A9") (pintype "power_in"))
      (node (ref "J11") (pin "B4") (pinfunction "VBUS_B4") (pintype "power_in"))
      (node (ref "J11") (pin "B9") (pinfunction "VBUS_B9") (pintype "power_in"))
      (node (ref "J4") (pin "1") (pinfunction "VBUS_1") (pintype "passive"))
      (node (ref "J5") (pin "A4") (pinfunction "VBUS_A4") (pintype "power_in"))
      (node (ref "J5") (pin "A9") (pinfunction "VBUS_A9") (pintype "power_in"))
      (node (ref "J5") (pin "B4") (pinfunction "VBUS_B4") (pintype "power_in"))
      (node (ref "J5") (pin "B9") (pinfunction "VBUS_B9") (pintype "power_in"))
      (node (ref "TP11") (pin "TP") (pinfunction "TP_TP") (pintype "input"))
      (node (ref "U3") (pin "6") (pinfunction "OUT_6") (pintype "output"))
    )
    (net (code "181") (name "VBUS_EN") (class "Default")
      (node (ref "U1") (pin "111") (pinfunction "VBUS_EN_111") (pintype "output"))
      (node (ref "U3") (pin "3") (pinfunction "EN_3") (pintype "input"))
    )
    (net (code "182") (name "WL_~{DISABLE}") (class "Default")
      (node (ref "J21") (pin "B1") (pinfunction "B1_B1") (pintype "passive"))
      (node (ref "U1") (pin "89") (pinfunction "WL_~{DISABLE}_89") (pintype "input"))
    )
    (net (code "183") (name "unconnected-(IC1-PadTH)") (class "Default")
      (node (ref "IC1") (pin "TH") (pinfunction "TH_TH") (pintype "passive"))
    )
    (net (code "184") (name "unconnected-(J2-UTILITY-Pad14)") (class "Default")
      (node (ref "J2") (pin "14") (pinfunction "UTILITY_14") (pintype "bidirectional"))
    )
    (net (code "185") (name "unconnected-(J3-UTILITY-Pad14)") (class "Default")
      (node (ref "J3") (pin "14") (pinfunction "UTILITY_14") (pintype "bidirectional"))
    )
    (net (code "186") (name "unconnected-(J7-P5-Pad5)") (class "Default")
      (node (ref "J7") (pin "5") (pinfunction "P5_5") (pintype "passive"))
    )
    (net (code "187") (name "unconnected-(J7-P6-Pad6)") (class "Default")
      (node (ref "J7") (pin "6") (pinfunction "P6_6") (pintype "passive"))
    )
    (net (code "188") (name "unconnected-(J7-P7-Pad7)") (class "Default")
      (node (ref "J7") (pin "7") (pinfunction "P7_7") (pintype "passive"))
    )
    (net (code "189") (name "unconnected-(J7-P8-Pad8)") (class "Default")
      (node (ref "J7") (pin "8") (pinfunction "P8_8") (pintype "passive"))
    )
    (net (code "190") (name "unconnected-(J7-P10-Pad10)") (class "Default")
      (node (ref "J7") (pin "10") (pinfunction "P10_10") (pintype "passive"))
    )
    (net (code "191") (name "unconnected-(J7-P11-Pad11)") (class "Default")
      (node (ref "J7") (pin "11") (pinfunction "P11_11") (pintype "passive"))
    )
    (net (code "192") (name "unconnected-(J7-P13-Pad13)") (class "Default")
      (node (ref "J7") (pin "13") (pinfunction "P13_13") (pintype "passive"))
    )
    (net (code "193") (name "unconnected-(J7-P17-Pad17)") (class "Default")
      (node (ref "J7") (pin "17") (pinfunction "P17_17") (pintype "passive"))
    )
    (net (code "194") (name "unconnected-(J7-P19-Pad19)") (class "Default")
      (node (ref "J7") (pin "19") (pinfunction "P19_19") (pintype "passive"))
    )
    (net (code "195") (name "unconnected-(J7-P20-Pad20)") (class "Default")
      (node (ref "J7") (pin "20") (pinfunction "P20_20") (pintype "passive"))
    )
    (net (code "196") (name "unconnected-(J7-P22-Pad22)") (class "Default")
      (node (ref "J7") (pin "22") (pinfunction "P22_22") (pintype "passive"))
    )
    (net (code "197") (name "unconnected-(J7-P23-Pad23)") (class "Default")
      (node (ref "J7") (pin "23") (pinfunction "P23_23") (pintype "passive"))
    )
    (net (code "198") (name "unconnected-(J7-P24-Pad24)") (class "Default")
      (node (ref "J7") (pin "24") (pinfunction "P24_24") (pintype "passive"))
    )
    (net (code "199") (name "unconnected-(J7-P25-Pad25)") (class "Default")
      (node (ref "J7") (pin "25") (pinfunction "P25_25") (pintype "passive"))
    )
    (net (code "200") (name "unconnected-(J7-P26-Pad26)") (class "Default")
      (node (ref "J7") (pin "26") (pinfunction "P26_26") (pintype "passive"))
    )
    (net (code "201") (name "unconnected-(J7-P28-Pad28)") (class "Default")
      (node (ref "J7") (pin "28") (pinfunction "P28_28") (pintype "passive"))
    )
    (net (code "202") (name "unconnected-(J7-P29-Pad29)") (class "Default")
      (node (ref "J7") (pin "29") (pinfunction "P29_29") (pintype "passive"))
    )
    (net (code "203") (name "unconnected-(J7-P30-Pad30)") (class "Default")
      (node (ref "J7") (pin "30") (pinfunction "P30_30") (pintype "passive"))
    )
    (net (code "204") (name "unconnected-(J7-P31-Pad31)") (class "Default")
      (node (ref "J7") (pin "31") (pinfunction "P31_31") (pintype "passive"))
    )
    (net (code "205") (name "unconnected-(J7-P32-Pad32)") (class "Default")
      (node (ref "J7") (pin "32") (pinfunction "P32_32") (pintype "passive"))
    )
    (net (code "206") (name "unconnected-(J7-P34-Pad34)") (class "Default")
      (node (ref "J7") (pin "34") (pinfunction "P34_34") (pintype "passive"))
    )
    (net (code "207") (name "unconnected-(J7-P35-Pad35)") (class "Default")
      (node (ref "J7") (pin "35") (pinfunction "P35_35") (pintype "passive"))
    )
    (net (code "208") (name "unconnected-(J7-P36-Pad36)") (class "Default")
      (node (ref "J7") (pin "36") (pinfunction "P36_36") (pintype "passive"))
    )
    (net (code "209") (name "unconnected-(J7-P37-Pad37)") (class "Default")
      (node (ref "J7") (pin "37") (pinfunction "P37_37") (pintype "passive"))
    )
    (net (code "210") (name "unconnected-(J7-P38-Pad38)") (class "Default")
      (node (ref "J7") (pin "38") (pinfunction "P38_38") (pintype "passive"))
    )
    (net (code "211") (name "unconnected-(J7-P40-Pad40)") (class "Default")
      (node (ref "J7") (pin "40") (pinfunction "P40_40") (pintype "passive"))
    )
    (net (code "212") (name "unconnected-(J7-P42-Pad42)") (class "Default")
      (node (ref "J7") (pin "42") (pinfunction "P42_42") (pintype "passive"))
    )
    (net (code "213") (name "unconnected-(J7-P44-Pad44)") (class "Default")
      (node (ref "J7") (pin "44") (pinfunction "P44_44") (pintype "passive"))
    )
    (net (code "214") (name "unconnected-(J7-P46-Pad46)") (class "Default")
      (node (ref "J7") (pin "46") (pinfunction "P46_46") (pintype "passive"))
    )
    (net (code "215") (name "unconnected-(J7-P48-Pad48)") (class "Default")
      (node (ref "J7") (pin "48") (pinfunction "P48_48") (pintype "passive"))
    )
    (net (code "216") (name "unconnected-(J7-P56-Pad56)") (class "Default")
      (node (ref "J7") (pin "56") (pinfunction "P56_56") (pintype "passive"))
    )
    (net (code "217") (name "unconnected-(J7-P58-Pad58)") (class "Default")
      (node (ref "J7") (pin "58") (pinfunction "P58_58") (pintype "passive"))
    )
    (net (code "218") (name "unconnected-(J7-P67-Pad67)") (class "Default")
      (node (ref "J7") (pin "67") (pinfunction "P67_67") (pintype "passive"))
    )
    (net (code "219") (name "unconnected-(J7-P69-Pad69)") (class "Default")
      (node (ref "J7") (pin "69") (pinfunction "P69_69") (pintype "passive"))
    )
    (net (code "220") (name "unconnected-(J10-TRCT1-Pad3)") (class "Default")
      (node (ref "J10") (pin "3") (pinfunction "TRCT1_3") (pintype "passive"))
    )
    (net (code "221") (name "unconnected-(J10-TRCT2-Pad6)") (class "Default")
      (node (ref "J10") (pin "6") (pinfunction "TRCT2_6") (pintype "passive"))
    )
    (net (code "222") (name "unconnected-(J10-TRCT3-Pad9)") (class "Default")
      (node (ref "J10") (pin "9") (pinfunction "TRCT3_9") (pintype "passive"))
    )
    (net (code "223") (name "unconnected-(J10-TRCT4-Pad12)") (class "Default")
      (node (ref "J10") (pin "12") (pinfunction "TRCT4_12") (pintype "passive"))
    )
    (net (code "224") (name "unconnected-(J17-Pad6)") (class "Default")
      (node (ref "J17") (pin "6") (pinfunction "6_6") (pintype "passive"))
    )
    (net (code "225") (name "unconnected-(J17-Pad7)") (class "Default")
      (node (ref "J17") (pin "7") (pinfunction "7_7") (pintype "passive"))
    )
    (net (code "226") (name "unconnected-(U1A-ID_SC-Pad35)") (class "Default")
      (node (ref "U1") (pin "35") (pinfunction "ID_SC_35") (pintype "bidirectional"))
    )
    (net (code "227") (name "unconnected-(U1A-ID_SD-Pad36)") (class "Default")
      (node (ref "U1") (pin "36") (pinfunction "ID_SD_36") (pintype "bidirectional"))
    )
    (net (code "228") (name "unconnected-(U1A-SD_CLK-Pad57)") (class "Default")
      (node (ref "U1") (pin "57") (pinfunction "SD_CLK_57") (pintype "bidirectional"))
    )
    (net (code "229") (name "unconnected-(U1A-SD_CMD-Pad62)") (class "Default")
      (node (ref "U1") (pin "62") (pinfunction "SD_CMD_62") (pintype "input"))
    )
    (net (code "230") (name "unconnected-(U1A-SD_DAT0-Pad63)") (class "Default")
      (node (ref "U1") (pin "63") (pinfunction "SD_DAT0_63") (pintype "bidirectional"))
    )
    (net (code "231") (name "unconnected-(U1A-SD_DAT1-Pad67)") (class "Default")
      (node (ref "U1") (pin "67") (pinfunction "SD_DAT1_67") (pintype "bidirectional"))
    )
    (net (code "232") (name "unconnected-(U1A-SD_DAT2-Pad69)") (class "Default")
      (node (ref "U1") (pin "69") (pinfunction "SD_DAT2_69") (pintype "bidirectional"))
    )
    (net (code "233") (name "unconnected-(U1A-SD_DAT3-Pad61)") (class "Default")
      (node (ref "U1") (pin "61") (pinfunction "SD_DAT3_61") (pintype "bidirectional"))
    )
    (net (code "234") (name "unconnected-(U1A-SD_DAT4-Pad68)") (class "Default")
      (node (ref "U1") (pin "68") (pinfunction "SD_DAT4_68") (pintype "bidirectional"))
    )
    (net (code "235") (name "unconnected-(U1A-SD_DAT5-Pad64)") (class "Default")
      (node (ref "U1") (pin "64") (pinfunction "SD_DAT5_64") (pintype "bidirectional"))
    )
    (net (code "236") (name "unconnected-(U1A-SD_DAT6-Pad72)") (class "Default")
      (node (ref "U1") (pin "72") (pinfunction "SD_DAT6_72") (pintype "bidirectional"))
    )
    (net (code "237") (name "unconnected-(U1A-SD_DAT7-Pad70)") (class "Default")
      (node (ref "U1") (pin "70") (pinfunction "SD_DAT7_70") (pintype "bidirectional"))
    )
    (net (code "238") (name "unconnected-(U1A-SD_PWR_ON-Pad75)") (class "Default")
      (node (ref "U1") (pin "75") (pinfunction "SD_PWR_ON_75") (pintype "output"))
    )
    (net (code "239") (name "unconnected-(U1A-SD_VDD_OVERRIDE-Pad73)") (class "Default")
      (node (ref "U1") (pin "73") (pinfunction "SD_VDD_OVERRIDE_73") (pintype "input"))
    )
    (net (code "240") (name "unconnected-(U1B-MIPI1_C_N-Pad187)") (class "Default")
      (node (ref "U1") (pin "187") (pinfunction "MIPI1_C_N_187") (pintype "output"))
    )
    (net (code "241") (name "unconnected-(U1B-MIPI1_C_P-Pad189)") (class "Default")
      (node (ref "U1") (pin "189") (pinfunction "MIPI1_C_P_189") (pintype "output"))
    )
    (net (code "242") (name "unconnected-(U1B-MIPI1_D0_N-Pad175)") (class "Default")
      (node (ref "U1") (pin "175") (pinfunction "MIPI1_D0_N_175") (pintype "output"))
    )
    (net (code "243") (name "unconnected-(U1B-MIPI1_D0_P-Pad177)") (class "Default")
      (node (ref "U1") (pin "177") (pinfunction "MIPI1_D0_P_177") (pintype "output"))
    )
    (net (code "244") (name "unconnected-(U1B-MIPI1_D1_N-Pad181)") (class "Default")
      (node (ref "U1") (pin "181") (pinfunction "MIPI1_D1_N_181") (pintype "output"))
    )
    (net (code "245") (name "unconnected-(U1B-MIPI1_D1_P-Pad183)") (class "Default")
      (node (ref "U1") (pin "183") (pinfunction "MIPI1_D1_P_183") (pintype "output"))
    )
    (net (code "246") (name "unconnected-(U1B-MIPI1_D2_N-Pad193)") (class "Default")
      (node (ref "U1") (pin "193") (pinfunction "MIPI1_D2_N_193") (pintype "output"))
    )
    (net (code "247") (name "unconnected-(U1B-MIPI1_D2_P-Pad195)") (class "Default")
      (node (ref "U1") (pin "195") (pinfunction "MIPI1_D2_P_195") (pintype "output"))
    )
    (net (code "248") (name "unconnected-(U1B-MIPI1_D3_N-Pad194)") (class "Default")
      (node (ref "U1") (pin "194") (pinfunction "MIPI1_D3_N_194") (pintype "output"))
    )
    (net (code "249") (name "unconnected-(U1B-MIPI1_D3_P-Pad196)") (class "Default")
      (node (ref "U1") (pin "196") (pinfunction "MIPI1_D3_P_196") (pintype "output"))
    )
    (net (code "250") (name "unconnected-(U1B-USB3-0-RX_N-Pad128)") (class "Default")
      (node (ref "U1") (pin "128") (pinfunction "USB3-0-RX_N_128") (pintype "bidirectional"))
    )
    (net (code "251") (name "unconnected-(U1B-USB3-0-RX_P-Pad130)") (class "Default")
      (node (ref "U1") (pin "130") (pinfunction "USB3-0-RX_P_130") (pintype "bidirectional"))
    )
    (net (code "252") (name "unconnected-(U1B-USB3-0-TX_N-Pad140)") (class "Default")
      (node (ref "U1") (pin "140") (pinfunction "USB3-0-TX_N_140") (pintype "bidirectional"))
    )
    (net (code "253") (name "unconnected-(U1B-USB3-0-TX_P-Pad142)") (class "Default")
      (node (ref "U1") (pin "142") (pinfunction "USB3-0-TX_P_142") (pintype "bidirectional"))
    )
    (net (code "254") (name "unconnected-(U1B-USB3-1-RX_N-Pad157)") (class "Default")
      (node (ref "U1") (pin "157") (pinfunction "USB3-1-RX_N_157") (pintype "bidirectional"))
    )
    (net (code "255") (name "unconnected-(U1B-USB3-1-RX_P-Pad159)") (class "Default")
      (node (ref "U1") (pin "159") (pinfunction "USB3-1-RX_P_159") (pintype "bidirectional"))
    )
    (net (code "256") (name "unconnected-(U1B-USB3-1-TX_N-Pad169)") (class "Default")
      (node (ref "U1") (pin "169") (pinfunction "USB3-1-TX_N_169") (pintype "bidirectional"))
    )
    (net (code "257") (name "unconnected-(U1B-USB3-1-TX_P-Pad171)") (class "Default")
      (node (ref "U1") (pin "171") (pinfunction "USB3-1-TX_P_171") (pintype "bidirectional"))
    )
    (net (code "258") (name "unconnected-(U3-~{FAULT}-Pad4)") (class "Default")
      (node (ref "U3") (pin "4") (pinfunction "~{FAULT}_4") (pintype "output"))
    )
    (net (code "259") (name "unconnected-(U4-CRFILT-Pad14)") (class "Default")
      (node (ref "U4") (pin "14") (pinfunction "CRFILT_14") (pintype "passive"))
    )
    (net (code "260") (name "unconnected-(U4-OCS_N1-Pad13)") (class "Default")
      (node (ref "U4") (pin "13") (pinfunction "OCS_N1_13") (pintype "bidirectional"))
    )
    (net (code "261") (name "unconnected-(U4-OCS_N2-Pad17)") (class "Default")
      (node (ref "U4") (pin "17") (pinfunction "OCS_N2_17") (pintype "bidirectional"))
    )
    (net (code "262") (name "unconnected-(U4-OCS_N3-Pad19)") (class "Default")
      (node (ref "U4") (pin "19") (pinfunction "OCS_N3_19") (pintype "bidirectional"))
    )
    (net (code "263") (name "unconnected-(U4-OSC_N4-Pad21)") (class "Default")
      (node (ref "U4") (pin "21") (pinfunction "OSC_N4_21") (pintype "passive"))
    )
    (net (code "264") (name "unconnected-(U4-PLLFILT-Pad34)") (class "Default")
      (node (ref "U4") (pin "34") (pinfunction "PLLFILT_34") (pintype "passive"))
    )
    (net (code "265") (name "unconnected-(U4-PRTPWR1{slash}BC_EN1-Pad12)") (class "Default")
      (node (ref "U4") (pin "12") (pinfunction "PRTPWR1/BC_EN1_12") (pintype "bidirectional"))
    )
    (net (code "266") (name "unconnected-(U4-PRTPWR2{slash}BC_EN2-Pad16)") (class "Default")
      (node (ref "U4") (pin "16") (pinfunction "PRTPWR2/BC_EN2_16") (pintype "bidirectional"))
    )
    (net (code "267") (name "unconnected-(U4-PRTPWR3{slash}BC_EN3-Pad18)") (class "Default")
      (node (ref "U4") (pin "18") (pinfunction "PRTPWR3/BC_EN3_18") (pintype "bidirectional"))
    )
    (net (code "268") (name "unconnected-(U4-PRTPWR4{slash}BC_EN4-Pad20)") (class "Default")
      (node (ref "U4") (pin "20") (pinfunction "PRTPWR4/BC_EN4_20") (pintype "bidirectional"))
    )
    (net (code "269") (name "unconnected-(U4-TEST-Pad11)") (class "Default")
      (node (ref "U4") (pin "11") (pinfunction "TEST_11") (pintype "passive"))
    )
    (net (code "270") (name "unconnected-(U12-Pad2)") (class "Default")
      (node (ref "U12") (pin "2") (pinfunction "2_2") (pintype "passive"))
    )
    (net (code "271") (name "unconnected-(U12-Pad5)") (class "Default")
      (node (ref "U12") (pin "5") (pinfunction "5_5") (pintype "passive"))
    )
    (net (code "272") (name "~{RPIBOOT}") (class "Default")
      (node (ref "J21") (pin "B3") (pinfunction "B3_B3") (pintype "passive"))
      (node (ref "U1") (pin "93") (pinfunction "~{RPIBOOT}_93") (pintype "input"))
    )
    (net (code "273") (name "~{SPK_SHDN}") (class "Default")
      (node (ref "J17") (pin "8") (pinfunction "8_8") (pintype "passive"))
      (node (ref "R31") (pin "1") (pinfunction "1_1") (pintype "passive"))
      (node (ref "U14") (pin "2") (pinfunction "~{SHDN}_2") (pintype "input"))
    )
  )
)
